# ER-524D_CoilDriver24.net
KiCad netlist of a schematic drawn in EAGLE
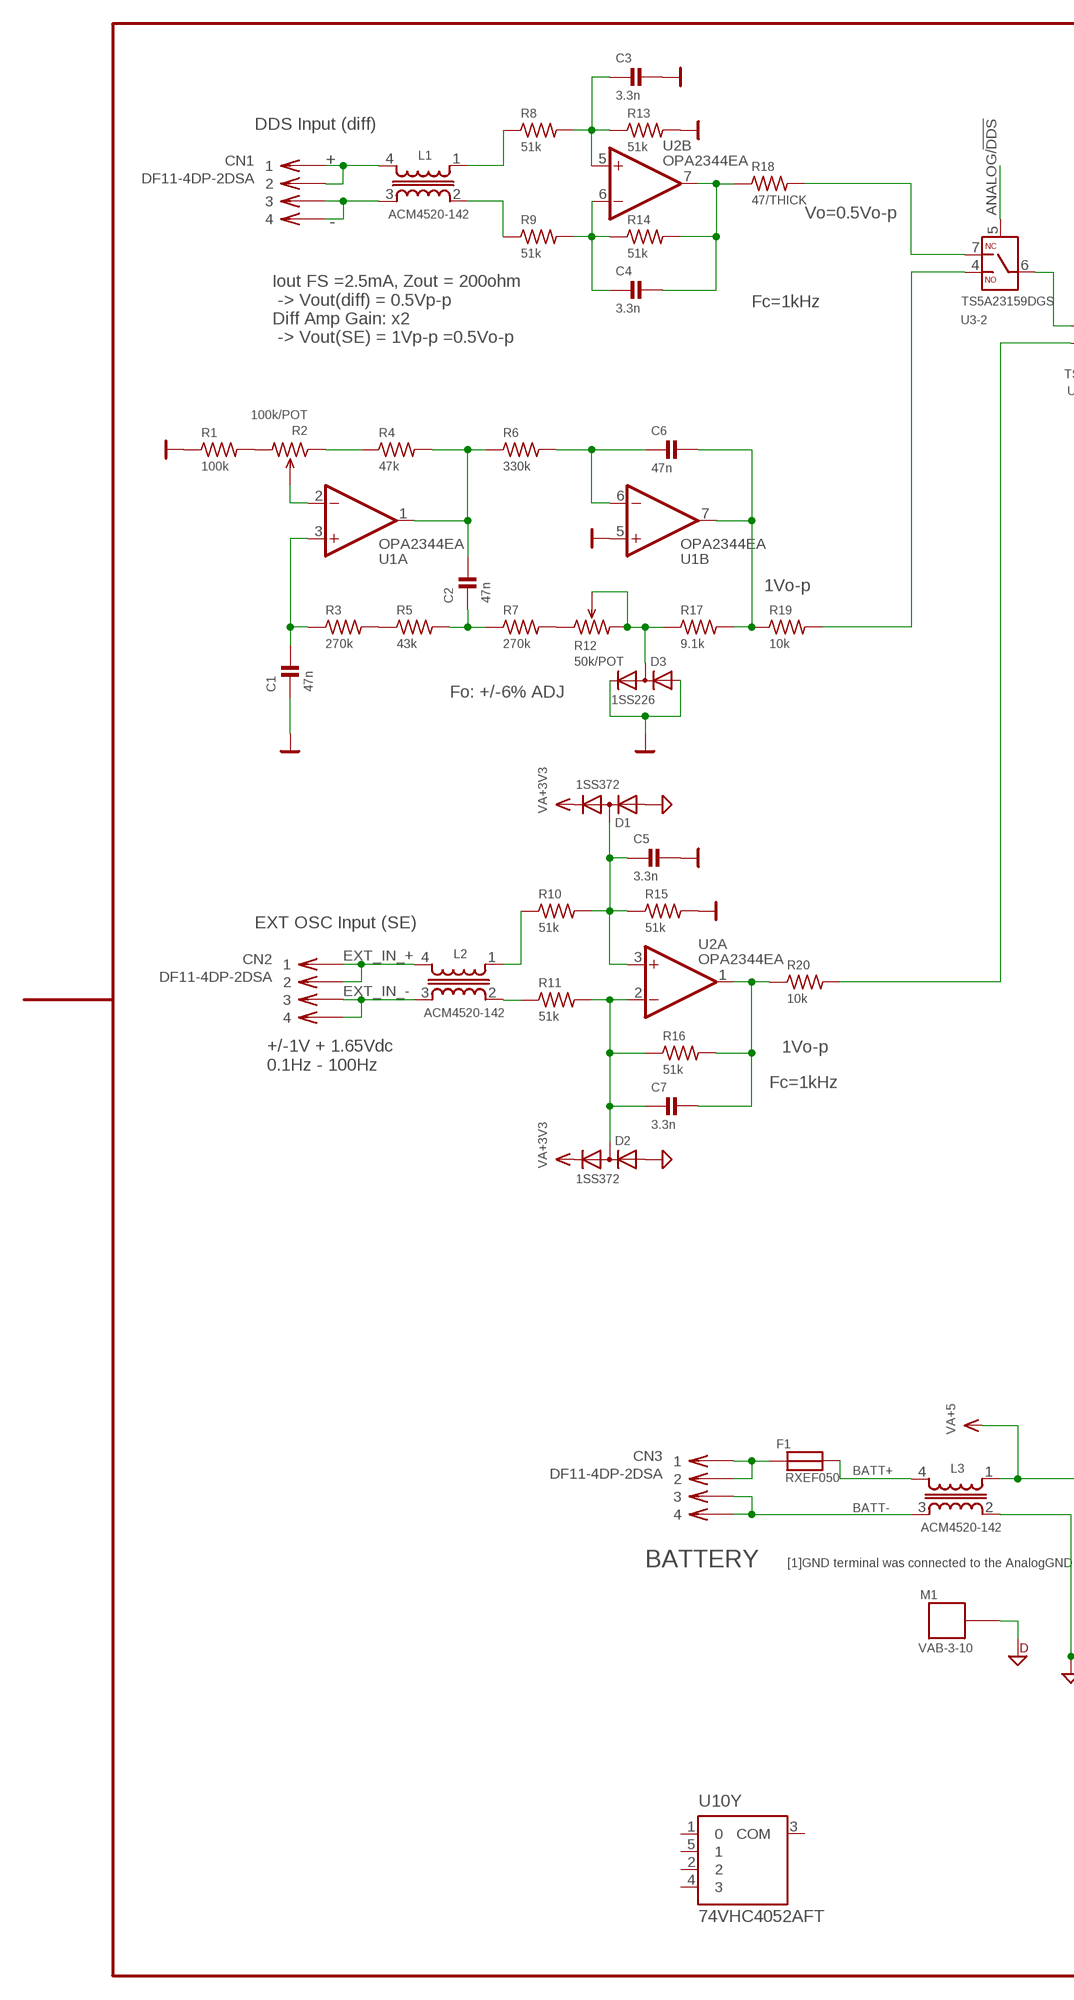
[diagram p0: schematic, sheet 1, part 1 of 2]
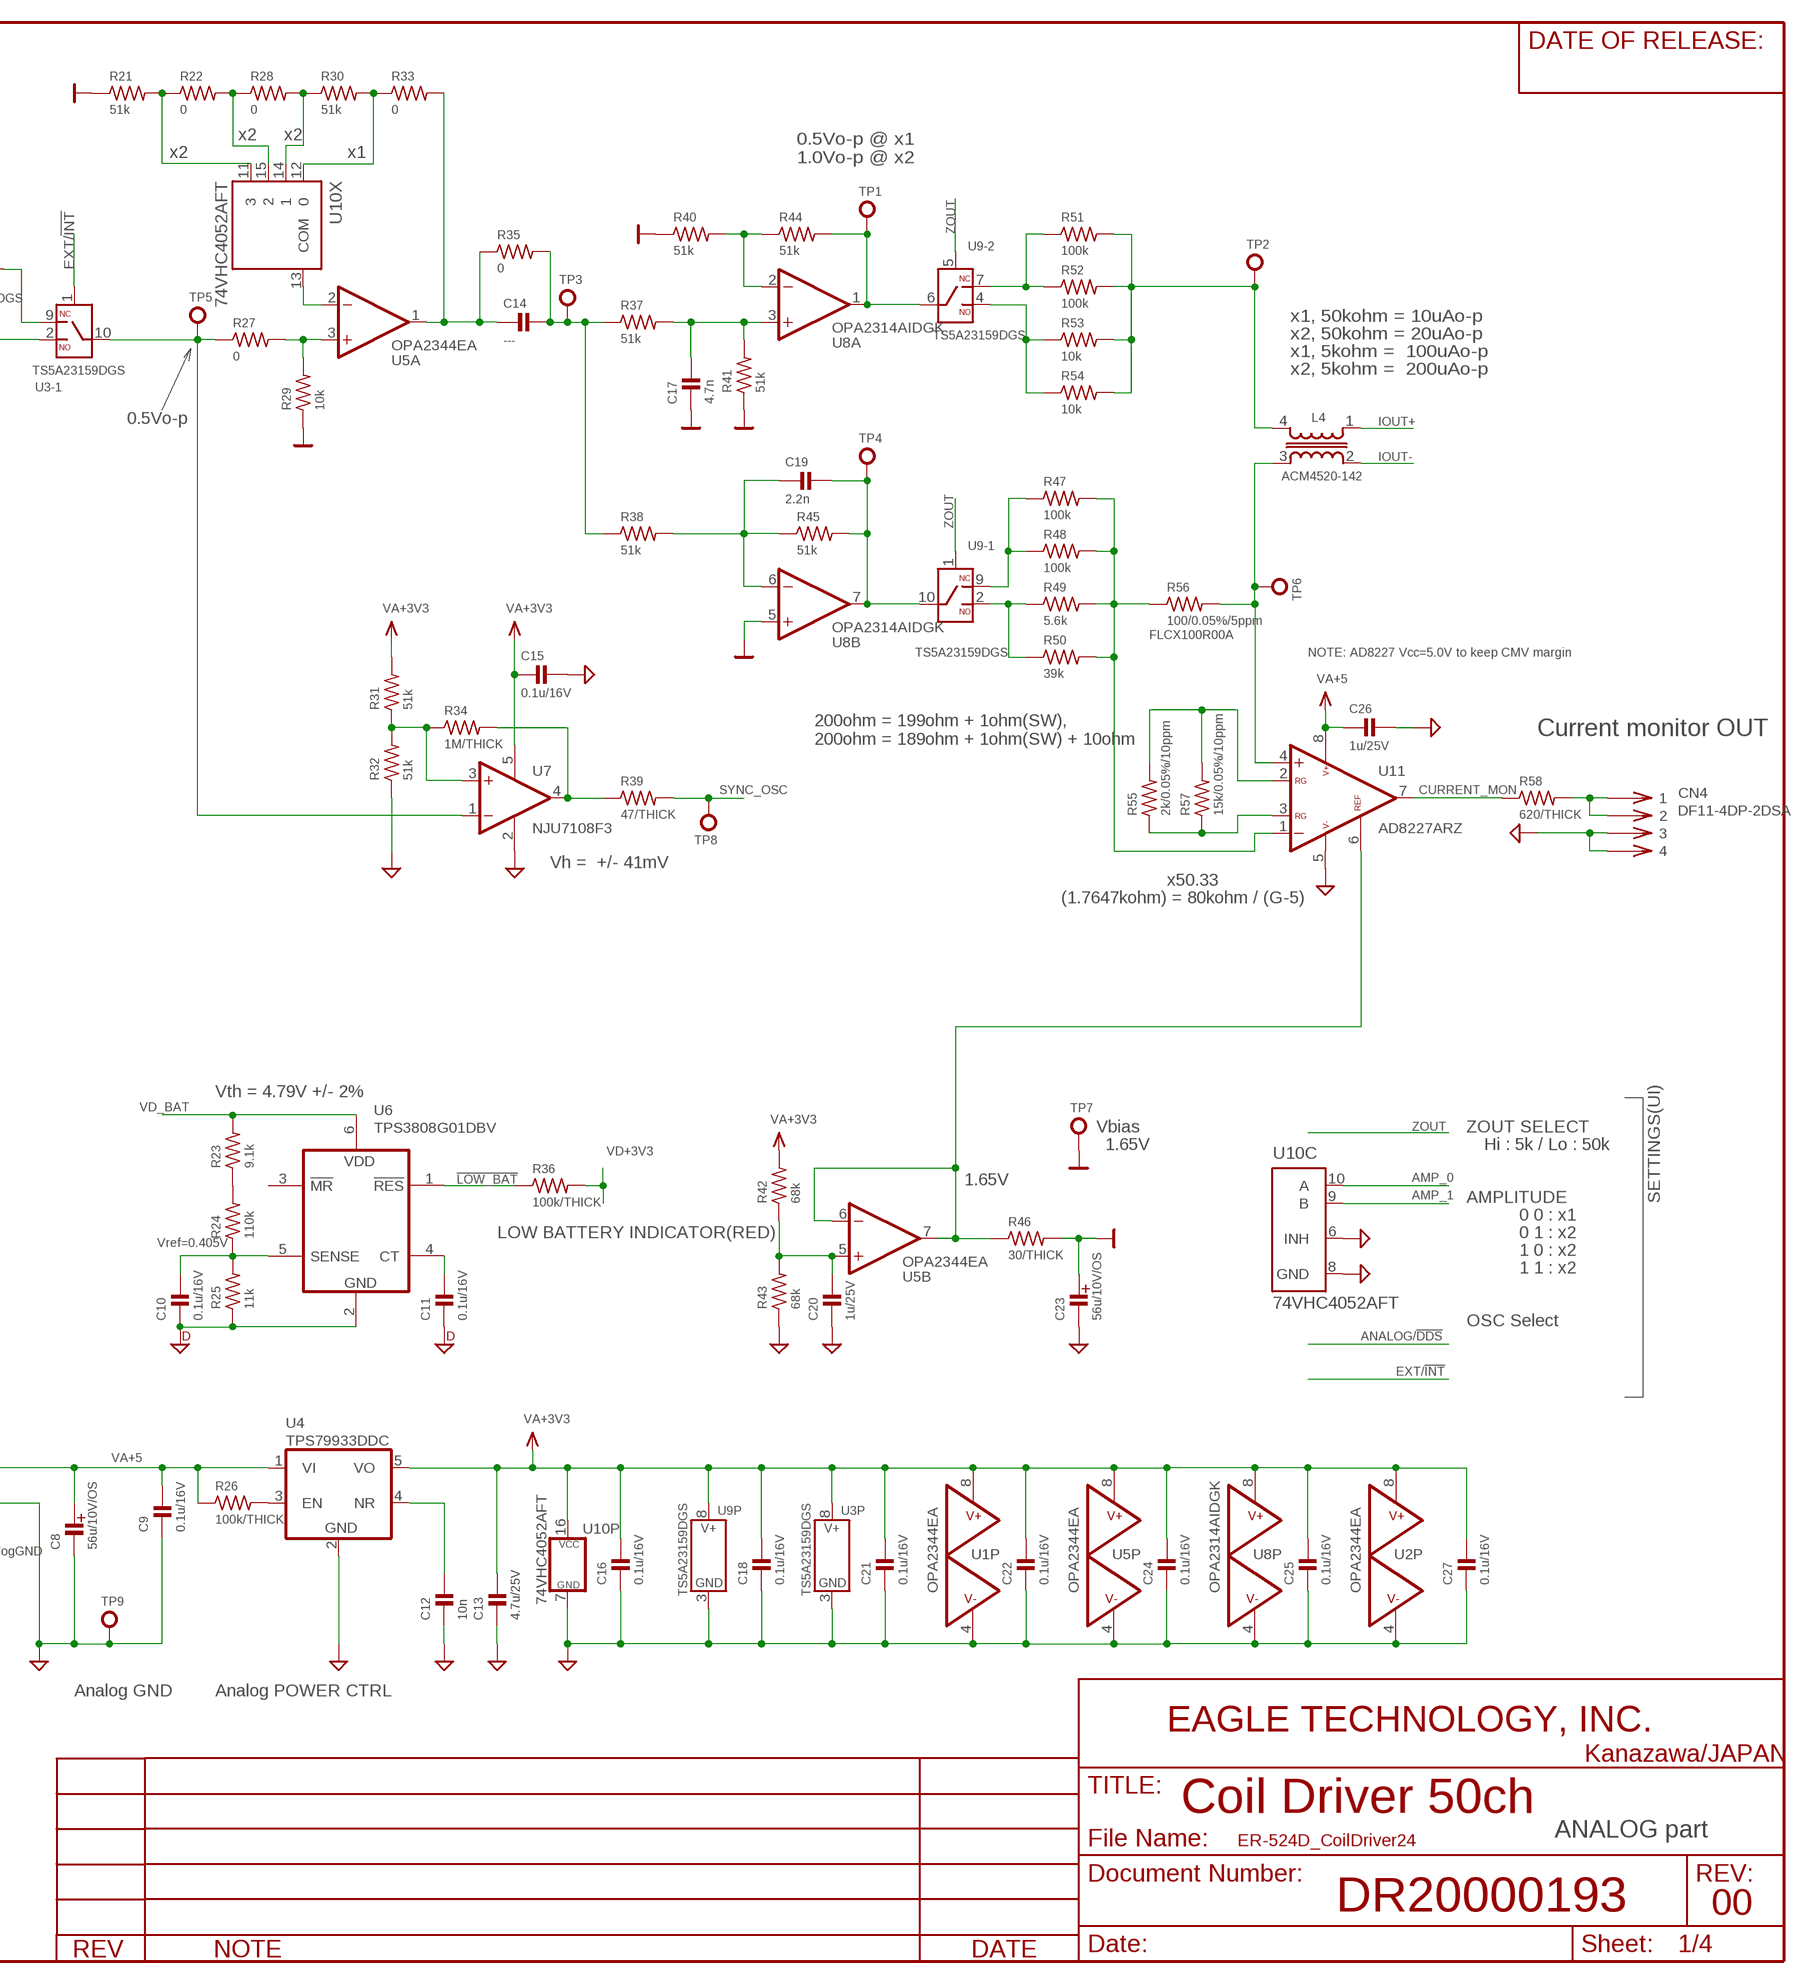
[diagram p1: schematic, sheet 1, part 2 of 2]
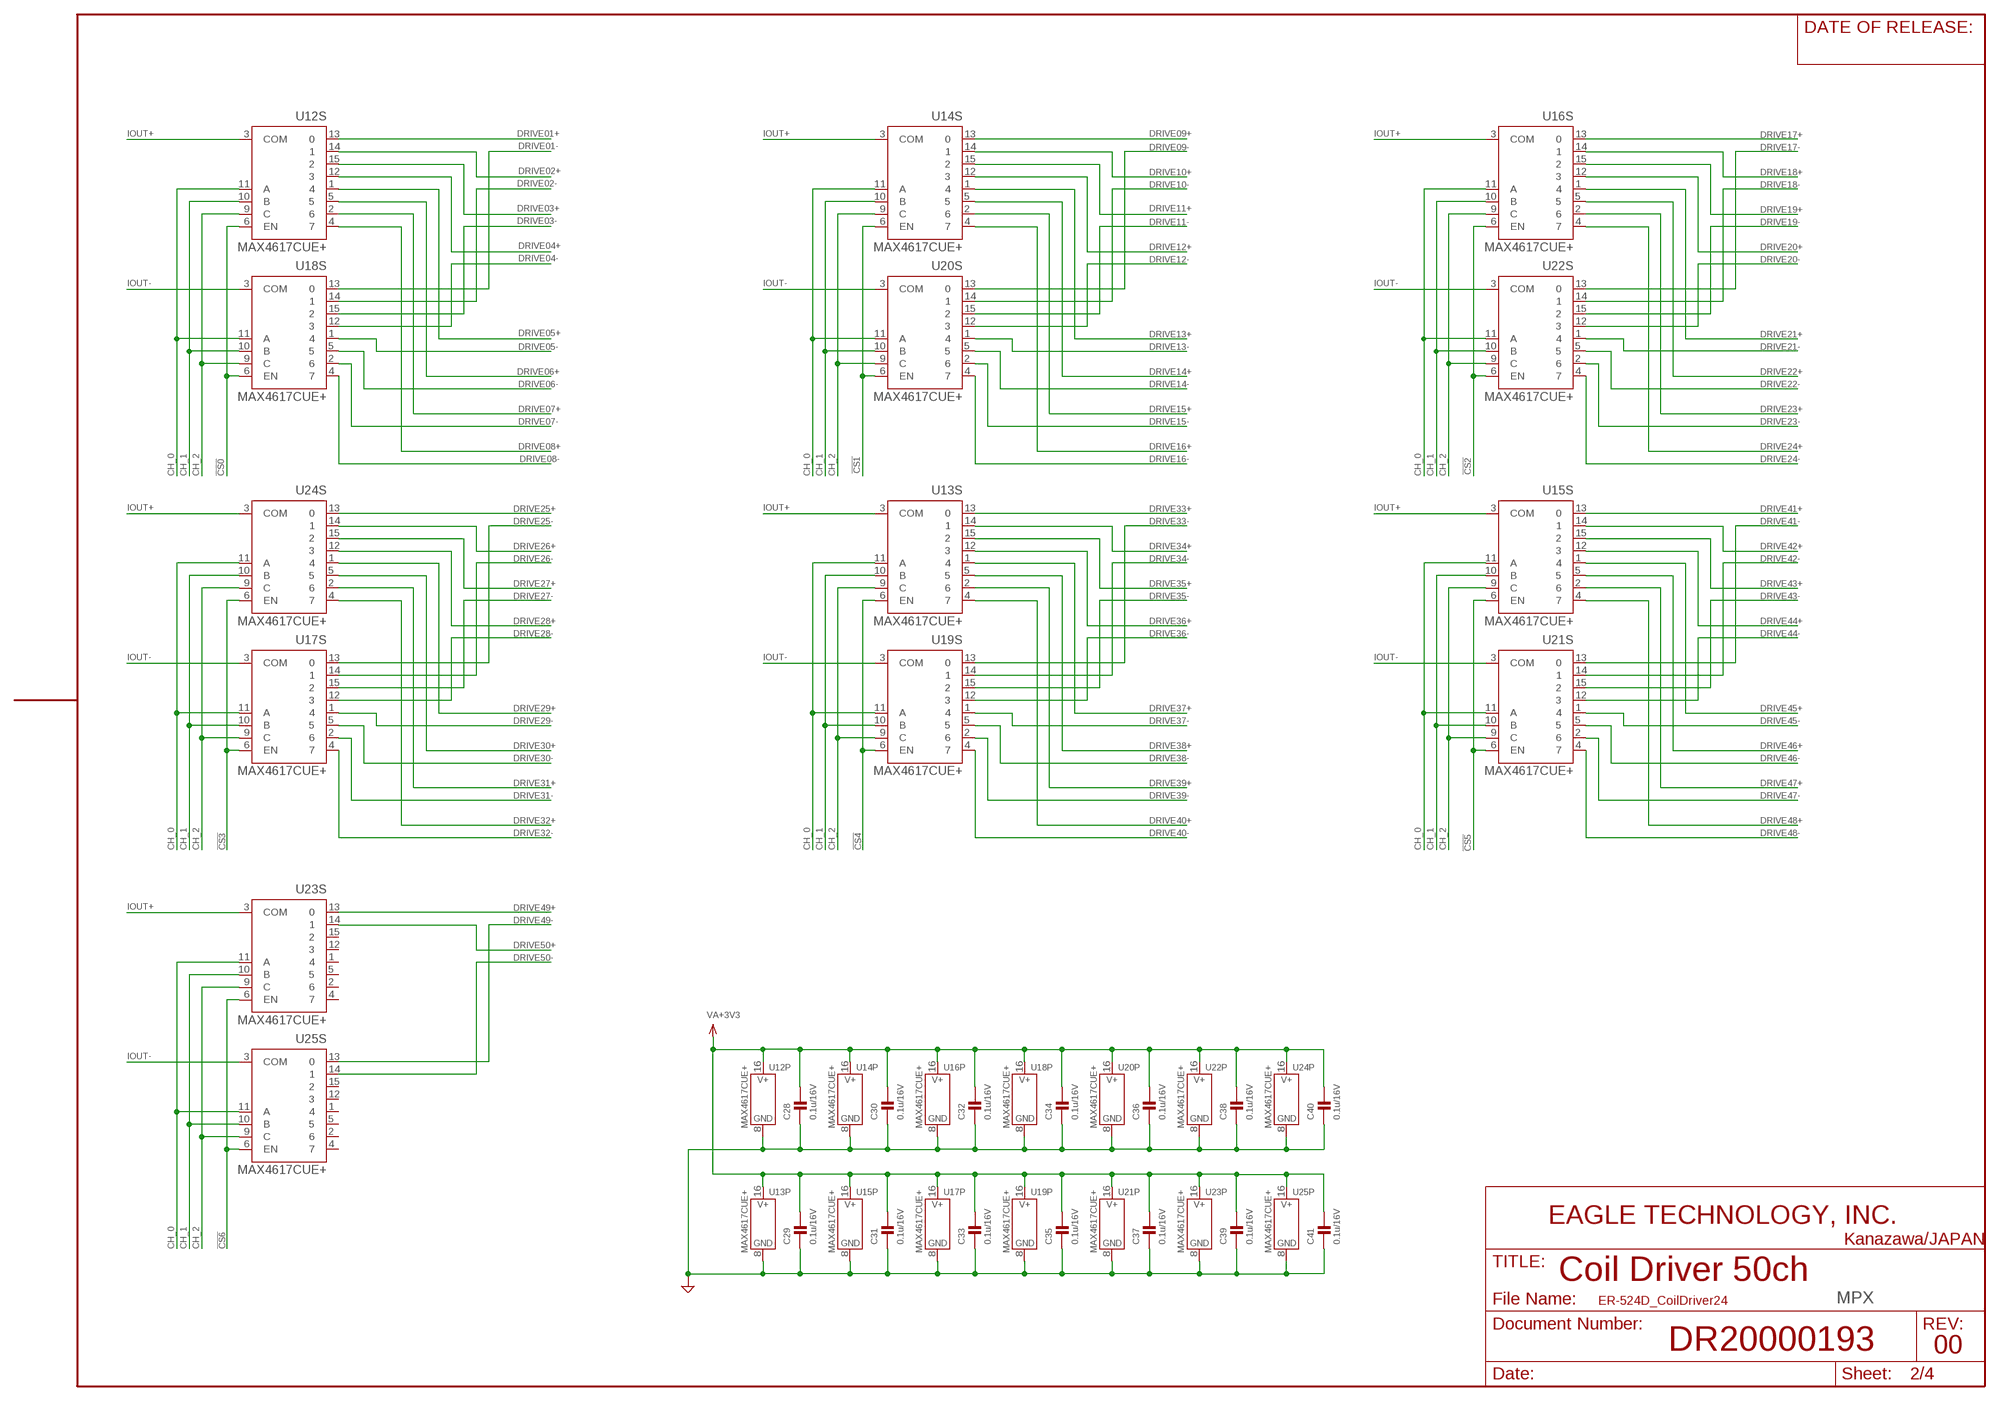
[diagram p2: schematic, sheet 2]
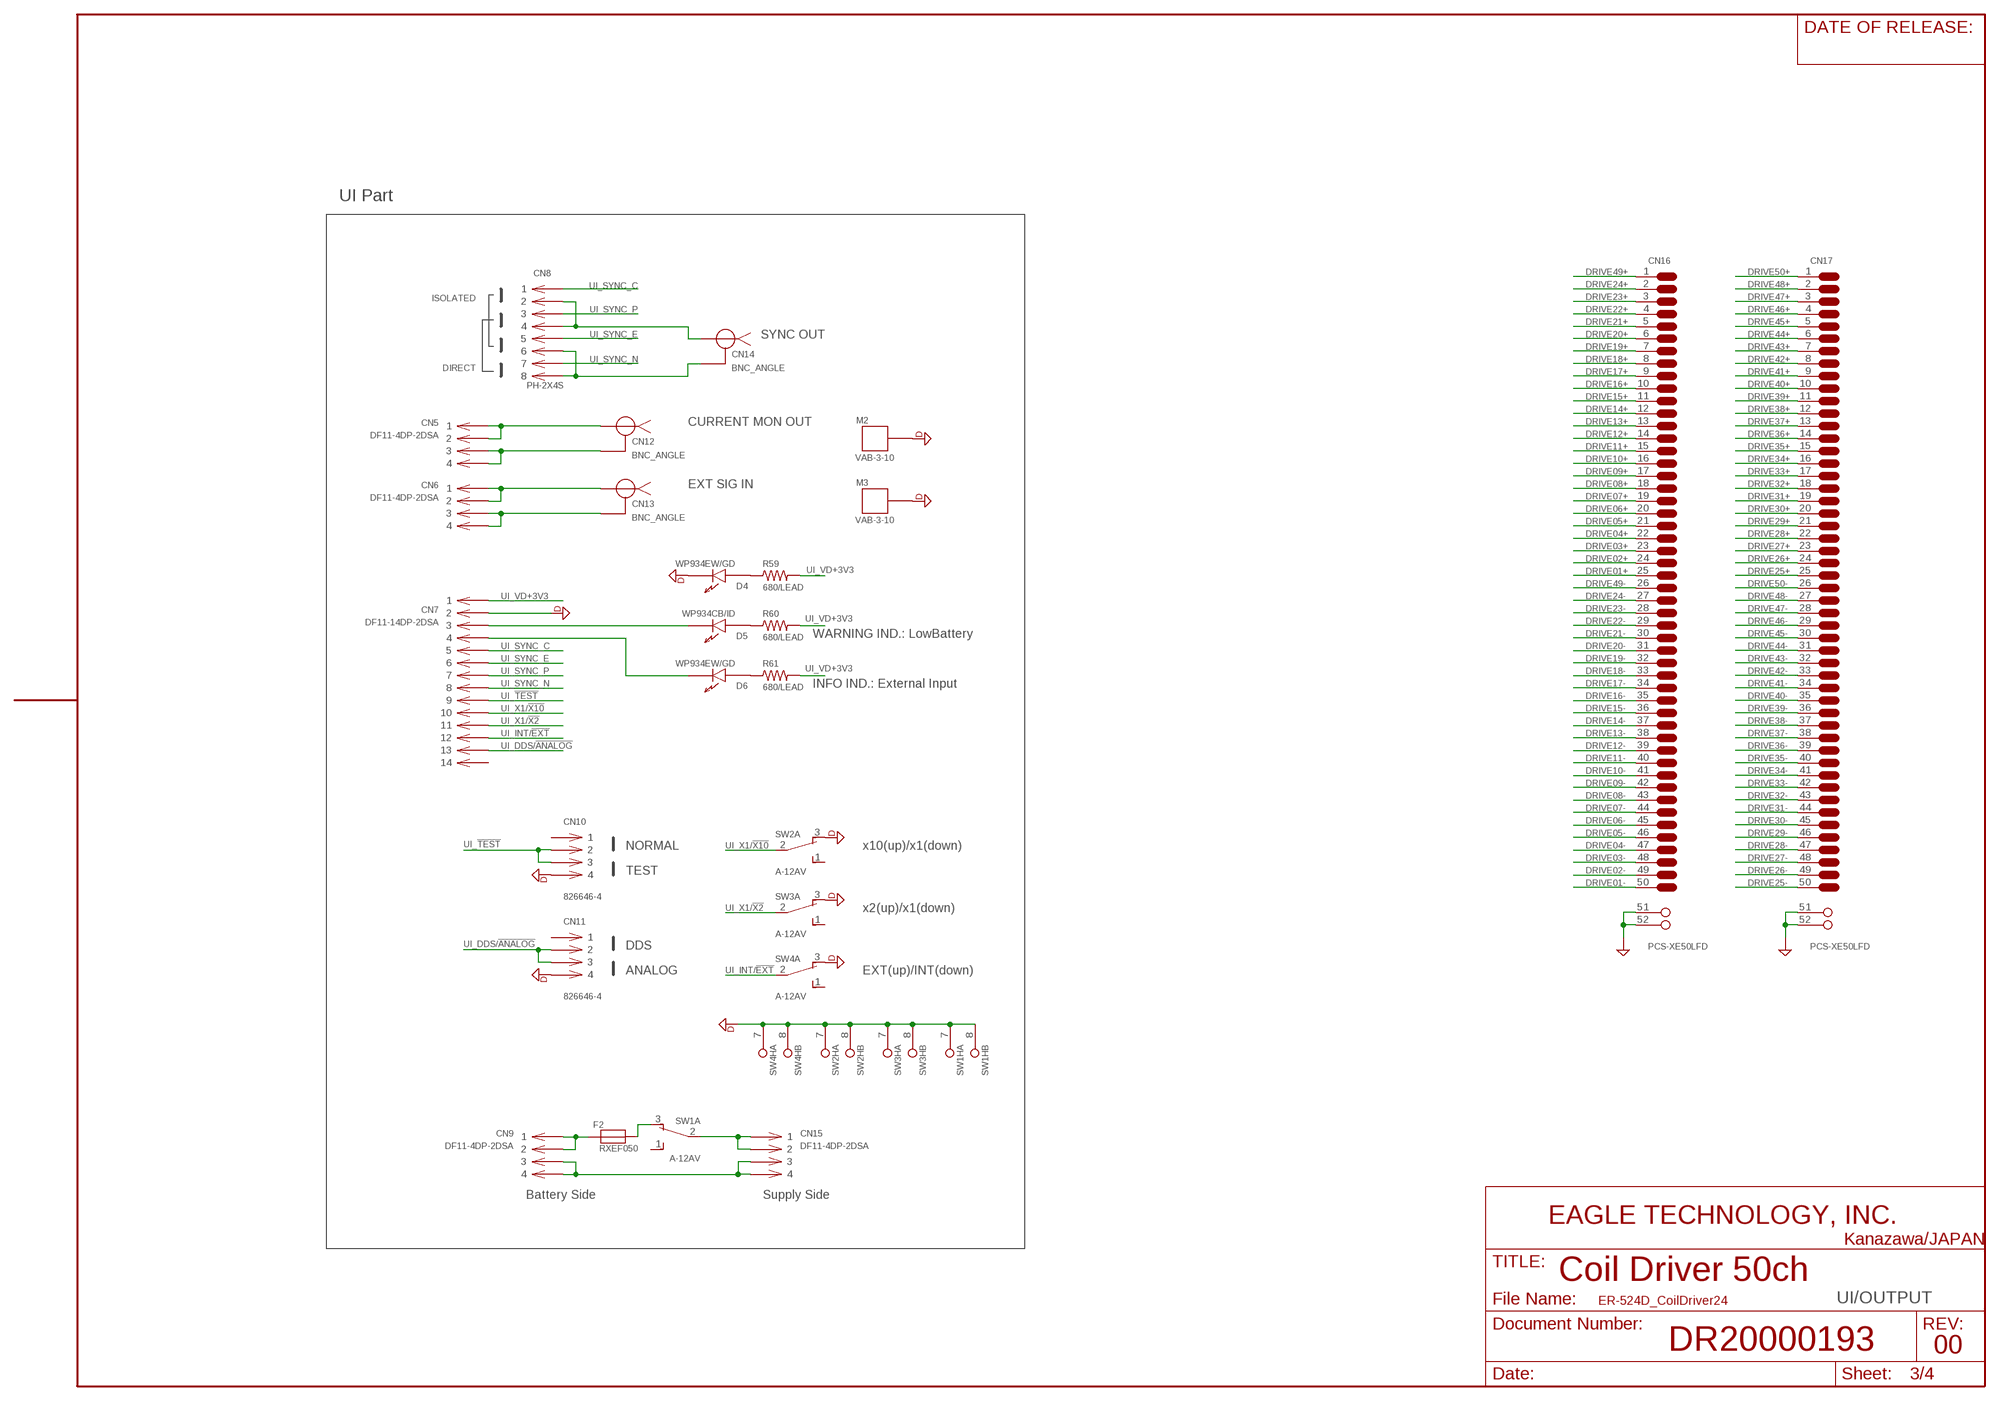
[diagram p3: schematic, sheet 3]
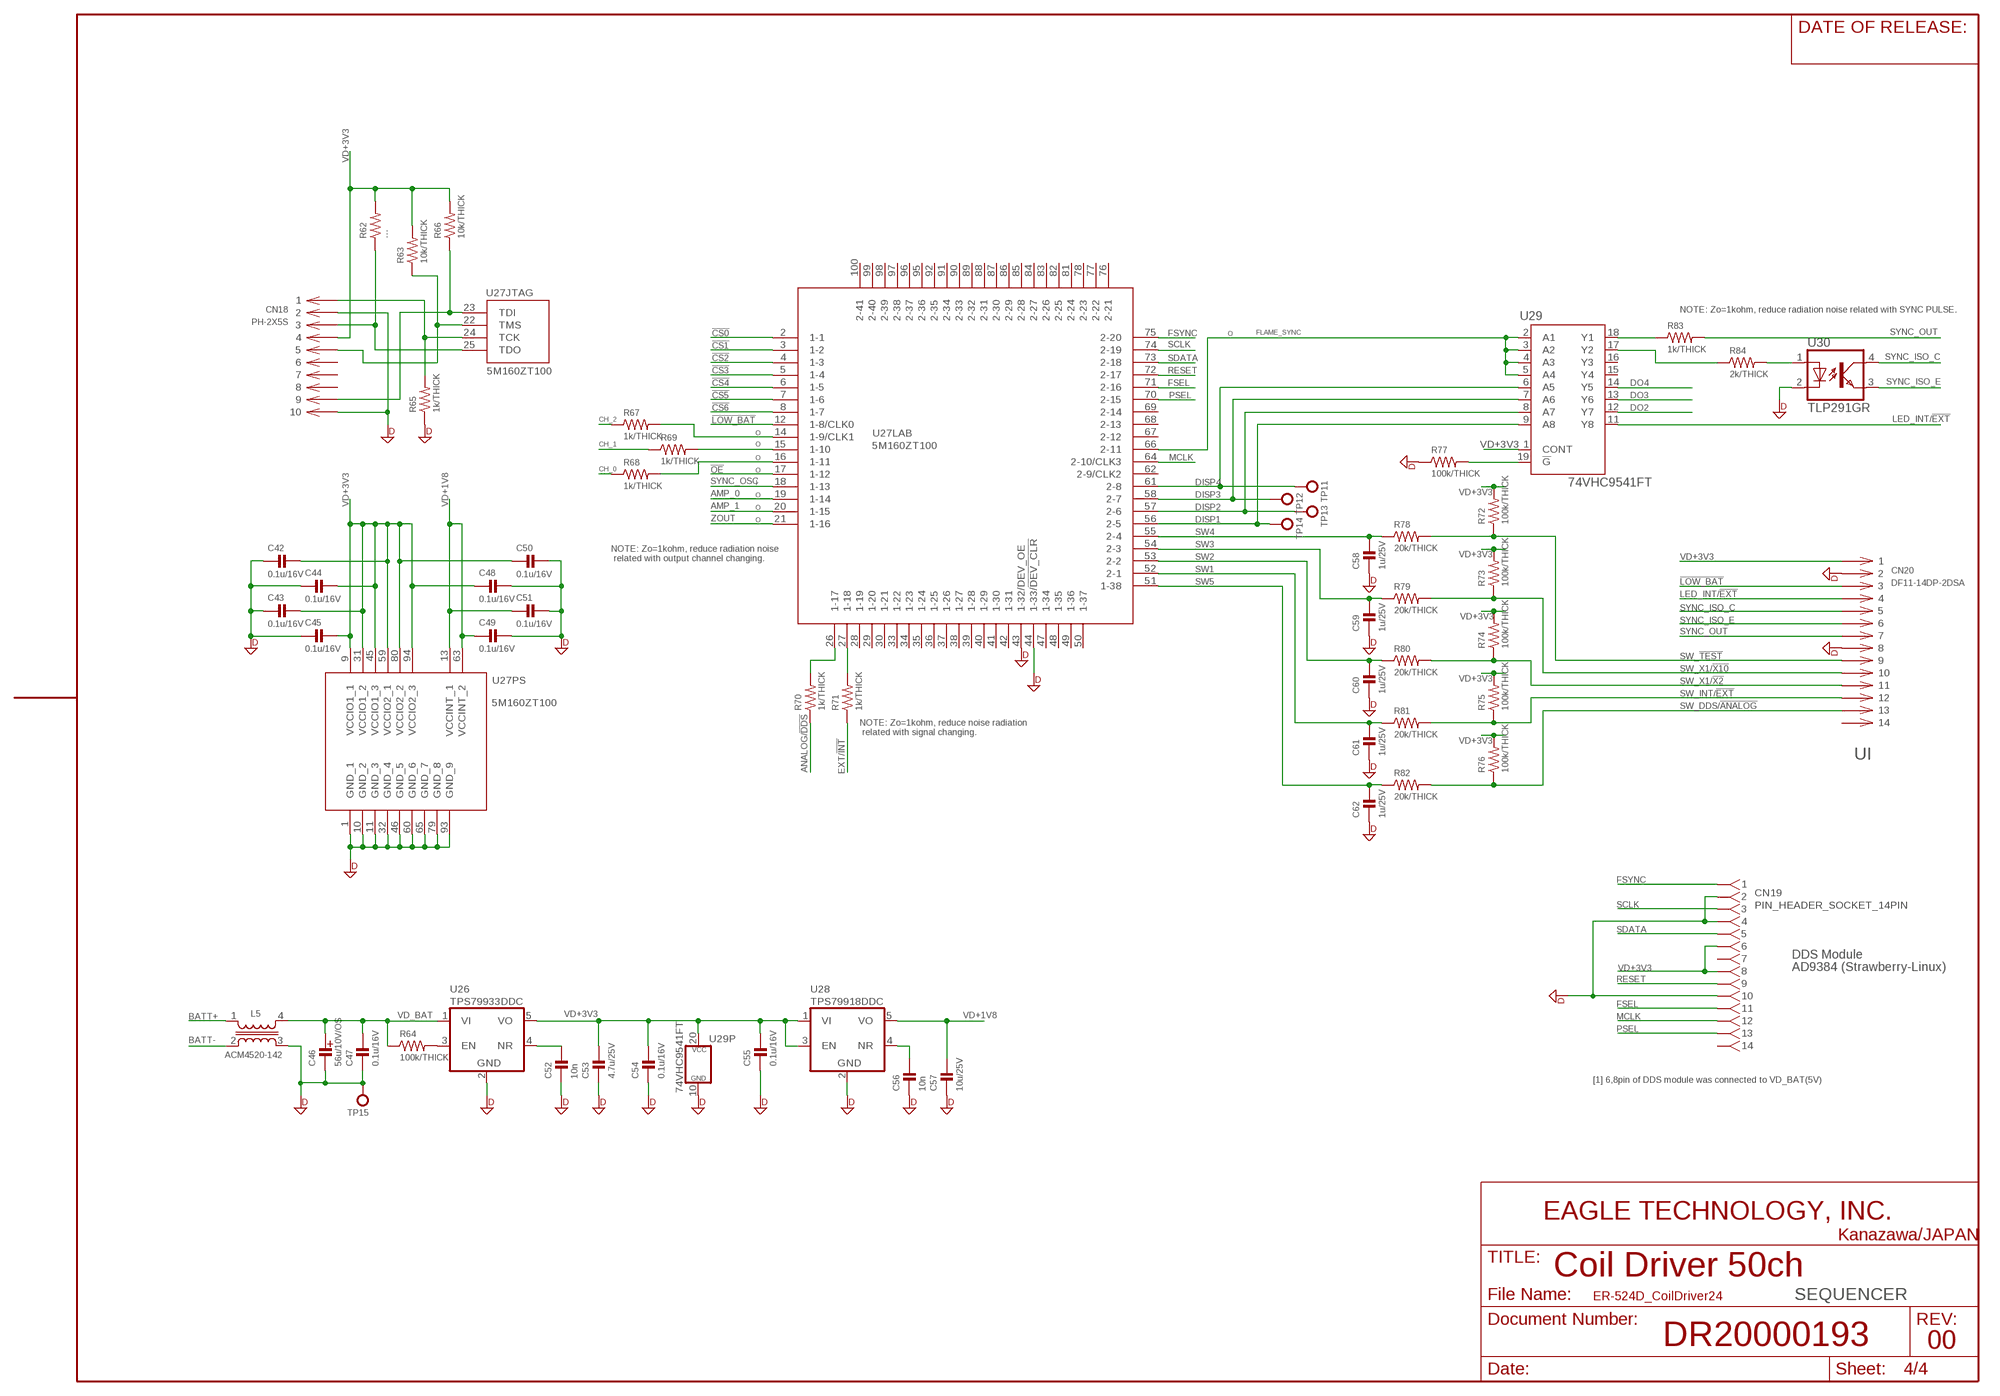
[diagram p4: schematic, sheet 4]

(export (version "E")
  (design (tool "Eeschema 10.0.6"))
  (components
    (comp (ref "C42")
      (value "0.1u/16V")
      (footprint "eagle-import:CM1005")
      (libsource (lib "eagle-import") (part "CSMD1.0X0.5MM"))
    )
    (comp (ref "C43")
      (value "0.1u/16V")
      (footprint "eagle-import:CM1005")
      (libsource (lib "eagle-import") (part "CSMD1.0X0.5MM"))
    )
    (comp (ref "C44")
      (value "0.1u/16V")
      (footprint "eagle-import:CM1005")
      (libsource (lib "eagle-import") (part "CSMD1.0X0.5MM"))
    )
    (comp (ref "C45")
      (value "0.1u/16V")
      (footprint "eagle-import:CM1005")
      (libsource (lib "eagle-import") (part "CSMD1.0X0.5MM"))
    )
    (comp (ref "C46")
      (value "56u/10V/OS")
      (footprint "eagle-import:PHI_6.3")
      (libsource (lib "eagle-import") (part "C_POL6.3-2.5MM"))
    )
    (comp (ref "C47")
      (value "0.1u/16V")
      (footprint "eagle-import:CM1005")
      (libsource (lib "eagle-import") (part "CSMD1.0X0.5MM"))
    )
    (comp (ref "C48")
      (value "0.1u/16V")
      (footprint "eagle-import:CM1005")
      (libsource (lib "eagle-import") (part "CSMD1.0X0.5MM"))
    )
    (comp (ref "C49")
      (value "0.1u/16V")
      (footprint "eagle-import:CM1005")
      (libsource (lib "eagle-import") (part "CSMD1.0X0.5MM"))
    )
    (comp (ref "C50")
      (value "0.1u/16V")
      (footprint "eagle-import:CM1005")
      (libsource (lib "eagle-import") (part "CSMD1.0X0.5MM"))
    )
    (comp (ref "C51")
      (value "0.1u/16V")
      (footprint "eagle-import:CM1005")
      (libsource (lib "eagle-import") (part "CSMD1.0X0.5MM"))
    )
    (comp (ref "C52")
      (value "10n")
      (footprint "eagle-import:CM2012")
      (libsource (lib "eagle-import") (part "CSMD2.0X1.2MM"))
    )
    (comp (ref "C53")
      (value "4.7u/25V")
      (footprint "eagle-import:CM2012")
      (libsource (lib "eagle-import") (part "CSMD2.0X1.2MM"))
    )
    (comp (ref "C54")
      (value "0.1u/16V")
      (footprint "eagle-import:CM1005")
      (libsource (lib "eagle-import") (part "CSMD1.0X0.5MM"))
    )
    (comp (ref "C55")
      (value "0.1u/16V")
      (footprint "eagle-import:CM1005")
      (libsource (lib "eagle-import") (part "CSMD1.0X0.5MM"))
    )
    (comp (ref "C56")
      (value "10n")
      (footprint "eagle-import:CM2012")
      (libsource (lib "eagle-import") (part "CSMD2.0X1.2MM"))
    )
    (comp (ref "C57")
      (value "10u/25V")
      (footprint "eagle-import:CM2012")
      (libsource (lib "eagle-import") (part "CSMD2.0X1.2MM"))
    )
    (comp (ref "C58")
      (value "1u/25V")
      (footprint "eagle-import:CM1608")
      (libsource (lib "eagle-import") (part "CSMD1.6X0.8MM"))
    )
    (comp (ref "C59")
      (value "1u/25V")
      (footprint "eagle-import:CM1608")
      (libsource (lib "eagle-import") (part "CSMD1.6X0.8MM"))
    )
    (comp (ref "C60")
      (value "1u/25V")
      (footprint "eagle-import:CM1608")
      (libsource (lib "eagle-import") (part "CSMD1.6X0.8MM"))
    )
    (comp (ref "C61")
      (value "1u/25V")
      (footprint "eagle-import:CM1608")
      (libsource (lib "eagle-import") (part "CSMD1.6X0.8MM"))
    )
    (comp (ref "C62")
      (value "1u/25V")
      (footprint "eagle-import:CM1608")
      (libsource (lib "eagle-import") (part "CSMD1.6X0.8MM"))
    )
    (comp (ref "CN18")
      (value "PH-2X5S")
      (footprint "eagle-import:PIN_HEADER_10PIN")
      (libsource (lib "eagle-import") (part "PIN_HEADER_10PIN"))
    )
    (comp (ref "CN19")
      (value "PIN_HEADER_SOCKET_14PIN")
      (footprint "eagle-import:PIN_HEADER_SOCKET_14PIN")
      (libsource (lib "eagle-import") (part "PIN_HEADER_SOCKET_14PIN"))
    )
    (comp (ref "CN20")
      (value "DF11-14DP-2DSA")
      (footprint "eagle-import:DF11-14DP-2DSA")
      (libsource (lib "eagle-import") (part "DF11-14DP-2DSA"))
    )
    (comp (ref "L5")
      (value "ACM4520-142")
      (footprint "eagle-import:ACM4520")
      (libsource (lib "eagle-import") (part "ACM4520-142"))
    )
    (comp (ref "R62")
      (value "---")
      (footprint "eagle-import:RM1608")
      (libsource (lib "eagle-import") (part "RSMD1.6X0.8MM"))
    )
    (comp (ref "R63")
      (value "10k/THICK")
      (footprint "eagle-import:RM1608")
      (libsource (lib "eagle-import") (part "RSMD1.6X0.8MM"))
    )
    (comp (ref "R64")
      (value "100k/THICK")
      (footprint "eagle-import:RM1608")
      (libsource (lib "eagle-import") (part "RSMD1.6X0.8MM"))
    )
    (comp (ref "R65")
      (value "1k/THICK")
      (footprint "eagle-import:RM1608")
      (libsource (lib "eagle-import") (part "RSMD1.6X0.8MM"))
    )
    (comp (ref "R66")
      (value "10k/THICK")
      (footprint "eagle-import:RM1608")
      (libsource (lib "eagle-import") (part "RSMD1.6X0.8MM"))
    )
    (comp (ref "R67")
      (value "1k/THICK")
      (footprint "eagle-import:RM1608")
      (libsource (lib "eagle-import") (part "RSMD1.6X0.8MM"))
    )
    (comp (ref "R68")
      (value "1k/THICK")
      (footprint "eagle-import:RM1608")
      (libsource (lib "eagle-import") (part "RSMD1.6X0.8MM"))
    )
    (comp (ref "R69")
      (value "1k/THICK")
      (footprint "eagle-import:RM1608")
      (libsource (lib "eagle-import") (part "RSMD1.6X0.8MM"))
    )
    (comp (ref "R70")
      (value "1k/THICK")
      (footprint "eagle-import:RM1608")
      (libsource (lib "eagle-import") (part "RSMD1.6X0.8MM"))
    )
    (comp (ref "R71")
      (value "1k/THICK")
      (footprint "eagle-import:RM1608")
      (libsource (lib "eagle-import") (part "RSMD1.6X0.8MM"))
    )
    (comp (ref "R72")
      (value "100k/THICK")
      (footprint "eagle-import:RM1608")
      (libsource (lib "eagle-import") (part "RSMD1.6X0.8MM"))
    )
    (comp (ref "R73")
      (value "100k/THICK")
      (footprint "eagle-import:RM1608")
      (libsource (lib "eagle-import") (part "RSMD1.6X0.8MM"))
    )
    (comp (ref "R74")
      (value "100k/THICK")
      (footprint "eagle-import:RM1608")
      (libsource (lib "eagle-import") (part "RSMD1.6X0.8MM"))
    )
    (comp (ref "R75")
      (value "100k/THICK")
      (footprint "eagle-import:RM1608")
      (libsource (lib "eagle-import") (part "RSMD1.6X0.8MM"))
    )
    (comp (ref "R76")
      (value "100k/THICK")
      (footprint "eagle-import:RM1608")
      (libsource (lib "eagle-import") (part "RSMD1.6X0.8MM"))
    )
    (comp (ref "R77")
      (value "100k/THICK")
      (footprint "eagle-import:RM1608")
      (libsource (lib "eagle-import") (part "RSMD1.6X0.8MM"))
    )
    (comp (ref "R78")
      (value "20k/THICK")
      (footprint "eagle-import:RM1608")
      (libsource (lib "eagle-import") (part "RSMD1.6X0.8MM"))
    )
    (comp (ref "R79")
      (value "20k/THICK")
      (footprint "eagle-import:RM1608")
      (libsource (lib "eagle-import") (part "RSMD1.6X0.8MM"))
    )
    (comp (ref "R80")
      (value "20k/THICK")
      (footprint "eagle-import:RM1608")
      (libsource (lib "eagle-import") (part "RSMD1.6X0.8MM"))
    )
    (comp (ref "R81")
      (value "20k/THICK")
      (footprint "eagle-import:RM1608")
      (libsource (lib "eagle-import") (part "RSMD1.6X0.8MM"))
    )
    (comp (ref "R82")
      (value "20k/THICK")
      (footprint "eagle-import:RM1608")
      (libsource (lib "eagle-import") (part "RSMD1.6X0.8MM"))
    )
    (comp (ref "R83")
      (value "1k/THICK")
      (footprint "eagle-import:RM1608")
      (libsource (lib "eagle-import") (part "RSMD1.6X0.8MM"))
    )
    (comp (ref "R84")
      (value "2k/THICK")
      (footprint "eagle-import:RM1608")
      (libsource (lib "eagle-import") (part "RSMD1.6X0.8MM"))
    )
    (comp (ref "TP11")
      (value "TP-1MM_PAD")
      (footprint "eagle-import:TP_PAD_1MM")
      (libsource (lib "eagle-import") (part "TP-1MM_PAD"))
    )
    (comp (ref "TP12")
      (value "TP-1MM_PAD")
      (footprint "eagle-import:TP_PAD_1MM")
      (libsource (lib "eagle-import") (part "TP-1MM_PAD"))
    )
    (comp (ref "TP13")
      (value "TP-1MM_PAD")
      (footprint "eagle-import:TP_PAD_1MM")
      (libsource (lib "eagle-import") (part "TP-1MM_PAD"))
    )
    (comp (ref "TP14")
      (value "TP-1MM_PAD")
      (footprint "eagle-import:TP_PAD_1MM")
      (libsource (lib "eagle-import") (part "TP-1MM_PAD"))
    )
    (comp (ref "TP15")
      (value "TP-LC3G")
      (footprint "eagle-import:TP_TH_0R9MM")
      (libsource (lib "eagle-import") (part "TP-LC3G"))
    )
    (comp (ref "U26")
      (value "TPS79933DDC")
      (footprint "eagle-import:SOT-23-5")
      (libsource (lib "eagle-import") (part "TPS799DDC33"))
    )
    (comp (ref "U27")
      (value "5M160ZT100")
      (footprint "eagle-import:QFP100_0.5")
      (libsource (lib "eagle-import") (part "5M160ZT100"))
    )
    (comp (ref "U28")
      (value "TPS79918DDC")
      (footprint "eagle-import:SOT-23-5")
      (libsource (lib "eagle-import") (part "TPS799DDC18"))
    )
    (comp (ref "U29")
      (value "74VHC9541FT")
      (footprint "eagle-import:TSSOP20-P-0044-065A")
      (libsource (lib "eagle-import") (part "749541FTVHC"))
    )
    (comp (ref "U30")
      (value "TLP291GR")
      (footprint "eagle-import:SO4(11-3C1)(TOSHIBA)")
      (libsource (lib "eagle-import") (part "TLP291GR"))
    )
    (comp (ref "C1")
      (value "47n")
      (footprint "eagle-import:CM3216")
      (libsource (lib "eagle-import") (part "CSMD3.2X1.6MM"))
    )
    (comp (ref "C2")
      (value "47n")
      (footprint "eagle-import:CM3216")
      (libsource (lib "eagle-import") (part "CSMD3.2X1.6MM"))
    )
    (comp (ref "C3")
      (value "3.3n")
      (footprint "eagle-import:CM2012")
      (libsource (lib "eagle-import") (part "CSMD2.0X1.2MM"))
    )
    (comp (ref "C4")
      (value "3.3n")
      (footprint "eagle-import:CM2012")
      (libsource (lib "eagle-import") (part "CSMD2.0X1.2MM"))
    )
    (comp (ref "C5")
      (value "3.3n")
      (footprint "eagle-import:CM2012")
      (libsource (lib "eagle-import") (part "CSMD2.0X1.2MM"))
    )
    (comp (ref "C6")
      (value "47n")
      (footprint "eagle-import:CM3216")
      (libsource (lib "eagle-import") (part "CSMD3.2X1.6MM"))
    )
    (comp (ref "C7")
      (value "3.3n")
      (footprint "eagle-import:CM2012")
      (libsource (lib "eagle-import") (part "CSMD2.0X1.2MM"))
    )
    (comp (ref "C8")
      (value "56u/10V/OS")
      (footprint "eagle-import:PHI_6.3")
      (libsource (lib "eagle-import") (part "C_POL6.3-2.5MM"))
    )
    (comp (ref "C9")
      (value "0.1u/16V")
      (footprint "eagle-import:CM1005")
      (libsource (lib "eagle-import") (part "CSMD1.0X0.5MM"))
    )
    (comp (ref "C10")
      (value "0.1u/16V")
      (footprint "eagle-import:CM1005")
      (libsource (lib "eagle-import") (part "CSMD1.0X0.5MM"))
    )
    (comp (ref "C11")
      (value "0.1u/16V")
      (footprint "eagle-import:CM1005")
      (libsource (lib "eagle-import") (part "CSMD1.0X0.5MM"))
    )
    (comp (ref "C12")
      (value "10n")
      (footprint "eagle-import:CM2012")
      (libsource (lib "eagle-import") (part "CSMD2.0X1.2MM"))
    )
    (comp (ref "C13")
      (value "4.7u/25V")
      (footprint "eagle-import:CM2012")
      (libsource (lib "eagle-import") (part "CSMD2.0X1.2MM"))
    )
    (comp (ref "C14")
      (value "---")
      (footprint "eagle-import:CM3216")
      (libsource (lib "eagle-import") (part "CSMD3.2X1.6MM"))
    )
    (comp (ref "C15")
      (value "0.1u/16V")
      (footprint "eagle-import:CM1005")
      (libsource (lib "eagle-import") (part "CSMD1.0X0.5MM"))
    )
    (comp (ref "C16")
      (value "0.1u/16V")
      (footprint "eagle-import:CM1005")
      (libsource (lib "eagle-import") (part "CSMD1.0X0.5MM"))
    )
    (comp (ref "C17")
      (value "4.7n")
      (footprint "eagle-import:CM2012")
      (libsource (lib "eagle-import") (part "CSMD2.0X1.2MM"))
    )
    (comp (ref "C18")
      (value "0.1u/16V")
      (footprint "eagle-import:CM1005")
      (libsource (lib "eagle-import") (part "CSMD1.0X0.5MM"))
    )
    (comp (ref "C19")
      (value "2.2n")
      (footprint "eagle-import:CM2012")
      (libsource (lib "eagle-import") (part "CSMD2.0X1.2MM"))
    )
    (comp (ref "C20")
      (value "1u/25V")
      (footprint "eagle-import:CM1608")
      (libsource (lib "eagle-import") (part "CSMD1.6X0.8MM"))
    )
    (comp (ref "C21")
      (value "0.1u/16V")
      (footprint "eagle-import:CM1005")
      (libsource (lib "eagle-import") (part "CSMD1.0X0.5MM"))
    )
    (comp (ref "C22")
      (value "0.1u/16V")
      (footprint "eagle-import:CM1005")
      (libsource (lib "eagle-import") (part "CSMD1.0X0.5MM"))
    )
    (comp (ref "C23")
      (value "56u/10V/OS")
      (footprint "eagle-import:PHI_6.3")
      (libsource (lib "eagle-import") (part "C_POL6.3-2.5MM"))
    )
    (comp (ref "C24")
      (value "0.1u/16V")
      (footprint "eagle-import:CM1005")
      (libsource (lib "eagle-import") (part "CSMD1.0X0.5MM"))
    )
    (comp (ref "C25")
      (value "0.1u/16V")
      (footprint "eagle-import:CM1005")
      (libsource (lib "eagle-import") (part "CSMD1.0X0.5MM"))
    )
    (comp (ref "C26")
      (value "1u/25V")
      (footprint "eagle-import:CM1608")
      (libsource (lib "eagle-import") (part "CSMD1.6X0.8MM"))
    )
    (comp (ref "C27")
      (value "0.1u/16V")
      (footprint "eagle-import:CM1005")
      (libsource (lib "eagle-import") (part "CSMD1.0X0.5MM"))
    )
    (comp (ref "CN1")
      (value "DF11-4DP-2DSA")
      (footprint "eagle-import:DF11-4DP-2DSA")
      (libsource (lib "eagle-import") (part "DF11-4DP-2DSA"))
    )
    (comp (ref "CN2")
      (value "DF11-4DP-2DSA")
      (footprint "eagle-import:DF11-4DP-2DSA")
      (libsource (lib "eagle-import") (part "DF11-4DP-2DSA"))
    )
    (comp (ref "CN3")
      (value "DF11-4DP-2DSA")
      (footprint "eagle-import:DF11-4DP-2DSA")
      (libsource (lib "eagle-import") (part "DF11-4DP-2DSA"))
    )
    (comp (ref "CN4")
      (value "DF11-4DP-2DSA")
      (footprint "eagle-import:DF11-4DP-2DSA")
      (libsource (lib "eagle-import") (part "DF11-4DP-2DSA"))
    )
    (comp (ref "D1")
      (value "1SS372")
      (footprint "eagle-import:SC70-3-R")
      (libsource (lib "eagle-import") (part "1SS372"))
    )
    (comp (ref "D2")
      (value "1SS372")
      (footprint "eagle-import:SC70-3-R")
      (libsource (lib "eagle-import") (part "1SS372"))
    )
    (comp (ref "D3")
      (value "1SS226")
      (footprint "eagle-import:SOT23")
      (libsource (lib "eagle-import") (part "1SS226"))
    )
    (comp (ref "F1")
      (value "RXEF050")
      (footprint "eagle-import:8X3_5.08")
      (libsource (lib "eagle-import") (part "RXEF050"))
    )
    (comp (ref "L1")
      (value "ACM4520-142")
      (footprint "eagle-import:ACM4520")
      (libsource (lib "eagle-import") (part "ACM4520-142"))
    )
    (comp (ref "L2")
      (value "ACM4520-142")
      (footprint "eagle-import:ACM4520")
      (libsource (lib "eagle-import") (part "ACM4520-142"))
    )
    (comp (ref "L3")
      (value "ACM4520-142")
      (footprint "eagle-import:ACM4520")
      (libsource (lib "eagle-import") (part "ACM4520-142"))
    )
    (comp (ref "L4")
      (value "ACM4520-142")
      (footprint "eagle-import:ACM4520")
      (libsource (lib "eagle-import") (part "ACM4520-142"))
    )
    (comp (ref "M1")
      (value "VAB-3-10")
      (footprint "eagle-import:VAB_3_10_CONTACT")
      (libsource (lib "eagle-import") (part "VAB-3-10"))
    )
    (comp (ref "R1")
      (value "100k")
      (footprint "eagle-import:RM1608")
      (libsource (lib "eagle-import") (part "RSMD1.6X0.8MM"))
    )
    (comp (ref "R2")
      (value "100k/POT")
      (footprint "eagle-import:CT-6")
      (libsource (lib "eagle-import") (part "R_POT"))
    )
    (comp (ref "R3")
      (value "270k")
      (footprint "eagle-import:RM1608")
      (libsource (lib "eagle-import") (part "RSMD1.6X0.8MM"))
    )
    (comp (ref "R4")
      (value "47k")
      (footprint "eagle-import:RM1608")
      (libsource (lib "eagle-import") (part "RSMD1.6X0.8MM"))
    )
    (comp (ref "R5")
      (value "43k")
      (footprint "eagle-import:RM1608")
      (libsource (lib "eagle-import") (part "RSMD1.6X0.8MM"))
    )
    (comp (ref "R6")
      (value "330k")
      (footprint "eagle-import:RM1608")
      (libsource (lib "eagle-import") (part "RSMD1.6X0.8MM"))
    )
    (comp (ref "R7")
      (value "270k")
      (footprint "eagle-import:RM1608")
      (libsource (lib "eagle-import") (part "RSMD1.6X0.8MM"))
    )
    (comp (ref "R8")
      (value "51k")
      (footprint "eagle-import:RM1608")
      (libsource (lib "eagle-import") (part "RSMD1.6X0.8MM"))
    )
    (comp (ref "R9")
      (value "51k")
      (footprint "eagle-import:RM1608")
      (libsource (lib "eagle-import") (part "RSMD1.6X0.8MM"))
    )
    (comp (ref "R10")
      (value "51k")
      (footprint "eagle-import:RM1608")
      (libsource (lib "eagle-import") (part "RSMD1.6X0.8MM"))
    )
    (comp (ref "R11")
      (value "51k")
      (footprint "eagle-import:RM1608")
      (libsource (lib "eagle-import") (part "RSMD1.6X0.8MM"))
    )
    (comp (ref "R12")
      (value "50k/POT")
      (footprint "eagle-import:CT-6")
      (libsource (lib "eagle-import") (part "R_POT"))
    )
    (comp (ref "R13")
      (value "51k")
      (footprint "eagle-import:RM1608")
      (libsource (lib "eagle-import") (part "RSMD1.6X0.8MM"))
    )
    (comp (ref "R14")
      (value "51k")
      (footprint "eagle-import:RM1608")
      (libsource (lib "eagle-import") (part "RSMD1.6X0.8MM"))
    )
    (comp (ref "R15")
      (value "51k")
      (footprint "eagle-import:RM1608")
      (libsource (lib "eagle-import") (part "RSMD1.6X0.8MM"))
    )
    (comp (ref "R16")
      (value "51k")
      (footprint "eagle-import:RM1608")
      (libsource (lib "eagle-import") (part "RSMD1.6X0.8MM"))
    )
    (comp (ref "R17")
      (value "9.1k")
      (footprint "eagle-import:RM1608")
      (libsource (lib "eagle-import") (part "RSMD1.6X0.8MM"))
    )
    (comp (ref "R18")
      (value "47/THICK")
      (footprint "eagle-import:RM1608")
      (libsource (lib "eagle-import") (part "RSMD1.6X0.8MM"))
    )
    (comp (ref "R19")
      (value "10k")
      (footprint "eagle-import:RM1608")
      (libsource (lib "eagle-import") (part "RSMD1.6X0.8MM"))
    )
    (comp (ref "R20")
      (value "10k")
      (footprint "eagle-import:RM1608")
      (libsource (lib "eagle-import") (part "RSMD1.6X0.8MM"))
    )
    (comp (ref "R21")
      (value "51k")
      (footprint "eagle-import:RM1608")
      (libsource (lib "eagle-import") (part "RSMD1.6X0.8MM"))
    )
    (comp (ref "R22")
      (value "0")
      (footprint "eagle-import:RM1608")
      (libsource (lib "eagle-import") (part "RSMD1.6X0.8MM"))
    )
    (comp (ref "R23")
      (value "9.1k")
      (footprint "eagle-import:RM1608")
      (libsource (lib "eagle-import") (part "RSMD1.6X0.8MM"))
    )
    (comp (ref "R24")
      (value "110k")
      (footprint "eagle-import:RM1608")
      (libsource (lib "eagle-import") (part "RSMD1.6X0.8MM"))
    )
    (comp (ref "R25")
      (value "11k")
      (footprint "eagle-import:RM1608")
      (libsource (lib "eagle-import") (part "RSMD1.6X0.8MM"))
    )
    (comp (ref "R26")
      (value "100k/THICK")
      (footprint "eagle-import:RM1608")
      (libsource (lib "eagle-import") (part "RSMD1.6X0.8MM"))
    )
    (comp (ref "R27")
      (value "0")
      (footprint "eagle-import:RM1608")
      (libsource (lib "eagle-import") (part "RSMD1.6X0.8MM"))
    )
    (comp (ref "R28")
      (value "0")
      (footprint "eagle-import:RM1608")
      (libsource (lib "eagle-import") (part "RSMD1.6X0.8MM"))
    )
    (comp (ref "R29")
      (value "10k")
      (footprint "eagle-import:RM1608")
      (libsource (lib "eagle-import") (part "RSMD1.6X0.8MM"))
    )
    (comp (ref "R30")
      (value "51k")
      (footprint "eagle-import:RM1608")
      (libsource (lib "eagle-import") (part "RSMD1.6X0.8MM"))
    )
    (comp (ref "R31")
      (value "51k")
      (footprint "eagle-import:RM1608")
      (libsource (lib "eagle-import") (part "RSMD1.6X0.8MM"))
    )
    (comp (ref "R32")
      (value "51k")
      (footprint "eagle-import:RM1608")
      (libsource (lib "eagle-import") (part "RSMD1.6X0.8MM"))
    )
    (comp (ref "R33")
      (value "0")
      (footprint "eagle-import:RM1608")
      (libsource (lib "eagle-import") (part "RSMD1.6X0.8MM"))
    )
    (comp (ref "R34")
      (value "1M/THICK")
      (footprint "eagle-import:RM1608")
      (libsource (lib "eagle-import") (part "RSMD1.6X0.8MM"))
    )
    (comp (ref "R35")
      (value "0")
      (footprint "eagle-import:RM1608")
      (libsource (lib "eagle-import") (part "RSMD1.6X0.8MM"))
    )
    (comp (ref "R36")
      (value "100k/THICK")
      (footprint "eagle-import:RM1608")
      (libsource (lib "eagle-import") (part "RSMD1.6X0.8MM"))
    )
    (comp (ref "R37")
      (value "51k")
      (footprint "eagle-import:RM1608")
      (libsource (lib "eagle-import") (part "RSMD1.6X0.8MM"))
    )
    (comp (ref "R38")
      (value "51k")
      (footprint "eagle-import:RM1608")
      (libsource (lib "eagle-import") (part "RSMD1.6X0.8MM"))
    )
    (comp (ref "R39")
      (value "47/THICK")
      (footprint "eagle-import:RM1608")
      (libsource (lib "eagle-import") (part "RSMD1.6X0.8MM"))
    )
    (comp (ref "R40")
      (value "51k")
      (footprint "eagle-import:RM1608")
      (libsource (lib "eagle-import") (part "RSMD1.6X0.8MM"))
    )
    (comp (ref "R41")
      (value "51k")
      (footprint "eagle-import:RM1608")
      (libsource (lib "eagle-import") (part "RSMD1.6X0.8MM"))
    )
    (comp (ref "R42")
      (value "68k")
      (footprint "eagle-import:RM1608")
      (libsource (lib "eagle-import") (part "RSMD1.6X0.8MM"))
    )
    (comp (ref "R43")
      (value "68k")
      (footprint "eagle-import:RM1608")
      (libsource (lib "eagle-import") (part "RSMD1.6X0.8MM"))
    )
    (comp (ref "R44")
      (value "51k")
      (footprint "eagle-import:RM1608")
      (libsource (lib "eagle-import") (part "RSMD1.6X0.8MM"))
    )
    (comp (ref "R45")
      (value "51k")
      (footprint "eagle-import:RM1608")
      (libsource (lib "eagle-import") (part "RSMD1.6X0.8MM"))
    )
    (comp (ref "R46")
      (value "30/THICK")
      (footprint "eagle-import:RM1608")
      (libsource (lib "eagle-import") (part "RSMD1.6X0.8MM"))
    )
    (comp (ref "R47")
      (value "100k")
      (footprint "eagle-import:RM1608")
      (libsource (lib "eagle-import") (part "RSMD1.6X0.8MM"))
    )
    (comp (ref "R48")
      (value "100k")
      (footprint "eagle-import:RM1608")
      (libsource (lib "eagle-import") (part "RSMD1.6X0.8MM"))
    )
    (comp (ref "R49")
      (value "5.6k")
      (footprint "eagle-import:RM1608")
      (libsource (lib "eagle-import") (part "RSMD1.6X0.8MM"))
    )
    (comp (ref "R50")
      (value "39k")
      (footprint "eagle-import:RM1608")
      (libsource (lib "eagle-import") (part "RSMD1.6X0.8MM"))
    )
    (comp (ref "R51")
      (value "100k")
      (footprint "eagle-import:RM1608")
      (libsource (lib "eagle-import") (part "RSMD1.6X0.8MM"))
    )
    (comp (ref "R52")
      (value "100k")
      (footprint "eagle-import:RM1608")
      (libsource (lib "eagle-import") (part "RSMD1.6X0.8MM"))
    )
    (comp (ref "R53")
      (value "10k")
      (footprint "eagle-import:RM1608")
      (libsource (lib "eagle-import") (part "RSMD1.6X0.8MM"))
    )
    (comp (ref "R54")
      (value "10k")
      (footprint "eagle-import:RM1608")
      (libsource (lib "eagle-import") (part "RSMD1.6X0.8MM"))
    )
    (comp (ref "R55")
      (value "2k/0.05%/10ppm")
      (footprint "eagle-import:RM1608")
      (libsource (lib "eagle-import") (part "RSMD1.6X0.8MM"))
    )
    (comp (ref "R56")
      (value "100/0.05%/5ppm")
      (footprint "eagle-import:0204_5")
      (libsource (lib "eagle-import") (part "R0204/5"))
    )
    (comp (ref "R57")
      (value "15k/0.05%/10ppm")
      (footprint "eagle-import:RM1608")
      (libsource (lib "eagle-import") (part "RSMD1.6X0.8MM"))
    )
    (comp (ref "R58")
      (value "620/THICK")
      (footprint "eagle-import:RM1608")
      (libsource (lib "eagle-import") (part "RSMD1.6X0.8MM"))
    )
    (comp (ref "TP1")
      (value "TP-LC3G")
      (footprint "eagle-import:TP_TH_0R9MM")
      (libsource (lib "eagle-import") (part "TP-LC3G"))
    )
    (comp (ref "TP2")
      (value "TP-LC3G")
      (footprint "eagle-import:TP_TH_0R9MM")
      (libsource (lib "eagle-import") (part "TP-LC3G"))
    )
    (comp (ref "TP3")
      (value "TP-LC3G")
      (footprint "eagle-import:TP_TH_0R9MM")
      (libsource (lib "eagle-import") (part "TP-LC3G"))
    )
    (comp (ref "TP4")
      (value "TP-LC3G")
      (footprint "eagle-import:TP_TH_0R9MM")
      (libsource (lib "eagle-import") (part "TP-LC3G"))
    )
    (comp (ref "TP5")
      (value "TP-LC3G")
      (footprint "eagle-import:TP_TH_0R9MM")
      (libsource (lib "eagle-import") (part "TP-LC3G"))
    )
    (comp (ref "TP6")
      (value "TP-LC3G")
      (footprint "eagle-import:TP_TH_0R9MM")
      (libsource (lib "eagle-import") (part "TP-LC3G"))
    )
    (comp (ref "TP7")
      (value "TP-LC3G")
      (footprint "eagle-import:TP_TH_0R9MM")
      (libsource (lib "eagle-import") (part "TP-LC3G"))
    )
    (comp (ref "TP8")
      (value "TP-LC3G")
      (footprint "eagle-import:TP_TH_0R9MM")
      (libsource (lib "eagle-import") (part "TP-LC3G"))
    )
    (comp (ref "TP9")
      (value "TP-LC3G")
      (footprint "eagle-import:TP_TH_0R9MM")
      (libsource (lib "eagle-import") (part "TP-LC3G"))
    )
    (comp (ref "U1")
      (value "OPA2344EA")
      (footprint "eagle-import:MSO8_AEL")
      (libsource (lib "eagle-import") (part "OPA2344EA"))
    )
    (comp (ref "U2")
      (value "OPA2344EA")
      (footprint "eagle-import:MSO8_AEL")
      (libsource (lib "eagle-import") (part "OPA2344EA"))
    )
    (comp (ref "U3")
      (value "TS5A23159DGS")
      (footprint "eagle-import:MSOP10")
      (libsource (lib "eagle-import") (part "TS5A23159DGS"))
    )
    (comp (ref "U4")
      (value "TPS79933DDC")
      (footprint "eagle-import:SOT-23-5")
      (libsource (lib "eagle-import") (part "TPS799DDC33"))
    )
    (comp (ref "U5")
      (value "OPA2344EA")
      (footprint "eagle-import:MSO8_AEL")
      (libsource (lib "eagle-import") (part "OPA2344EA"))
    )
    (comp (ref "U6")
      (value "TPS3808G01DBV")
      (footprint "eagle-import:SOT-23")
      (libsource (lib "eagle-import") (part "TPS3808GDBV01"))
    )
    (comp (ref "U7")
      (value "NJU7108F3")
      (footprint "eagle-import:SC88A")
      (libsource (lib "eagle-import") (part "NJU7108F3"))
    )
    (comp (ref "U8")
      (value "OPA2314AIDGK")
      (footprint "eagle-import:MSO8_AEL")
      (libsource (lib "eagle-import") (part "OPA2344EA"))
    )
    (comp (ref "U9")
      (value "TS5A23159DGS")
      (footprint "eagle-import:MSOP10")
      (libsource (lib "eagle-import") (part "TS5A23159DGS"))
    )
    (comp (ref "U10")
      (value "74VHC4052AFT")
      (footprint "eagle-import:TSSOP16-P-044-065A")
      (libsource (lib "eagle-import") (part "744052AFTVHC"))
    )
    (comp (ref "U11")
      (value "AD8227ARZ")
      (footprint "eagle-import:SO8_AEL")
      (libsource (lib "eagle-import") (part "AD8227RZA"))
    )
    (comp (ref "C28")
      (value "0.1u/16V")
      (footprint "eagle-import:CM1005")
      (libsource (lib "eagle-import") (part "CSMD1.0X0.5MM"))
    )
    (comp (ref "C29")
      (value "0.1u/16V")
      (footprint "eagle-import:CM1005")
      (libsource (lib "eagle-import") (part "CSMD1.0X0.5MM"))
    )
    (comp (ref "C30")
      (value "0.1u/16V")
      (footprint "eagle-import:CM1005")
      (libsource (lib "eagle-import") (part "CSMD1.0X0.5MM"))
    )
    (comp (ref "C31")
      (value "0.1u/16V")
      (footprint "eagle-import:CM1005")
      (libsource (lib "eagle-import") (part "CSMD1.0X0.5MM"))
    )
    (comp (ref "C32")
      (value "0.1u/16V")
      (footprint "eagle-import:CM1005")
      (libsource (lib "eagle-import") (part "CSMD1.0X0.5MM"))
    )
    (comp (ref "C33")
      (value "0.1u/16V")
      (footprint "eagle-import:CM1005")
      (libsource (lib "eagle-import") (part "CSMD1.0X0.5MM"))
    )
    (comp (ref "C34")
      (value "0.1u/16V")
      (footprint "eagle-import:CM1005")
      (libsource (lib "eagle-import") (part "CSMD1.0X0.5MM"))
    )
    (comp (ref "C35")
      (value "0.1u/16V")
      (footprint "eagle-import:CM1005")
      (libsource (lib "eagle-import") (part "CSMD1.0X0.5MM"))
    )
    (comp (ref "C36")
      (value "0.1u/16V")
      (footprint "eagle-import:CM1005")
      (libsource (lib "eagle-import") (part "CSMD1.0X0.5MM"))
    )
    (comp (ref "C37")
      (value "0.1u/16V")
      (footprint "eagle-import:CM1005")
      (libsource (lib "eagle-import") (part "CSMD1.0X0.5MM"))
    )
    (comp (ref "C38")
      (value "0.1u/16V")
      (footprint "eagle-import:CM1005")
      (libsource (lib "eagle-import") (part "CSMD1.0X0.5MM"))
    )
    (comp (ref "C39")
      (value "0.1u/16V")
      (footprint "eagle-import:CM1005")
      (libsource (lib "eagle-import") (part "CSMD1.0X0.5MM"))
    )
    (comp (ref "C40")
      (value "0.1u/16V")
      (footprint "eagle-import:CM1005")
      (libsource (lib "eagle-import") (part "CSMD1.0X0.5MM"))
    )
    (comp (ref "C41")
      (value "0.1u/16V")
      (footprint "eagle-import:CM1005")
      (libsource (lib "eagle-import") (part "CSMD1.0X0.5MM"))
    )
    (comp (ref "U12")
      (value "MAX4617CUE+")
      (footprint "eagle-import:TSSOP16_AEL")
      (libsource (lib "eagle-import") (part "MAX4617CUE+"))
    )
    (comp (ref "U13")
      (value "MAX4617CUE+")
      (footprint "eagle-import:TSSOP16_AEL")
      (libsource (lib "eagle-import") (part "MAX4617CUE+"))
    )
    (comp (ref "U14")
      (value "MAX4617CUE+")
      (footprint "eagle-import:TSSOP16_AEL")
      (libsource (lib "eagle-import") (part "MAX4617CUE+"))
    )
    (comp (ref "U15")
      (value "MAX4617CUE+")
      (footprint "eagle-import:TSSOP16_AEL")
      (libsource (lib "eagle-import") (part "MAX4617CUE+"))
    )
    (comp (ref "U16")
      (value "MAX4617CUE+")
      (footprint "eagle-import:TSSOP16_AEL")
      (libsource (lib "eagle-import") (part "MAX4617CUE+"))
    )
    (comp (ref "U17")
      (value "MAX4617CUE+")
      (footprint "eagle-import:TSSOP16_AEL")
      (libsource (lib "eagle-import") (part "MAX4617CUE+"))
    )
    (comp (ref "U18")
      (value "MAX4617CUE+")
      (footprint "eagle-import:TSSOP16_AEL")
      (libsource (lib "eagle-import") (part "MAX4617CUE+"))
    )
    (comp (ref "U19")
      (value "MAX4617CUE+")
      (footprint "eagle-import:TSSOP16_AEL")
      (libsource (lib "eagle-import") (part "MAX4617CUE+"))
    )
    (comp (ref "U20")
      (value "MAX4617CUE+")
      (footprint "eagle-import:TSSOP16_AEL")
      (libsource (lib "eagle-import") (part "MAX4617CUE+"))
    )
    (comp (ref "U21")
      (value "MAX4617CUE+")
      (footprint "eagle-import:TSSOP16_AEL")
      (libsource (lib "eagle-import") (part "MAX4617CUE+"))
    )
    (comp (ref "U22")
      (value "MAX4617CUE+")
      (footprint "eagle-import:TSSOP16_AEL")
      (libsource (lib "eagle-import") (part "MAX4617CUE+"))
    )
    (comp (ref "U23")
      (value "MAX4617CUE+")
      (footprint "eagle-import:TSSOP16_AEL")
      (libsource (lib "eagle-import") (part "MAX4617CUE+"))
    )
    (comp (ref "U24")
      (value "MAX4617CUE+")
      (footprint "eagle-import:TSSOP16_AEL")
      (libsource (lib "eagle-import") (part "MAX4617CUE+"))
    )
    (comp (ref "U25")
      (value "MAX4617CUE+")
      (footprint "eagle-import:TSSOP16_AEL")
      (libsource (lib "eagle-import") (part "MAX4617CUE+"))
    )
    (comp (ref "CN5")
      (value "DF11-4DP-2DSA")
      (footprint "eagle-import:DF11-4DP-2DSA")
      (libsource (lib "eagle-import") (part "DF11-4DP-2DSA"))
    )
    (comp (ref "CN6")
      (value "DF11-4DP-2DSA")
      (footprint "eagle-import:DF11-4DP-2DSA")
      (libsource (lib "eagle-import") (part "DF11-4DP-2DSA"))
    )
    (comp (ref "CN7")
      (value "DF11-14DP-2DSA")
      (footprint "eagle-import:DF11-14DP-2DSA")
      (libsource (lib "eagle-import") (part "DF11-14DP-2DSA"))
    )
    (comp (ref "CN8")
      (value "PH-2X4S")
      (footprint "eagle-import:PIN_HEADER_8PIN")
      (libsource (lib "eagle-import") (part "PH-2X4S"))
    )
    (comp (ref "CN9")
      (value "DF11-4DP-2DSA")
      (footprint "eagle-import:DF11-4DP-2DSA")
      (libsource (lib "eagle-import") (part "DF11-4DP-2DSA"))
    )
    (comp (ref "CN10")
      (value "826646-4")
      (footprint "eagle-import:PIN_HEADER_4PIN")
      (libsource (lib "eagle-import") (part "PH-1X4"))
    )
    (comp (ref "CN11")
      (value "826646-4")
      (footprint "eagle-import:PIN_HEADER_4PIN")
      (libsource (lib "eagle-import") (part "PH-1X4"))
    )
    (comp (ref "CN12")
      (value "BNC_ANGLE")
      (footprint "eagle-import:BNC_F_ANGLE")
      (libsource (lib "eagle-import") (part "BNC_ANGLE"))
    )
    (comp (ref "CN13")
      (value "BNC_ANGLE")
      (footprint "eagle-import:BNC_F_ANGLE")
      (libsource (lib "eagle-import") (part "BNC_ANGLE"))
    )
    (comp (ref "CN14")
      (value "BNC_ANGLE")
      (footprint "eagle-import:BNC_F_ANGLE")
      (libsource (lib "eagle-import") (part "BNC_ANGLE"))
    )
    (comp (ref "CN15")
      (value "DF11-4DP-2DSA")
      (footprint "eagle-import:DF11-4DP-2DSA")
      (libsource (lib "eagle-import") (part "DF11-4DP-2DSA"))
    )
    (comp (ref "CN16")
      (value "PCS-XE50LFD")
      (footprint "eagle-import:50LFD2")
      (libsource (lib "eagle-import") (part "PCS-XE50LFD"))
    )
    (comp (ref "CN17")
      (value "PCS-XE50LFD")
      (footprint "eagle-import:50LFD2")
      (libsource (lib "eagle-import") (part "PCS-XE50LFD"))
    )
    (comp (ref "D4")
      (value "WP934EW/GD")
      (footprint "eagle-import:L-93A8CB")
      (libsource (lib "eagle-import") (part "L-93A8CB/1GD"))
    )
    (comp (ref "D5")
      (value "WP934CB/ID")
      (footprint "eagle-import:L-93A8CB")
      (libsource (lib "eagle-import") (part "L-93A8CB/1ID"))
    )
    (comp (ref "D6")
      (value "WP934EW/GD")
      (footprint "eagle-import:L-93A8CB")
      (libsource (lib "eagle-import") (part "L-93A8CB/1GD"))
    )
    (comp (ref "F2")
      (value "RXEF050")
      (footprint "eagle-import:8X3_5.08")
      (libsource (lib "eagle-import") (part "RXEF050"))
    )
    (comp (ref "M2")
      (value "VAB-3-10")
      (footprint "eagle-import:VAB_3_10_CONTACT")
      (libsource (lib "eagle-import") (part "VAB-3-10"))
    )
    (comp (ref "M3")
      (value "VAB-3-10")
      (footprint "eagle-import:VAB_3_10_CONTACT")
      (libsource (lib "eagle-import") (part "VAB-3-10"))
    )
    (comp (ref "R59")
      (value "680/LEAD")
      (footprint "eagle-import:0207_2V")
      (libsource (lib "eagle-import") (part "R0207/2V"))
    )
    (comp (ref "R60")
      (value "680/LEAD")
      (footprint "eagle-import:0207_2V")
      (libsource (lib "eagle-import") (part "R0207/2V"))
    )
    (comp (ref "R61")
      (value "680/LEAD")
      (footprint "eagle-import:0207_2V")
      (libsource (lib "eagle-import") (part "R0207/2V"))
    )
    (comp (ref "SW1")
      (value "A-12AV")
      (footprint "eagle-import:A-12_")
      (libsource (lib "eagle-import") (part "A-1V2A"))
    )
    (comp (ref "SW2")
      (value "A-12AV")
      (footprint "eagle-import:A-12_")
      (libsource (lib "eagle-import") (part "A-1V2A"))
    )
    (comp (ref "SW3")
      (value "A-12AV")
      (footprint "eagle-import:A-12_")
      (libsource (lib "eagle-import") (part "A-1V2A"))
    )
    (comp (ref "SW4")
      (value "A-12AV")
      (footprint "eagle-import:A-12_")
      (libsource (lib "eagle-import") (part "A-1V2A"))
    )
  )
  (nets
    (net (code "1") (name "0V") (class "Default")
      (node (ref "C1") (pin "2") (pinfunction "2_2") (pintype "passive"))
      (node (ref "C17") (pin "2") (pinfunction "2_2") (pintype "passive"))
      (node (ref "C23") (pin "POS") (pinfunction "POS_POS") (pintype "passive"))
      (node (ref "C3") (pin "1") (pinfunction "1_1") (pintype "passive"))
      (node (ref "C5") (pin "1") (pinfunction "1_1") (pintype "passive"))
      (node (ref "D3") (pin "1") (pinfunction "A_1") (pintype "passive"))
      (node (ref "D3") (pin "2") (pinfunction "C_2") (pintype "passive"))
      (node (ref "R1") (pin "1") (pinfunction "1_1") (pintype "passive"))
      (node (ref "R13") (pin "2") (pinfunction "2_2") (pintype "passive"))
      (node (ref "R15") (pin "2") (pinfunction "2_2") (pintype "passive"))
      (node (ref "R21") (pin "1") (pinfunction "1_1") (pintype "passive"))
      (node (ref "R29") (pin "1") (pinfunction "1_1") (pintype "passive"))
      (node (ref "R40") (pin "1") (pinfunction "1_1") (pintype "passive"))
      (node (ref "R41") (pin "1") (pinfunction "1_1") (pintype "passive"))
      (node (ref "R46") (pin "2") (pinfunction "2_2") (pintype "passive"))
      (node (ref "TP7") (pin "1") (pinfunction "MP_1") (pintype "passive"))
      (node (ref "U1") (pin "5") (pinfunction "+IN_5") (pintype "input"))
      (node (ref "U8") (pin "5") (pinfunction "+IN_5") (pintype "input"))
    )
    (net (code "2") (name "AGND") (class "Default")
      (node (ref "C12") (pin "2") (pinfunction "2_2") (pintype "passive"))
      (node (ref "C13") (pin "2") (pinfunction "2_2") (pintype "passive"))
      (node (ref "C15") (pin "1") (pinfunction "1_1") (pintype "passive"))
      (node (ref "C16") (pin "2") (pinfunction "2_2") (pintype "passive"))
      (node (ref "C18") (pin "2") (pinfunction "2_2") (pintype "passive"))
      (node (ref "C20") (pin "2") (pinfunction "2_2") (pintype "passive"))
      (node (ref "C21") (pin "2") (pinfunction "2_2") (pintype "passive"))
      (node (ref "C22") (pin "2") (pinfunction "2_2") (pintype "passive"))
      (node (ref "C23") (pin "NEG") (pinfunction "NEG_NEG") (pintype "passive"))
      (node (ref "C24") (pin "2") (pinfunction "2_2") (pintype "passive"))
      (node (ref "C25") (pin "2") (pinfunction "2_2") (pintype "passive"))
      (node (ref "C26") (pin "1") (pinfunction "1_1") (pintype "passive"))
      (node (ref "C27") (pin "2") (pinfunction "2_2") (pintype "passive"))
      (node (ref "C28") (pin "2") (pinfunction "2_2") (pintype "passive"))
      (node (ref "C29") (pin "2") (pinfunction "2_2") (pintype "passive"))
      (node (ref "C30") (pin "2") (pinfunction "2_2") (pintype "passive"))
      (node (ref "C31") (pin "2") (pinfunction "2_2") (pintype "passive"))
      (node (ref "C32") (pin "2") (pinfunction "2_2") (pintype "passive"))
      (node (ref "C33") (pin "2") (pinfunction "2_2") (pintype "passive"))
      (node (ref "C34") (pin "2") (pinfunction "2_2") (pintype "passive"))
      (node (ref "C35") (pin "2") (pinfunction "2_2") (pintype "passive"))
      (node (ref "C36") (pin "2") (pinfunction "2_2") (pintype "passive"))
      (node (ref "C37") (pin "2") (pinfunction "2_2") (pintype "passive"))
      (node (ref "C38") (pin "2") (pinfunction "2_2") (pintype "passive"))
      (node (ref "C39") (pin "2") (pinfunction "2_2") (pintype "passive"))
      (node (ref "C40") (pin "2") (pinfunction "2_2") (pintype "passive"))
      (node (ref "C41") (pin "2") (pinfunction "2_2") (pintype "passive"))
      (node (ref "C8") (pin "NEG") (pinfunction "NEG_NEG") (pintype "passive"))
      (node (ref "C9") (pin "2") (pinfunction "2_2") (pintype "passive"))
      (node (ref "CN16") (pin "51") (pinfunction "G1_51") (pintype "bidirectional"))
      (node (ref "CN16") (pin "52") (pinfunction "G2_52") (pintype "bidirectional"))
      (node (ref "CN17") (pin "51") (pinfunction "G1_51") (pintype "bidirectional"))
      (node (ref "CN17") (pin "52") (pinfunction "G2_52") (pintype "bidirectional"))
      (node (ref "CN4") (pin "3") (pinfunction "3_3") (pintype "bidirectional"))
      (node (ref "CN4") (pin "4") (pinfunction "4_4") (pintype "bidirectional"))
      (node (ref "D1") (pin "1") (pinfunction "A_1") (pintype "passive"))
      (node (ref "D2") (pin "1") (pinfunction "A_1") (pintype "passive"))
      (node (ref "L3") (pin "2") (pinfunction "3_2") (pintype "passive"))
      (node (ref "R32") (pin "1") (pinfunction "1_1") (pintype "passive"))
      (node (ref "R43") (pin "1") (pinfunction "1_1") (pintype "passive"))
      (node (ref "TP9") (pin "1") (pinfunction "MP_1") (pintype "passive"))
      (node (ref "U1") (pin "4") (pinfunction "V-_4") (pintype "power_in"))
      (node (ref "U10") (pin "6") (pinfunction "INH_6") (pintype "input"))
      (node (ref "U10") (pin "7") (pinfunction "GND_7") (pintype "power_in"))
      (node (ref "U10") (pin "8") (pinfunction "GND_8") (pintype "input"))
      (node (ref "U11") (pin "5") (pinfunction "V-_5") (pintype "power_in"))
      (node (ref "U12") (pin "8") (pinfunction "V-_8") (pintype "power_in"))
      (node (ref "U13") (pin "8") (pinfunction "V-_8") (pintype "power_in"))
      (node (ref "U14") (pin "8") (pinfunction "V-_8") (pintype "power_in"))
      (node (ref "U15") (pin "8") (pinfunction "V-_8") (pintype "power_in"))
      (node (ref "U16") (pin "8") (pinfunction "V-_8") (pintype "power_in"))
      (node (ref "U17") (pin "8") (pinfunction "V-_8") (pintype "power_in"))
      (node (ref "U18") (pin "8") (pinfunction "V-_8") (pintype "power_in"))
      (node (ref "U19") (pin "8") (pinfunction "V-_8") (pintype "power_in"))
      (node (ref "U2") (pin "4") (pinfunction "V-_4") (pintype "power_in"))
      (node (ref "U20") (pin "8") (pinfunction "V-_8") (pintype "power_in"))
      (node (ref "U21") (pin "8") (pinfunction "V-_8") (pintype "power_in"))
      (node (ref "U22") (pin "8") (pinfunction "V-_8") (pintype "power_in"))
      (node (ref "U23") (pin "8") (pinfunction "V-_8") (pintype "power_in"))
      (node (ref "U24") (pin "8") (pinfunction "V-_8") (pintype "power_in"))
      (node (ref "U25") (pin "8") (pinfunction "V-_8") (pintype "power_in"))
      (node (ref "U3") (pin "3") (pinfunction "V-_3") (pintype "power_in"))
      (node (ref "U4") (pin "2") (pinfunction "GND_2") (pintype "passive"))
      (node (ref "U5") (pin "4") (pinfunction "V-_4") (pintype "power_in"))
      (node (ref "U7") (pin "2") (pinfunction "V-_2") (pintype "power_in"))
      (node (ref "U8") (pin "4") (pinfunction "V-_4") (pintype "power_in"))
      (node (ref "U9") (pin "3") (pinfunction "V-_3") (pintype "power_in"))
    )
    (net (code "3") (name "AMP_0") (class "Default")
      (node (ref "U10") (pin "10") (pinfunction "A_10") (pintype "input"))
      (node (ref "U27") (pin "19") (pinfunction "1-14_19") (pintype "bidirectional"))
    )
    (net (code "4") (name "AMP_1") (class "Default")
      (node (ref "U10") (pin "9") (pinfunction "B_9") (pintype "input"))
      (node (ref "U27") (pin "20") (pinfunction "1-15_20") (pintype "bidirectional"))
    )
    (net (code "5") (name "ANALOG{slash}~{DDS}") (class "Default")
      (node (ref "R70") (pin "1") (pinfunction "1_1") (pintype "passive"))
      (node (ref "U3") (pin "5") (pinfunction "IN_5") (pintype "input"))
    )
    (net (code "6") (name "BATT+") (class "Default")
      (node (ref "F1") (pin "2") (pinfunction "2_2") (pintype "passive"))
      (node (ref "L3") (pin "4") (pinfunction "2_4") (pintype "passive"))
      (node (ref "L5") (pin "1") (pinfunction "1_1") (pintype "passive"))
    )
    (net (code "7") (name "BATT-") (class "Default")
      (node (ref "CN3") (pin "3") (pinfunction "3_3") (pintype "bidirectional"))
      (node (ref "CN3") (pin "4") (pinfunction "4_4") (pintype "bidirectional"))
      (node (ref "L3") (pin "3") (pinfunction "4_3") (pintype "passive"))
      (node (ref "L5") (pin "2") (pinfunction "3_2") (pintype "passive"))
    )
    (net (code "8") (name "CH_0") (class "Default")
      (node (ref "R68") (pin "1") (pinfunction "1_1") (pintype "passive"))
      (node (ref "U12") (pin "11") (pinfunction "A_11") (pintype "input"))
      (node (ref "U13") (pin "11") (pinfunction "A_11") (pintype "input"))
      (node (ref "U14") (pin "11") (pinfunction "A_11") (pintype "input"))
      (node (ref "U15") (pin "11") (pinfunction "A_11") (pintype "input"))
      (node (ref "U16") (pin "11") (pinfunction "A_11") (pintype "input"))
      (node (ref "U17") (pin "11") (pinfunction "A_11") (pintype "input"))
      (node (ref "U18") (pin "11") (pinfunction "A_11") (pintype "input"))
      (node (ref "U19") (pin "11") (pinfunction "A_11") (pintype "input"))
      (node (ref "U20") (pin "11") (pinfunction "A_11") (pintype "input"))
      (node (ref "U21") (pin "11") (pinfunction "A_11") (pintype "input"))
      (node (ref "U22") (pin "11") (pinfunction "A_11") (pintype "input"))
      (node (ref "U23") (pin "11") (pinfunction "A_11") (pintype "input"))
      (node (ref "U24") (pin "11") (pinfunction "A_11") (pintype "input"))
      (node (ref "U25") (pin "11") (pinfunction "A_11") (pintype "input"))
    )
    (net (code "9") (name "CH_1") (class "Default")
      (node (ref "R69") (pin "1") (pinfunction "1_1") (pintype "passive"))
      (node (ref "U12") (pin "10") (pinfunction "B_10") (pintype "input"))
      (node (ref "U13") (pin "10") (pinfunction "B_10") (pintype "input"))
      (node (ref "U14") (pin "10") (pinfunction "B_10") (pintype "input"))
      (node (ref "U15") (pin "10") (pinfunction "B_10") (pintype "input"))
      (node (ref "U16") (pin "10") (pinfunction "B_10") (pintype "input"))
      (node (ref "U17") (pin "10") (pinfunction "B_10") (pintype "input"))
      (node (ref "U18") (pin "10") (pinfunction "B_10") (pintype "input"))
      (node (ref "U19") (pin "10") (pinfunction "B_10") (pintype "input"))
      (node (ref "U20") (pin "10") (pinfunction "B_10") (pintype "input"))
      (node (ref "U21") (pin "10") (pinfunction "B_10") (pintype "input"))
      (node (ref "U22") (pin "10") (pinfunction "B_10") (pintype "input"))
      (node (ref "U23") (pin "10") (pinfunction "B_10") (pintype "input"))
      (node (ref "U24") (pin "10") (pinfunction "B_10") (pintype "input"))
      (node (ref "U25") (pin "10") (pinfunction "B_10") (pintype "input"))
    )
    (net (code "10") (name "CH_2") (class "Default")
      (node (ref "R67") (pin "1") (pinfunction "1_1") (pintype "passive"))
      (node (ref "U12") (pin "9") (pinfunction "C_9") (pintype "input"))
      (node (ref "U13") (pin "9") (pinfunction "C_9") (pintype "input"))
      (node (ref "U14") (pin "9") (pinfunction "C_9") (pintype "input"))
      (node (ref "U15") (pin "9") (pinfunction "C_9") (pintype "input"))
      (node (ref "U16") (pin "9") (pinfunction "C_9") (pintype "input"))
      (node (ref "U17") (pin "9") (pinfunction "C_9") (pintype "input"))
      (node (ref "U18") (pin "9") (pinfunction "C_9") (pintype "input"))
      (node (ref "U19") (pin "9") (pinfunction "C_9") (pintype "input"))
      (node (ref "U20") (pin "9") (pinfunction "C_9") (pintype "input"))
      (node (ref "U21") (pin "9") (pinfunction "C_9") (pintype "input"))
      (node (ref "U22") (pin "9") (pinfunction "C_9") (pintype "input"))
      (node (ref "U23") (pin "9") (pinfunction "C_9") (pintype "input"))
      (node (ref "U24") (pin "9") (pinfunction "C_9") (pintype "input"))
      (node (ref "U25") (pin "9") (pinfunction "C_9") (pintype "input"))
    )
    (net (code "11") (name "CURRENT_MON") (class "Default")
      (node (ref "R58") (pin "1") (pinfunction "1_1") (pintype "passive"))
      (node (ref "U11") (pin "7") (pinfunction "OUT_7") (pintype "output"))
    )
    (net (code "12") (name "DGND") (class "Default")
      (node (ref "C10") (pin "2") (pinfunction "2_2") (pintype "passive"))
      (node (ref "C11") (pin "2") (pinfunction "2_2") (pintype "passive"))
      (node (ref "C42") (pin "2") (pinfunction "2_2") (pintype "passive"))
      (node (ref "C43") (pin "2") (pinfunction "2_2") (pintype "passive"))
      (node (ref "C44") (pin "2") (pinfunction "2_2") (pintype "passive"))
      (node (ref "C45") (pin "2") (pinfunction "2_2") (pintype "passive"))
      (node (ref "C46") (pin "NEG") (pinfunction "NEG_NEG") (pintype "passive"))
      (node (ref "C47") (pin "2") (pinfunction "2_2") (pintype "passive"))
      (node (ref "C48") (pin "1") (pinfunction "1_1") (pintype "passive"))
      (node (ref "C49") (pin "1") (pinfunction "1_1") (pintype "passive"))
      (node (ref "C50") (pin "1") (pinfunction "1_1") (pintype "passive"))
      (node (ref "C51") (pin "1") (pinfunction "1_1") (pintype "passive"))
      (node (ref "C52") (pin "2") (pinfunction "2_2") (pintype "passive"))
      (node (ref "C53") (pin "2") (pinfunction "2_2") (pintype "passive"))
      (node (ref "C54") (pin "2") (pinfunction "2_2") (pintype "passive"))
      (node (ref "C55") (pin "2") (pinfunction "2_2") (pintype "passive"))
      (node (ref "C56") (pin "2") (pinfunction "2_2") (pintype "passive"))
      (node (ref "C57") (pin "2") (pinfunction "2_2") (pintype "passive"))
      (node (ref "C58") (pin "2") (pinfunction "2_2") (pintype "passive"))
      (node (ref "C59") (pin "2") (pinfunction "2_2") (pintype "passive"))
      (node (ref "C60") (pin "2") (pinfunction "2_2") (pintype "passive"))
      (node (ref "C61") (pin "2") (pinfunction "2_2") (pintype "passive"))
      (node (ref "C62") (pin "2") (pinfunction "2_2") (pintype "passive"))
      (node (ref "CN10") (pin "4") (pinfunction "4_4") (pintype "bidirectional"))
      (node (ref "CN11") (pin "4") (pinfunction "4_4") (pintype "bidirectional"))
      (node (ref "CN18") (pin "10") (pinfunction "10_10") (pintype "bidirectional"))
      (node (ref "CN18") (pin "2") (pinfunction "2_2") (pintype "bidirectional"))
      (node (ref "CN19") (pin "10") (pinfunction "10_10") (pintype "bidirectional"))
      (node (ref "CN19") (pin "2") (pinfunction "2_2") (pintype "bidirectional"))
      (node (ref "CN19") (pin "4") (pinfunction "4_4") (pintype "bidirectional"))
      (node (ref "CN20") (pin "2") (pinfunction "2_2") (pintype "bidirectional"))
      (node (ref "CN20") (pin "8") (pinfunction "8_8") (pintype "bidirectional"))
      (node (ref "CN7") (pin "2") (pinfunction "2_2") (pintype "bidirectional"))
      (node (ref "D4") (pin "C") (pinfunction "K1_C") (pintype "passive"))
      (node (ref "L5") (pin "3") (pinfunction "4_3") (pintype "passive"))
      (node (ref "M1") (pin "CASE1") (pinfunction "P$1_CASE1") (pintype "bidirectional"))
      (node (ref "M2") (pin "CASE1") (pinfunction "P$1_CASE1") (pintype "bidirectional"))
      (node (ref "M3") (pin "CASE1") (pinfunction "P$1_CASE1") (pintype "bidirectional"))
      (node (ref "R25") (pin "1") (pinfunction "1_1") (pintype "passive"))
      (node (ref "R65") (pin "1") (pinfunction "1_1") (pintype "passive"))
      (node (ref "R77") (pin "1") (pinfunction "1_1") (pintype "passive"))
      (node (ref "SW1") (pin "7") (pinfunction "BRACKET_7") (pintype "passive"))
      (node (ref "SW1") (pin "8") (pinfunction "BRACKET_8") (pintype "passive"))
      (node (ref "SW2") (pin "3") (pinfunction "NC_3") (pintype "passive"))
      (node (ref "SW2") (pin "7") (pinfunction "BRACKET_7") (pintype "passive"))
      (node (ref "SW2") (pin "8") (pinfunction "BRACKET_8") (pintype "passive"))
      (node (ref "SW3") (pin "3") (pinfunction "NC_3") (pintype "passive"))
      (node (ref "SW3") (pin "7") (pinfunction "BRACKET_7") (pintype "passive"))
      (node (ref "SW3") (pin "8") (pinfunction "BRACKET_8") (pintype "passive"))
      (node (ref "SW4") (pin "3") (pinfunction "NC_3") (pintype "passive"))
      (node (ref "SW4") (pin "7") (pinfunction "BRACKET_7") (pintype "passive"))
      (node (ref "SW4") (pin "8") (pinfunction "BRACKET_8") (pintype "passive"))
      (node (ref "TP15") (pin "1") (pinfunction "MP_1") (pintype "passive"))
      (node (ref "U26") (pin "2") (pinfunction "GND_2") (pintype "passive"))
      (node (ref "U27") (pin "1") (pinfunction "GND_1_1") (pintype "power_in"))
      (node (ref "U27") (pin "10") (pinfunction "GND_2_10") (pintype "power_in"))
      (node (ref "U27") (pin "11") (pinfunction "GND_3_11") (pintype "power_in"))
      (node (ref "U27") (pin "32") (pinfunction "GND_4_32") (pintype "power_in"))
      (node (ref "U27") (pin "43") (pinfunction "1-32/DEV_OE_43") (pintype "bidirectional"))
      (node (ref "U27") (pin "44") (pinfunction "1-33/~{DEV_CLR}_44") (pintype "bidirectional"))
      (node (ref "U27") (pin "46") (pinfunction "GND_5_46") (pintype "power_in"))
      (node (ref "U27") (pin "60") (pinfunction "GND_6_60") (pintype "power_in"))
      (node (ref "U27") (pin "65") (pinfunction "GND_7_65") (pintype "power_in"))
      (node (ref "U27") (pin "79") (pinfunction "GND_8_79") (pintype "power_in"))
      (node (ref "U27") (pin "93") (pinfunction "GND_9_93") (pintype "power_in"))
      (node (ref "U28") (pin "2") (pinfunction "GND_2") (pintype "passive"))
      (node (ref "U29") (pin "10") (pinfunction "GND_10") (pintype "power_in"))
      (node (ref "U30") (pin "2") (pinfunction "C_2") (pintype "passive"))
      (node (ref "U6") (pin "2") (pinfunction "GND_2") (pintype "power_in"))
    )
    (net (code "13") (name "DISP1") (class "Default")
      (node (ref "TP14") (pin "P$1") (pinfunction "MP_P$1") (pintype "passive"))
      (node (ref "U27") (pin "56") (pinfunction "2-5_56") (pintype "bidirectional"))
      (node (ref "U29") (pin "9") (pinfunction "A8_9") (pintype "input"))
    )
    (net (code "14") (name "DISP2") (class "Default")
      (node (ref "TP13") (pin "P$1") (pinfunction "MP_P$1") (pintype "passive"))
      (node (ref "U27") (pin "57") (pinfunction "2-6_57") (pintype "bidirectional"))
      (node (ref "U29") (pin "8") (pinfunction "A7_8") (pintype "input"))
    )
    (net (code "15") (name "DISP3") (class "Default")
      (node (ref "TP12") (pin "P$1") (pinfunction "MP_P$1") (pintype "passive"))
      (node (ref "U27") (pin "58") (pinfunction "2-7_58") (pintype "bidirectional"))
      (node (ref "U29") (pin "7") (pinfunction "A6_7") (pintype "input"))
    )
    (net (code "16") (name "DISP4") (class "Default")
      (node (ref "TP11") (pin "P$1") (pinfunction "MP_P$1") (pintype "passive"))
      (node (ref "U27") (pin "61") (pinfunction "2-8_61") (pintype "bidirectional"))
      (node (ref "U29") (pin "6") (pinfunction "A5_6") (pintype "input"))
    )
    (net (code "17") (name "DO2") (class "Default")
      (node (ref "U29") (pin "12") (pinfunction "Y7_12") (pintype "output"))
    )
    (net (code "18") (name "DO3") (class "Default")
      (node (ref "U29") (pin "13") (pinfunction "Y6_13") (pintype "output"))
    )
    (net (code "19") (name "DO4") (class "Default")
      (node (ref "U29") (pin "14") (pinfunction "Y5_14") (pintype "output"))
    )
    (net (code "20") (name "DRIVE01+") (class "Default")
      (node (ref "CN16") (pin "25") (pinfunction "25_25") (pintype "bidirectional"))
      (node (ref "U12") (pin "13") (pinfunction "0_13") (pintype "bidirectional"))
    )
    (net (code "21") (name "DRIVE01-") (class "Default")
      (node (ref "CN16") (pin "50") (pinfunction "50_50") (pintype "bidirectional"))
      (node (ref "U18") (pin "13") (pinfunction "0_13") (pintype "bidirectional"))
    )
    (net (code "22") (name "DRIVE02+") (class "Default")
      (node (ref "CN16") (pin "24") (pinfunction "24_24") (pintype "bidirectional"))
      (node (ref "U12") (pin "14") (pinfunction "1_14") (pintype "bidirectional"))
    )
    (net (code "23") (name "DRIVE02-") (class "Default")
      (node (ref "CN16") (pin "49") (pinfunction "49_49") (pintype "bidirectional"))
      (node (ref "U18") (pin "14") (pinfunction "1_14") (pintype "bidirectional"))
    )
    (net (code "24") (name "DRIVE03+") (class "Default")
      (node (ref "CN16") (pin "23") (pinfunction "23_23") (pintype "bidirectional"))
      (node (ref "U12") (pin "15") (pinfunction "2_15") (pintype "bidirectional"))
    )
    (net (code "25") (name "DRIVE03-") (class "Default")
      (node (ref "CN16") (pin "48") (pinfunction "48_48") (pintype "bidirectional"))
      (node (ref "U18") (pin "15") (pinfunction "2_15") (pintype "bidirectional"))
    )
    (net (code "26") (name "DRIVE04+") (class "Default")
      (node (ref "CN16") (pin "22") (pinfunction "22_22") (pintype "bidirectional"))
      (node (ref "U12") (pin "12") (pinfunction "3_12") (pintype "bidirectional"))
    )
    (net (code "27") (name "DRIVE04-") (class "Default")
      (node (ref "CN16") (pin "47") (pinfunction "47_47") (pintype "bidirectional"))
      (node (ref "U18") (pin "12") (pinfunction "3_12") (pintype "bidirectional"))
    )
    (net (code "28") (name "DRIVE05+") (class "Default")
      (node (ref "CN16") (pin "21") (pinfunction "21_21") (pintype "bidirectional"))
      (node (ref "U12") (pin "1") (pinfunction "4_1") (pintype "bidirectional"))
    )
    (net (code "29") (name "DRIVE05-") (class "Default")
      (node (ref "CN16") (pin "46") (pinfunction "46_46") (pintype "bidirectional"))
      (node (ref "U18") (pin "1") (pinfunction "4_1") (pintype "bidirectional"))
    )
    (net (code "30") (name "DRIVE06+") (class "Default")
      (node (ref "CN16") (pin "20") (pinfunction "20_20") (pintype "bidirectional"))
      (node (ref "U12") (pin "5") (pinfunction "5_5") (pintype "bidirectional"))
    )
    (net (code "31") (name "DRIVE06-") (class "Default")
      (node (ref "CN16") (pin "45") (pinfunction "45_45") (pintype "bidirectional"))
      (node (ref "U18") (pin "5") (pinfunction "5_5") (pintype "bidirectional"))
    )
    (net (code "32") (name "DRIVE07+") (class "Default")
      (node (ref "CN16") (pin "19") (pinfunction "19_19") (pintype "bidirectional"))
      (node (ref "U12") (pin "2") (pinfunction "6_2") (pintype "bidirectional"))
    )
    (net (code "33") (name "DRIVE07-") (class "Default")
      (node (ref "CN16") (pin "44") (pinfunction "44_44") (pintype "bidirectional"))
      (node (ref "U18") (pin "2") (pinfunction "6_2") (pintype "bidirectional"))
    )
    (net (code "34") (name "DRIVE08+") (class "Default")
      (node (ref "CN16") (pin "18") (pinfunction "18_18") (pintype "bidirectional"))
      (node (ref "U12") (pin "4") (pinfunction "7_4") (pintype "bidirectional"))
    )
    (net (code "35") (name "DRIVE08-") (class "Default")
      (node (ref "CN16") (pin "43") (pinfunction "43_43") (pintype "bidirectional"))
      (node (ref "U18") (pin "4") (pinfunction "7_4") (pintype "bidirectional"))
    )
    (net (code "36") (name "DRIVE09+") (class "Default")
      (node (ref "CN16") (pin "17") (pinfunction "17_17") (pintype "bidirectional"))
      (node (ref "U14") (pin "13") (pinfunction "0_13") (pintype "bidirectional"))
    )
    (net (code "37") (name "DRIVE09-") (class "Default")
      (node (ref "CN16") (pin "42") (pinfunction "42_42") (pintype "bidirectional"))
      (node (ref "U20") (pin "13") (pinfunction "0_13") (pintype "bidirectional"))
    )
    (net (code "38") (name "DRIVE10+") (class "Default")
      (node (ref "CN16") (pin "16") (pinfunction "16_16") (pintype "bidirectional"))
      (node (ref "U14") (pin "14") (pinfunction "1_14") (pintype "bidirectional"))
    )
    (net (code "39") (name "DRIVE10-") (class "Default")
      (node (ref "CN16") (pin "41") (pinfunction "41_41") (pintype "bidirectional"))
      (node (ref "U20") (pin "14") (pinfunction "1_14") (pintype "bidirectional"))
    )
    (net (code "40") (name "DRIVE11+") (class "Default")
      (node (ref "CN16") (pin "15") (pinfunction "15_15") (pintype "bidirectional"))
      (node (ref "U14") (pin "15") (pinfunction "2_15") (pintype "bidirectional"))
    )
    (net (code "41") (name "DRIVE11-") (class "Default")
      (node (ref "CN16") (pin "40") (pinfunction "40_40") (pintype "bidirectional"))
      (node (ref "U20") (pin "15") (pinfunction "2_15") (pintype "bidirectional"))
    )
    (net (code "42") (name "DRIVE12+") (class "Default")
      (node (ref "CN16") (pin "14") (pinfunction "14_14") (pintype "bidirectional"))
      (node (ref "U14") (pin "12") (pinfunction "3_12") (pintype "bidirectional"))
    )
    (net (code "43") (name "DRIVE12-") (class "Default")
      (node (ref "CN16") (pin "39") (pinfunction "39_39") (pintype "bidirectional"))
      (node (ref "U20") (pin "12") (pinfunction "3_12") (pintype "bidirectional"))
    )
    (net (code "44") (name "DRIVE13+") (class "Default")
      (node (ref "CN16") (pin "13") (pinfunction "13_13") (pintype "bidirectional"))
      (node (ref "U14") (pin "1") (pinfunction "4_1") (pintype "bidirectional"))
    )
    (net (code "45") (name "DRIVE13-") (class "Default")
      (node (ref "CN16") (pin "38") (pinfunction "38_38") (pintype "bidirectional"))
      (node (ref "U20") (pin "1") (pinfunction "4_1") (pintype "bidirectional"))
    )
    (net (code "46") (name "DRIVE14+") (class "Default")
      (node (ref "CN16") (pin "12") (pinfunction "12_12") (pintype "bidirectional"))
      (node (ref "U14") (pin "5") (pinfunction "5_5") (pintype "bidirectional"))
    )
    (net (code "47") (name "DRIVE14-") (class "Default")
      (node (ref "CN16") (pin "37") (pinfunction "37_37") (pintype "bidirectional"))
      (node (ref "U20") (pin "5") (pinfunction "5_5") (pintype "bidirectional"))
    )
    (net (code "48") (name "DRIVE15+") (class "Default")
      (node (ref "CN16") (pin "11") (pinfunction "11_11") (pintype "bidirectional"))
      (node (ref "U14") (pin "2") (pinfunction "6_2") (pintype "bidirectional"))
    )
    (net (code "49") (name "DRIVE15-") (class "Default")
      (node (ref "CN16") (pin "36") (pinfunction "36_36") (pintype "bidirectional"))
      (node (ref "U20") (pin "2") (pinfunction "6_2") (pintype "bidirectional"))
    )
    (net (code "50") (name "DRIVE16+") (class "Default")
      (node (ref "CN16") (pin "10") (pinfunction "10_10") (pintype "bidirectional"))
      (node (ref "U14") (pin "4") (pinfunction "7_4") (pintype "bidirectional"))
    )
    (net (code "51") (name "DRIVE16-") (class "Default")
      (node (ref "CN16") (pin "35") (pinfunction "35_35") (pintype "bidirectional"))
      (node (ref "U20") (pin "4") (pinfunction "7_4") (pintype "bidirectional"))
    )
    (net (code "52") (name "DRIVE17+") (class "Default")
      (node (ref "CN16") (pin "9") (pinfunction "9_9") (pintype "bidirectional"))
      (node (ref "U16") (pin "13") (pinfunction "0_13") (pintype "bidirectional"))
    )
    (net (code "53") (name "DRIVE17-") (class "Default")
      (node (ref "CN16") (pin "34") (pinfunction "34_34") (pintype "bidirectional"))
      (node (ref "U22") (pin "13") (pinfunction "0_13") (pintype "bidirectional"))
    )
    (net (code "54") (name "DRIVE18+") (class "Default")
      (node (ref "CN16") (pin "8") (pinfunction "8_8") (pintype "bidirectional"))
      (node (ref "U16") (pin "14") (pinfunction "1_14") (pintype "bidirectional"))
    )
    (net (code "55") (name "DRIVE18-") (class "Default")
      (node (ref "CN16") (pin "33") (pinfunction "33_33") (pintype "bidirectional"))
      (node (ref "U22") (pin "14") (pinfunction "1_14") (pintype "bidirectional"))
    )
    (net (code "56") (name "DRIVE19+") (class "Default")
      (node (ref "CN16") (pin "7") (pinfunction "7_7") (pintype "bidirectional"))
      (node (ref "U16") (pin "15") (pinfunction "2_15") (pintype "bidirectional"))
    )
    (net (code "57") (name "DRIVE19-") (class "Default")
      (node (ref "CN16") (pin "32") (pinfunction "32_32") (pintype "bidirectional"))
      (node (ref "U22") (pin "15") (pinfunction "2_15") (pintype "bidirectional"))
    )
    (net (code "58") (name "DRIVE20+") (class "Default")
      (node (ref "CN16") (pin "6") (pinfunction "6_6") (pintype "bidirectional"))
      (node (ref "U16") (pin "12") (pinfunction "3_12") (pintype "bidirectional"))
    )
    (net (code "59") (name "DRIVE20-") (class "Default")
      (node (ref "CN16") (pin "31") (pinfunction "31_31") (pintype "bidirectional"))
      (node (ref "U22") (pin "12") (pinfunction "3_12") (pintype "bidirectional"))
    )
    (net (code "60") (name "DRIVE21+") (class "Default")
      (node (ref "CN16") (pin "5") (pinfunction "5_5") (pintype "bidirectional"))
      (node (ref "U16") (pin "1") (pinfunction "4_1") (pintype "bidirectional"))
    )
    (net (code "61") (name "DRIVE21-") (class "Default")
      (node (ref "CN16") (pin "30") (pinfunction "30_30") (pintype "bidirectional"))
      (node (ref "U22") (pin "1") (pinfunction "4_1") (pintype "bidirectional"))
    )
    (net (code "62") (name "DRIVE22+") (class "Default")
      (node (ref "CN16") (pin "4") (pinfunction "4_4") (pintype "bidirectional"))
      (node (ref "U16") (pin "5") (pinfunction "5_5") (pintype "bidirectional"))
    )
    (net (code "63") (name "DRIVE22-") (class "Default")
      (node (ref "CN16") (pin "29") (pinfunction "29_29") (pintype "bidirectional"))
      (node (ref "U22") (pin "5") (pinfunction "5_5") (pintype "bidirectional"))
    )
    (net (code "64") (name "DRIVE23+") (class "Default")
      (node (ref "CN16") (pin "3") (pinfunction "3_3") (pintype "bidirectional"))
      (node (ref "U16") (pin "2") (pinfunction "6_2") (pintype "bidirectional"))
    )
    (net (code "65") (name "DRIVE23-") (class "Default")
      (node (ref "CN16") (pin "28") (pinfunction "28_28") (pintype "bidirectional"))
      (node (ref "U22") (pin "2") (pinfunction "6_2") (pintype "bidirectional"))
    )
    (net (code "66") (name "DRIVE24+") (class "Default")
      (node (ref "CN16") (pin "2") (pinfunction "2_2") (pintype "bidirectional"))
      (node (ref "U16") (pin "4") (pinfunction "7_4") (pintype "bidirectional"))
    )
    (net (code "67") (name "DRIVE24-") (class "Default")
      (node (ref "CN16") (pin "27") (pinfunction "27_27") (pintype "bidirectional"))
      (node (ref "U22") (pin "4") (pinfunction "7_4") (pintype "bidirectional"))
    )
    (net (code "68") (name "DRIVE25+") (class "Default")
      (node (ref "CN17") (pin "25") (pinfunction "25_25") (pintype "bidirectional"))
      (node (ref "U24") (pin "13") (pinfunction "0_13") (pintype "bidirectional"))
    )
    (net (code "69") (name "DRIVE25-") (class "Default")
      (node (ref "CN17") (pin "50") (pinfunction "50_50") (pintype "bidirectional"))
      (node (ref "U17") (pin "13") (pinfunction "0_13") (pintype "bidirectional"))
    )
    (net (code "70") (name "DRIVE26+") (class "Default")
      (node (ref "CN17") (pin "24") (pinfunction "24_24") (pintype "bidirectional"))
      (node (ref "U24") (pin "14") (pinfunction "1_14") (pintype "bidirectional"))
    )
    (net (code "71") (name "DRIVE26-") (class "Default")
      (node (ref "CN17") (pin "49") (pinfunction "49_49") (pintype "bidirectional"))
      (node (ref "U17") (pin "14") (pinfunction "1_14") (pintype "bidirectional"))
    )
    (net (code "72") (name "DRIVE27+") (class "Default")
      (node (ref "CN17") (pin "23") (pinfunction "23_23") (pintype "bidirectional"))
      (node (ref "U24") (pin "15") (pinfunction "2_15") (pintype "bidirectional"))
    )
    (net (code "73") (name "DRIVE27-") (class "Default")
      (node (ref "CN17") (pin "48") (pinfunction "48_48") (pintype "bidirectional"))
      (node (ref "U17") (pin "15") (pinfunction "2_15") (pintype "bidirectional"))
    )
    (net (code "74") (name "DRIVE28+") (class "Default")
      (node (ref "CN17") (pin "22") (pinfunction "22_22") (pintype "bidirectional"))
      (node (ref "U24") (pin "12") (pinfunction "3_12") (pintype "bidirectional"))
    )
    (net (code "75") (name "DRIVE28-") (class "Default")
      (node (ref "CN17") (pin "47") (pinfunction "47_47") (pintype "bidirectional"))
      (node (ref "U17") (pin "12") (pinfunction "3_12") (pintype "bidirectional"))
    )
    (net (code "76") (name "DRIVE29+") (class "Default")
      (node (ref "CN17") (pin "21") (pinfunction "21_21") (pintype "bidirectional"))
      (node (ref "U24") (pin "1") (pinfunction "4_1") (pintype "bidirectional"))
    )
    (net (code "77") (name "DRIVE29-") (class "Default")
      (node (ref "CN17") (pin "46") (pinfunction "46_46") (pintype "bidirectional"))
      (node (ref "U17") (pin "1") (pinfunction "4_1") (pintype "bidirectional"))
    )
    (net (code "78") (name "DRIVE30+") (class "Default")
      (node (ref "CN17") (pin "20") (pinfunction "20_20") (pintype "bidirectional"))
      (node (ref "U24") (pin "5") (pinfunction "5_5") (pintype "bidirectional"))
    )
    (net (code "79") (name "DRIVE30-") (class "Default")
      (node (ref "CN17") (pin "45") (pinfunction "45_45") (pintype "bidirectional"))
      (node (ref "U17") (pin "5") (pinfunction "5_5") (pintype "bidirectional"))
    )
    (net (code "80") (name "DRIVE31+") (class "Default")
      (node (ref "CN17") (pin "19") (pinfunction "19_19") (pintype "bidirectional"))
      (node (ref "U24") (pin "2") (pinfunction "6_2") (pintype "bidirectional"))
    )
    (net (code "81") (name "DRIVE31-") (class "Default")
      (node (ref "CN17") (pin "44") (pinfunction "44_44") (pintype "bidirectional"))
      (node (ref "U17") (pin "2") (pinfunction "6_2") (pintype "bidirectional"))
    )
    (net (code "82") (name "DRIVE32+") (class "Default")
      (node (ref "CN17") (pin "18") (pinfunction "18_18") (pintype "bidirectional"))
      (node (ref "U24") (pin "4") (pinfunction "7_4") (pintype "bidirectional"))
    )
    (net (code "83") (name "DRIVE32-") (class "Default")
      (node (ref "CN17") (pin "43") (pinfunction "43_43") (pintype "bidirectional"))
      (node (ref "U17") (pin "4") (pinfunction "7_4") (pintype "bidirectional"))
    )
    (net (code "84") (name "DRIVE33+") (class "Default")
      (node (ref "CN17") (pin "17") (pinfunction "17_17") (pintype "bidirectional"))
      (node (ref "U13") (pin "13") (pinfunction "0_13") (pintype "bidirectional"))
    )
    (net (code "85") (name "DRIVE33-") (class "Default")
      (node (ref "CN17") (pin "42") (pinfunction "42_42") (pintype "bidirectional"))
      (node (ref "U19") (pin "13") (pinfunction "0_13") (pintype "bidirectional"))
    )
    (net (code "86") (name "DRIVE34+") (class "Default")
      (node (ref "CN17") (pin "16") (pinfunction "16_16") (pintype "bidirectional"))
      (node (ref "U13") (pin "14") (pinfunction "1_14") (pintype "bidirectional"))
    )
    (net (code "87") (name "DRIVE34-") (class "Default")
      (node (ref "CN17") (pin "41") (pinfunction "41_41") (pintype "bidirectional"))
      (node (ref "U19") (pin "14") (pinfunction "1_14") (pintype "bidirectional"))
    )
    (net (code "88") (name "DRIVE35+") (class "Default")
      (node (ref "CN17") (pin "15") (pinfunction "15_15") (pintype "bidirectional"))
      (node (ref "U13") (pin "15") (pinfunction "2_15") (pintype "bidirectional"))
    )
    (net (code "89") (name "DRIVE35-") (class "Default")
      (node (ref "CN17") (pin "40") (pinfunction "40_40") (pintype "bidirectional"))
      (node (ref "U19") (pin "15") (pinfunction "2_15") (pintype "bidirectional"))
    )
    (net (code "90") (name "DRIVE36+") (class "Default")
      (node (ref "CN17") (pin "14") (pinfunction "14_14") (pintype "bidirectional"))
      (node (ref "U13") (pin "12") (pinfunction "3_12") (pintype "bidirectional"))
    )
    (net (code "91") (name "DRIVE36-") (class "Default")
      (node (ref "CN17") (pin "39") (pinfunction "39_39") (pintype "bidirectional"))
      (node (ref "U19") (pin "12") (pinfunction "3_12") (pintype "bidirectional"))
    )
    (net (code "92") (name "DRIVE37+") (class "Default")
      (node (ref "CN17") (pin "13") (pinfunction "13_13") (pintype "bidirectional"))
      (node (ref "U13") (pin "1") (pinfunction "4_1") (pintype "bidirectional"))
    )
    (net (code "93") (name "DRIVE37-") (class "Default")
      (node (ref "CN17") (pin "38") (pinfunction "38_38") (pintype "bidirectional"))
      (node (ref "U19") (pin "1") (pinfunction "4_1") (pintype "bidirectional"))
    )
    (net (code "94") (name "DRIVE38+") (class "Default")
      (node (ref "CN17") (pin "12") (pinfunction "12_12") (pintype "bidirectional"))
      (node (ref "U13") (pin "5") (pinfunction "5_5") (pintype "bidirectional"))
    )
    (net (code "95") (name "DRIVE38-") (class "Default")
      (node (ref "CN17") (pin "37") (pinfunction "37_37") (pintype "bidirectional"))
      (node (ref "U19") (pin "5") (pinfunction "5_5") (pintype "bidirectional"))
    )
    (net (code "96") (name "DRIVE39+") (class "Default")
      (node (ref "CN17") (pin "11") (pinfunction "11_11") (pintype "bidirectional"))
      (node (ref "U13") (pin "2") (pinfunction "6_2") (pintype "bidirectional"))
    )
    (net (code "97") (name "DRIVE39-") (class "Default")
      (node (ref "CN17") (pin "36") (pinfunction "36_36") (pintype "bidirectional"))
      (node (ref "U19") (pin "2") (pinfunction "6_2") (pintype "bidirectional"))
    )
    (net (code "98") (name "DRIVE40+") (class "Default")
      (node (ref "CN17") (pin "10") (pinfunction "10_10") (pintype "bidirectional"))
      (node (ref "U13") (pin "4") (pinfunction "7_4") (pintype "bidirectional"))
    )
    (net (code "99") (name "DRIVE40-") (class "Default")
      (node (ref "CN17") (pin "35") (pinfunction "35_35") (pintype "bidirectional"))
      (node (ref "U19") (pin "4") (pinfunction "7_4") (pintype "bidirectional"))
    )
    (net (code "100") (name "DRIVE41+") (class "Default")
      (node (ref "CN17") (pin "9") (pinfunction "9_9") (pintype "bidirectional"))
      (node (ref "U15") (pin "13") (pinfunction "0_13") (pintype "bidirectional"))
    )
    (net (code "101") (name "DRIVE41-") (class "Default")
      (node (ref "CN17") (pin "34") (pinfunction "34_34") (pintype "bidirectional"))
      (node (ref "U21") (pin "13") (pinfunction "0_13") (pintype "bidirectional"))
    )
    (net (code "102") (name "DRIVE42+") (class "Default")
      (node (ref "CN17") (pin "8") (pinfunction "8_8") (pintype "bidirectional"))
      (node (ref "U15") (pin "14") (pinfunction "1_14") (pintype "bidirectional"))
    )
    (net (code "103") (name "DRIVE42-") (class "Default")
      (node (ref "CN17") (pin "33") (pinfunction "33_33") (pintype "bidirectional"))
      (node (ref "U21") (pin "14") (pinfunction "1_14") (pintype "bidirectional"))
    )
    (net (code "104") (name "DRIVE43+") (class "Default")
      (node (ref "CN17") (pin "7") (pinfunction "7_7") (pintype "bidirectional"))
      (node (ref "U15") (pin "15") (pinfunction "2_15") (pintype "bidirectional"))
    )
    (net (code "105") (name "DRIVE43-") (class "Default")
      (node (ref "CN17") (pin "32") (pinfunction "32_32") (pintype "bidirectional"))
      (node (ref "U21") (pin "15") (pinfunction "2_15") (pintype "bidirectional"))
    )
    (net (code "106") (name "DRIVE44+") (class "Default")
      (node (ref "CN17") (pin "6") (pinfunction "6_6") (pintype "bidirectional"))
      (node (ref "U15") (pin "12") (pinfunction "3_12") (pintype "bidirectional"))
    )
    (net (code "107") (name "DRIVE44-") (class "Default")
      (node (ref "CN17") (pin "31") (pinfunction "31_31") (pintype "bidirectional"))
      (node (ref "U21") (pin "12") (pinfunction "3_12") (pintype "bidirectional"))
    )
    (net (code "108") (name "DRIVE45+") (class "Default")
      (node (ref "CN17") (pin "5") (pinfunction "5_5") (pintype "bidirectional"))
      (node (ref "U15") (pin "1") (pinfunction "4_1") (pintype "bidirectional"))
    )
    (net (code "109") (name "DRIVE45-") (class "Default")
      (node (ref "CN17") (pin "30") (pinfunction "30_30") (pintype "bidirectional"))
      (node (ref "U21") (pin "1") (pinfunction "4_1") (pintype "bidirectional"))
    )
    (net (code "110") (name "DRIVE46+") (class "Default")
      (node (ref "CN17") (pin "4") (pinfunction "4_4") (pintype "bidirectional"))
      (node (ref "U15") (pin "5") (pinfunction "5_5") (pintype "bidirectional"))
    )
    (net (code "111") (name "DRIVE46-") (class "Default")
      (node (ref "CN17") (pin "29") (pinfunction "29_29") (pintype "bidirectional"))
      (node (ref "U21") (pin "5") (pinfunction "5_5") (pintype "bidirectional"))
    )
    (net (code "112") (name "DRIVE47+") (class "Default")
      (node (ref "CN17") (pin "3") (pinfunction "3_3") (pintype "bidirectional"))
      (node (ref "U15") (pin "2") (pinfunction "6_2") (pintype "bidirectional"))
    )
    (net (code "113") (name "DRIVE47-") (class "Default")
      (node (ref "CN17") (pin "28") (pinfunction "28_28") (pintype "bidirectional"))
      (node (ref "U21") (pin "2") (pinfunction "6_2") (pintype "bidirectional"))
    )
    (net (code "114") (name "DRIVE48+") (class "Default")
      (node (ref "CN17") (pin "2") (pinfunction "2_2") (pintype "bidirectional"))
      (node (ref "U15") (pin "4") (pinfunction "7_4") (pintype "bidirectional"))
    )
    (net (code "115") (name "DRIVE48-") (class "Default")
      (node (ref "CN17") (pin "27") (pinfunction "27_27") (pintype "bidirectional"))
      (node (ref "U21") (pin "4") (pinfunction "7_4") (pintype "bidirectional"))
    )
    (net (code "116") (name "DRIVE49+") (class "Default")
      (node (ref "CN16") (pin "1") (pinfunction "1_1") (pintype "bidirectional"))
      (node (ref "U23") (pin "13") (pinfunction "0_13") (pintype "bidirectional"))
    )
    (net (code "117") (name "DRIVE49-") (class "Default")
      (node (ref "CN16") (pin "26") (pinfunction "26_26") (pintype "bidirectional"))
      (node (ref "U25") (pin "13") (pinfunction "0_13") (pintype "bidirectional"))
    )
    (net (code "118") (name "DRIVE50+") (class "Default")
      (node (ref "CN17") (pin "1") (pinfunction "1_1") (pintype "bidirectional"))
      (node (ref "U23") (pin "14") (pinfunction "1_14") (pintype "bidirectional"))
    )
    (net (code "119") (name "DRIVE50-") (class "Default")
      (node (ref "CN17") (pin "26") (pinfunction "26_26") (pintype "bidirectional"))
      (node (ref "U25") (pin "14") (pinfunction "1_14") (pintype "bidirectional"))
    )
    (net (code "120") (name "EXT_IN_+") (class "Default")
      (node (ref "CN2") (pin "1") (pinfunction "1_1") (pintype "bidirectional"))
      (node (ref "CN2") (pin "2") (pinfunction "2_2") (pintype "bidirectional"))
      (node (ref "L2") (pin "4") (pinfunction "2_4") (pintype "passive"))
    )
    (net (code "121") (name "EXT_IN_-") (class "Default")
      (node (ref "CN2") (pin "3") (pinfunction "3_3") (pintype "bidirectional"))
      (node (ref "CN2") (pin "4") (pinfunction "4_4") (pintype "bidirectional"))
      (node (ref "L2") (pin "3") (pinfunction "4_3") (pintype "passive"))
    )
    (net (code "122") (name "EXT{slash}~{INT}") (class "Default")
      (node (ref "R71") (pin "1") (pinfunction "1_1") (pintype "passive"))
      (node (ref "U3") (pin "1") (pinfunction "IN_1") (pintype "input"))
    )
    (net (code "123") (name "FLAME_SYNC") (class "Default")
      (node (ref "U27") (pin "66") (pinfunction "2-11_66") (pintype "bidirectional"))
      (node (ref "U29") (pin "2") (pinfunction "A1_2") (pintype "input"))
      (node (ref "U29") (pin "3") (pinfunction "A2_3") (pintype "input"))
      (node (ref "U29") (pin "4") (pinfunction "A3_4") (pintype "input"))
      (node (ref "U29") (pin "5") (pinfunction "A4_5") (pintype "input"))
    )
    (net (code "124") (name "FSEL") (class "Default")
      (node (ref "CN19") (pin "11") (pinfunction "11_11") (pintype "bidirectional"))
      (node (ref "U27") (pin "71") (pinfunction "2-16_71") (pintype "bidirectional"))
    )
    (net (code "125") (name "FSYNC") (class "Default")
      (node (ref "CN19") (pin "1") (pinfunction "1_1") (pintype "bidirectional"))
      (node (ref "U27") (pin "75") (pinfunction "2-20_75") (pintype "bidirectional"))
    )
    (net (code "126") (name "IOUT+") (class "Default")
      (node (ref "L4") (pin "1") (pinfunction "1_1") (pintype "passive"))
      (node (ref "U12") (pin "3") (pinfunction "COM_3") (pintype "bidirectional"))
      (node (ref "U13") (pin "3") (pinfunction "COM_3") (pintype "bidirectional"))
      (node (ref "U14") (pin "3") (pinfunction "COM_3") (pintype "bidirectional"))
      (node (ref "U15") (pin "3") (pinfunction "COM_3") (pintype "bidirectional"))
      (node (ref "U16") (pin "3") (pinfunction "COM_3") (pintype "bidirectional"))
      (node (ref "U23") (pin "3") (pinfunction "COM_3") (pintype "bidirectional"))
      (node (ref "U24") (pin "3") (pinfunction "COM_3") (pintype "bidirectional"))
    )
    (net (code "127") (name "IOUT-") (class "Default")
      (node (ref "L4") (pin "2") (pinfunction "3_2") (pintype "passive"))
      (node (ref "U17") (pin "3") (pinfunction "COM_3") (pintype "bidirectional"))
      (node (ref "U18") (pin "3") (pinfunction "COM_3") (pintype "bidirectional"))
      (node (ref "U19") (pin "3") (pinfunction "COM_3") (pintype "bidirectional"))
      (node (ref "U20") (pin "3") (pinfunction "COM_3") (pintype "bidirectional"))
      (node (ref "U21") (pin "3") (pinfunction "COM_3") (pintype "bidirectional"))
      (node (ref "U22") (pin "3") (pinfunction "COM_3") (pintype "bidirectional"))
      (node (ref "U25") (pin "3") (pinfunction "COM_3") (pintype "bidirectional"))
    )
    (net (code "128") (name "LED_INT{slash}~{EXT}") (class "Default")
      (node (ref "CN20") (pin "4") (pinfunction "4_4") (pintype "bidirectional"))
      (node (ref "U29") (pin "11") (pinfunction "Y8_11") (pintype "output"))
    )
    (net (code "129") (name "MCLK") (class "Default")
      (node (ref "CN19") (pin "12") (pinfunction "12_12") (pintype "bidirectional"))
      (node (ref "U27") (pin "64") (pinfunction "2-10/CLK3_64") (pintype "bidirectional"))
    )
    (net (code "130") (name "Net-(C2-Pad2)") (class "Default")
      (node (ref "C2") (pin "2") (pinfunction "2_2") (pintype "passive"))
      (node (ref "R5") (pin "2") (pinfunction "2_2") (pintype "passive"))
      (node (ref "R7") (pin "1") (pinfunction "1_1") (pintype "passive"))
    )
    (net (code "131") (name "Net-(CN3-Pad1)") (class "Default")
      (node (ref "CN3") (pin "1") (pinfunction "1_1") (pintype "bidirectional"))
      (node (ref "CN3") (pin "2") (pinfunction "2_2") (pintype "bidirectional"))
      (node (ref "F1") (pin "1") (pinfunction "1_1") (pintype "passive"))
    )
    (net (code "132") (name "Net-(CN4-Pad1)") (class "Default")
      (node (ref "CN4") (pin "1") (pinfunction "1_1") (pintype "bidirectional"))
      (node (ref "CN4") (pin "2") (pinfunction "2_2") (pintype "bidirectional"))
      (node (ref "R58") (pin "2") (pinfunction "2_2") (pintype "passive"))
    )
    (net (code "133") (name "Net-(CN9-Pad1)") (class "Default")
      (node (ref "CN9") (pin "1") (pinfunction "1_1") (pintype "bidirectional"))
      (node (ref "CN9") (pin "2") (pinfunction "2_2") (pintype "bidirectional"))
      (node (ref "F2") (pin "1") (pinfunction "1_1") (pintype "passive"))
    )
    (net (code "134") (name "Net-(CN12-PadP$1)") (class "Default")
      (node (ref "CN12") (pin "P$1") (pinfunction "P$1_P$1") (pintype "bidirectional"))
      (node (ref "CN5") (pin "1") (pinfunction "1_1") (pintype "bidirectional"))
      (node (ref "CN5") (pin "2") (pinfunction "2_2") (pintype "bidirectional"))
    )
    (net (code "135") (name "Net-(CN12-PadP$2)") (class "Default")
      (node (ref "CN12") (pin "P$2") (pinfunction "P$2_P$2") (pintype "bidirectional"))
      (node (ref "CN5") (pin "3") (pinfunction "3_3") (pintype "bidirectional"))
      (node (ref "CN5") (pin "4") (pinfunction "4_4") (pintype "bidirectional"))
    )
    (net (code "136") (name "Net-(CN13-PadP$1)") (class "Default")
      (node (ref "CN13") (pin "P$1") (pinfunction "P$1_P$1") (pintype "bidirectional"))
      (node (ref "CN6") (pin "1") (pinfunction "1_1") (pintype "bidirectional"))
      (node (ref "CN6") (pin "2") (pinfunction "2_2") (pintype "bidirectional"))
    )
    (net (code "137") (name "Net-(CN13-PadP$2)") (class "Default")
      (node (ref "CN13") (pin "P$2") (pinfunction "P$2_P$2") (pintype "bidirectional"))
      (node (ref "CN6") (pin "3") (pinfunction "3_3") (pintype "bidirectional"))
      (node (ref "CN6") (pin "4") (pinfunction "4_4") (pintype "bidirectional"))
    )
    (net (code "138") (name "Net-(CN14-PadP$1)") (class "Default")
      (node (ref "CN14") (pin "P$1") (pinfunction "P$1_P$1") (pintype "bidirectional"))
      (node (ref "CN8") (pin "2") (pinfunction "2_2") (pintype "bidirectional"))
      (node (ref "CN8") (pin "4") (pinfunction "4_4") (pintype "bidirectional"))
    )
    (net (code "139") (name "Net-(CN14-PadP$2)") (class "Default")
      (node (ref "CN14") (pin "P$2") (pinfunction "P$2_P$2") (pintype "bidirectional"))
      (node (ref "CN8") (pin "6") (pinfunction "6_6") (pintype "bidirectional"))
      (node (ref "CN8") (pin "8") (pinfunction "8_8") (pintype "bidirectional"))
    )
    (net (code "140") (name "Net-(CN15-Pad3)") (class "Default")
      (node (ref "CN15") (pin "3") (pinfunction "3_3") (pintype "bidirectional"))
      (node (ref "CN15") (pin "4") (pinfunction "4_4") (pintype "bidirectional"))
      (node (ref "CN9") (pin "3") (pinfunction "3_3") (pintype "bidirectional"))
      (node (ref "CN9") (pin "4") (pinfunction "4_4") (pintype "bidirectional"))
    )
    (net (code "141") (name "Net-(D1-AC)") (class "Default")
      (node (ref "C5") (pin "2") (pinfunction "2_2") (pintype "passive"))
      (node (ref "D1") (pin "3") (pinfunction "AC_3") (pintype "passive"))
      (node (ref "R10") (pin "2") (pinfunction "2_2") (pintype "passive"))
      (node (ref "R15") (pin "1") (pinfunction "1_1") (pintype "passive"))
      (node (ref "U2") (pin "3") (pinfunction "+IN_3") (pintype "input"))
    )
    (net (code "142") (name "Net-(D2-AC)") (class "Default")
      (node (ref "C7") (pin "2") (pinfunction "2_2") (pintype "passive"))
      (node (ref "D2") (pin "3") (pinfunction "AC_3") (pintype "passive"))
      (node (ref "R11") (pin "2") (pinfunction "2_2") (pintype "passive"))
      (node (ref "R16") (pin "1") (pinfunction "1_1") (pintype "passive"))
      (node (ref "U2") (pin "2") (pinfunction "-IN_2") (pintype "input"))
    )
    (net (code "143") (name "Net-(D3-AC)") (class "Default")
      (node (ref "D3") (pin "3") (pinfunction "AC_3") (pintype "passive"))
      (node (ref "R12") (pin "2") (pinfunction "2_2") (pintype "passive"))
      (node (ref "R12") (pin "3") (pinfunction "3_3") (pintype "passive"))
      (node (ref "R17") (pin "1") (pinfunction "1_1") (pintype "passive"))
    )
    (net (code "144") (name "Net-(D4-A1)") (class "Default")
      (node (ref "D4") (pin "A") (pinfunction "A1_A") (pintype "passive"))
      (node (ref "R59") (pin "1") (pinfunction "1_1") (pintype "passive"))
    )
    (net (code "145") (name "Net-(D5-A1)") (class "Default")
      (node (ref "D5") (pin "A") (pinfunction "A1_A") (pintype "passive"))
      (node (ref "R60") (pin "1") (pinfunction "1_1") (pintype "passive"))
    )
    (net (code "146") (name "Net-(D5-K1)") (class "Default")
      (node (ref "CN7") (pin "3") (pinfunction "3_3") (pintype "bidirectional"))
      (node (ref "D5") (pin "C") (pinfunction "K1_C") (pintype "passive"))
    )
    (net (code "147") (name "Net-(D6-A1)") (class "Default")
      (node (ref "D6") (pin "A") (pinfunction "A1_A") (pintype "passive"))
      (node (ref "R61") (pin "1") (pinfunction "1_1") (pintype "passive"))
    )
    (net (code "148") (name "Net-(D6-K1)") (class "Default")
      (node (ref "CN7") (pin "4") (pinfunction "4_4") (pintype "bidirectional"))
      (node (ref "D6") (pin "C") (pinfunction "K1_C") (pintype "passive"))
    )
    (net (code "149") (name "Net-(L1-2)") (class "Default")
      (node (ref "CN1") (pin "1") (pinfunction "1_1") (pintype "bidirectional"))
      (node (ref "CN1") (pin "2") (pinfunction "2_2") (pintype "bidirectional"))
      (node (ref "L1") (pin "4") (pinfunction "2_4") (pintype "passive"))
    )
    (net (code "150") (name "Net-(L1-3)") (class "Default")
      (node (ref "L1") (pin "2") (pinfunction "3_2") (pintype "passive"))
      (node (ref "R9") (pin "1") (pinfunction "1_1") (pintype "passive"))
    )
    (net (code "151") (name "Net-(L1-4)") (class "Default")
      (node (ref "CN1") (pin "3") (pinfunction "3_3") (pintype "bidirectional"))
      (node (ref "CN1") (pin "4") (pinfunction "4_4") (pintype "bidirectional"))
      (node (ref "L1") (pin "3") (pinfunction "4_3") (pintype "passive"))
    )
    (net (code "152") (name "Net-(L1-Pad1)") (class "Default")
      (node (ref "L1") (pin "1") (pinfunction "1_1") (pintype "passive"))
      (node (ref "R8") (pin "1") (pinfunction "1_1") (pintype "passive"))
    )
    (net (code "153") (name "Net-(L2-3)") (class "Default")
      (node (ref "L2") (pin "2") (pinfunction "3_2") (pintype "passive"))
      (node (ref "R11") (pin "1") (pinfunction "1_1") (pintype "passive"))
    )
    (net (code "154") (name "Net-(L2-Pad1)") (class "Default")
      (node (ref "L2") (pin "1") (pinfunction "1_1") (pintype "passive"))
      (node (ref "R10") (pin "1") (pinfunction "1_1") (pintype "passive"))
    )
    (net (code "155") (name "Net-(L4-2)") (class "Default")
      (node (ref "L4") (pin "4") (pinfunction "2_4") (pintype "passive"))
      (node (ref "R51") (pin "2") (pinfunction "2_2") (pintype "passive"))
      (node (ref "R52") (pin "2") (pinfunction "2_2") (pintype "passive"))
      (node (ref "R53") (pin "2") (pinfunction "2_2") (pintype "passive"))
      (node (ref "R54") (pin "2") (pinfunction "2_2") (pintype "passive"))
      (node (ref "TP2") (pin "1") (pinfunction "MP_1") (pintype "passive"))
    )
    (net (code "156") (name "Net-(L4-4)") (class "Default")
      (node (ref "L4") (pin "3") (pinfunction "4_3") (pintype "passive"))
      (node (ref "R56") (pin "2") (pinfunction "2_2") (pintype "passive"))
      (node (ref "TP6") (pin "1") (pinfunction "MP_1") (pintype "passive"))
      (node (ref "U11") (pin "4") (pinfunction "+IN_4") (pintype "input"))
    )
    (net (code "157") (name "Net-(R1-Pad2)") (class "Default")
      (node (ref "R1") (pin "2") (pinfunction "2_2") (pintype "passive"))
      (node (ref "R2") (pin "3") (pinfunction "3_3") (pintype "passive"))
    )
    (net (code "158") (name "Net-(R2-Pad1)") (class "Default")
      (node (ref "R2") (pin "1") (pinfunction "1_1") (pintype "passive"))
      (node (ref "R4") (pin "1") (pinfunction "1_1") (pintype "passive"))
    )
    (net (code "159") (name "Net-(R3-Pad2)") (class "Default")
      (node (ref "R3") (pin "2") (pinfunction "2_2") (pintype "passive"))
      (node (ref "R5") (pin "1") (pinfunction "1_1") (pintype "passive"))
    )
    (net (code "160") (name "Net-(R12-Pad1)") (class "Default")
      (node (ref "R12") (pin "1") (pinfunction "1_1") (pintype "passive"))
      (node (ref "R7") (pin "2") (pinfunction "2_2") (pintype "passive"))
    )
    (net (code "161") (name "Net-(R23-Pad1)") (class "Default")
      (node (ref "R23") (pin "1") (pinfunction "1_1") (pintype "passive"))
      (node (ref "R24") (pin "2") (pinfunction "2_2") (pintype "passive"))
    )
    (net (code "162") (name "Net-(SW1A-C)") (class "Default")
      (node (ref "CN15") (pin "1") (pinfunction "1_1") (pintype "bidirectional"))
      (node (ref "CN15") (pin "2") (pinfunction "2_2") (pintype "bidirectional"))
      (node (ref "SW1") (pin "2") (pinfunction "C_2") (pintype "passive"))
    )
    (net (code "163") (name "Net-(SW1A-NC)") (class "Default")
      (node (ref "F2") (pin "2") (pinfunction "2_2") (pintype "passive"))
      (node (ref "SW1") (pin "3") (pinfunction "NC_3") (pintype "passive"))
    )
    (net (code "164") (name "Net-(TP1-MP)") (class "Default")
      (node (ref "R44") (pin "2") (pinfunction "2_2") (pintype "passive"))
      (node (ref "TP1") (pin "1") (pinfunction "MP_1") (pintype "passive"))
      (node (ref "U8") (pin "1") (pinfunction "OUT_1") (pintype "output"))
      (node (ref "U9") (pin "6") (pinfunction "COM_6") (pintype "bidirectional"))
    )
    (net (code "165") (name "Net-(TP3-MP)") (class "Default")
      (node (ref "C14") (pin "1") (pinfunction "1_1") (pintype "passive"))
      (node (ref "R35") (pin "2") (pinfunction "2_2") (pintype "passive"))
      (node (ref "R37") (pin "1") (pinfunction "1_1") (pintype "passive"))
      (node (ref "R38") (pin "1") (pinfunction "1_1") (pintype "passive"))
      (node (ref "TP3") (pin "1") (pinfunction "MP_1") (pintype "passive"))
    )
    (net (code "166") (name "Net-(TP4-MP)") (class "Default")
      (node (ref "C19") (pin "1") (pinfunction "1_1") (pintype "passive"))
      (node (ref "R45") (pin "2") (pinfunction "2_2") (pintype "passive"))
      (node (ref "TP4") (pin "1") (pinfunction "MP_1") (pintype "passive"))
      (node (ref "U8") (pin "7") (pinfunction "OUT_7") (pintype "output"))
      (node (ref "U9") (pin "10") (pinfunction "COM_10") (pintype "bidirectional"))
    )
    (net (code "167") (name "Net-(TP5-MP)") (class "Default")
      (node (ref "R27") (pin "1") (pinfunction "1_1") (pintype "passive"))
      (node (ref "TP5") (pin "1") (pinfunction "MP_1") (pintype "passive"))
      (node (ref "U3") (pin "10") (pinfunction "COM_10") (pintype "bidirectional"))
      (node (ref "U7") (pin "1") (pinfunction "-IN_1") (pintype "input"))
    )
    (net (code "168") (name "Net-(U1A-+IN)") (class "Default")
      (node (ref "C1") (pin "1") (pinfunction "1_1") (pintype "passive"))
      (node (ref "R3") (pin "1") (pinfunction "1_1") (pintype "passive"))
      (node (ref "U1") (pin "3") (pinfunction "+IN_3") (pintype "input"))
    )
    (net (code "169") (name "Net-(U1A--IN)") (class "Default")
      (node (ref "R2") (pin "2") (pinfunction "2_2") (pintype "passive"))
      (node (ref "U1") (pin "2") (pinfunction "-IN_2") (pintype "input"))
    )
    (net (code "170") (name "Net-(U1A-OUT)") (class "Default")
      (node (ref "C2") (pin "1") (pinfunction "1_1") (pintype "passive"))
      (node (ref "R4") (pin "2") (pinfunction "2_2") (pintype "passive"))
      (node (ref "R6") (pin "1") (pinfunction "1_1") (pintype "passive"))
      (node (ref "U1") (pin "1") (pinfunction "OUT_1") (pintype "output"))
    )
    (net (code "171") (name "Net-(U1B--IN)") (class "Default")
      (node (ref "C6") (pin "2") (pinfunction "2_2") (pintype "passive"))
      (node (ref "R6") (pin "2") (pinfunction "2_2") (pintype "passive"))
      (node (ref "U1") (pin "6") (pinfunction "-IN_6") (pintype "input"))
    )
    (net (code "172") (name "Net-(U1B-OUT)") (class "Default")
      (node (ref "C6") (pin "1") (pinfunction "1_1") (pintype "passive"))
      (node (ref "R17") (pin "2") (pinfunction "2_2") (pintype "passive"))
      (node (ref "R19") (pin "1") (pinfunction "1_1") (pintype "passive"))
      (node (ref "U1") (pin "7") (pinfunction "OUT_7") (pintype "output"))
    )
    (net (code "173") (name "Net-(U2A-OUT)") (class "Default")
      (node (ref "C7") (pin "1") (pinfunction "1_1") (pintype "passive"))
      (node (ref "R16") (pin "2") (pinfunction "2_2") (pintype "passive"))
      (node (ref "R20") (pin "1") (pinfunction "1_1") (pintype "passive"))
      (node (ref "U2") (pin "1") (pinfunction "OUT_1") (pintype "output"))
    )
    (net (code "174") (name "Net-(U2B-+IN)") (class "Default")
      (node (ref "C3") (pin "2") (pinfunction "2_2") (pintype "passive"))
      (node (ref "R13") (pin "1") (pinfunction "1_1") (pintype "passive"))
      (node (ref "R8") (pin "2") (pinfunction "2_2") (pintype "passive"))
      (node (ref "U2") (pin "5") (pinfunction "+IN_5") (pintype "input"))
    )
    (net (code "175") (name "Net-(U2B--IN)") (class "Default")
      (node (ref "C4") (pin "2") (pinfunction "2_2") (pintype "passive"))
      (node (ref "R14") (pin "1") (pinfunction "1_1") (pintype "passive"))
      (node (ref "R9") (pin "2") (pinfunction "2_2") (pintype "passive"))
      (node (ref "U2") (pin "6") (pinfunction "-IN_6") (pintype "input"))
    )
    (net (code "176") (name "Net-(U2B-OUT)") (class "Default")
      (node (ref "C4") (pin "1") (pinfunction "1_1") (pintype "passive"))
      (node (ref "R14") (pin "2") (pinfunction "2_2") (pintype "passive"))
      (node (ref "R18") (pin "1") (pinfunction "1_1") (pintype "passive"))
      (node (ref "U2") (pin "7") (pinfunction "OUT_7") (pintype "output"))
    )
    (net (code "177") (name "Net-(U3A-NC)") (class "Default")
      (node (ref "U3") (pin "6") (pinfunction "COM_6") (pintype "bidirectional"))
      (node (ref "U3") (pin "9") (pinfunction "NC_9") (pintype "bidirectional"))
    )
    (net (code "178") (name "Net-(U3A-NO)") (class "Default")
      (node (ref "R20") (pin "2") (pinfunction "2_2") (pintype "passive"))
      (node (ref "U3") (pin "2") (pinfunction "NO_2") (pintype "bidirectional"))
    )
    (net (code "179") (name "Net-(U3B-NC)") (class "Default")
      (node (ref "R18") (pin "2") (pinfunction "2_2") (pintype "passive"))
      (node (ref "U3") (pin "7") (pinfunction "NC_7") (pintype "bidirectional"))
    )
    (net (code "180") (name "Net-(U3B-NO)") (class "Default")
      (node (ref "R19") (pin "2") (pinfunction "2_2") (pintype "passive"))
      (node (ref "U3") (pin "4") (pinfunction "NO_4") (pintype "bidirectional"))
    )
    (net (code "181") (name "Net-(U4-EN)") (class "Default")
      (node (ref "R26") (pin "2") (pinfunction "2_2") (pintype "passive"))
      (node (ref "U4") (pin "3") (pinfunction "EN_3") (pintype "input"))
    )
    (net (code "182") (name "Net-(U4-NR)") (class "Default")
      (node (ref "C12") (pin "1") (pinfunction "1_1") (pintype "passive"))
      (node (ref "U4") (pin "4") (pinfunction "NR_4") (pintype "passive"))
    )
    (net (code "183") (name "Net-(U5A-+IN)") (class "Default")
      (node (ref "R27") (pin "2") (pinfunction "2_2") (pintype "passive"))
      (node (ref "R29") (pin "2") (pinfunction "2_2") (pintype "passive"))
      (node (ref "U5") (pin "3") (pinfunction "+IN_3") (pintype "input"))
    )
    (net (code "184") (name "Net-(U5A-OUT)") (class "Default")
      (node (ref "C14") (pin "2") (pinfunction "2_2") (pintype "passive"))
      (node (ref "R33") (pin "2") (pinfunction "2_2") (pintype "passive"))
      (node (ref "R35") (pin "1") (pinfunction "1_1") (pintype "passive"))
      (node (ref "U5") (pin "1") (pinfunction "OUT_1") (pintype "output"))
    )
    (net (code "185") (name "Net-(U5B-+IN)") (class "Default")
      (node (ref "C20") (pin "1") (pinfunction "1_1") (pintype "passive"))
      (node (ref "R42") (pin "1") (pinfunction "1_1") (pintype "passive"))
      (node (ref "R43") (pin "2") (pinfunction "2_2") (pintype "passive"))
      (node (ref "U5") (pin "5") (pinfunction "+IN_5") (pintype "input"))
    )
    (net (code "186") (name "Net-(U6-CT)") (class "Default")
      (node (ref "C11") (pin "1") (pinfunction "1_1") (pintype "passive"))
      (node (ref "U6") (pin "4") (pinfunction "CT_4") (pintype "passive"))
    )
    (net (code "187") (name "Net-(U6-SENSE)") (class "Default")
      (node (ref "C10") (pin "1") (pinfunction "1_1") (pintype "passive"))
      (node (ref "R24") (pin "1") (pinfunction "1_1") (pintype "passive"))
      (node (ref "R25") (pin "2") (pinfunction "2_2") (pintype "passive"))
      (node (ref "U6") (pin "5") (pinfunction "SENSE_5") (pintype "bidirectional"))
    )
    (net (code "188") (name "Net-(U7-+IN)") (class "Default")
      (node (ref "R31") (pin "1") (pinfunction "1_1") (pintype "passive"))
      (node (ref "R32") (pin "2") (pinfunction "2_2") (pintype "passive"))
      (node (ref "R34") (pin "1") (pinfunction "1_1") (pintype "passive"))
      (node (ref "U7") (pin "3") (pinfunction "+IN_3") (pintype "input"))
    )
    (net (code "189") (name "Net-(U7-OUT)") (class "Default")
      (node (ref "R34") (pin "2") (pinfunction "2_2") (pintype "passive"))
      (node (ref "R39") (pin "1") (pinfunction "1_1") (pintype "passive"))
      (node (ref "U7") (pin "4") (pinfunction "OUT_4") (pintype "output"))
    )
    (net (code "190") (name "Net-(U8A-+IN)") (class "Default")
      (node (ref "C17") (pin "1") (pinfunction "1_1") (pintype "passive"))
      (node (ref "R37") (pin "2") (pinfunction "2_2") (pintype "passive"))
      (node (ref "R41") (pin "2") (pinfunction "2_2") (pintype "passive"))
      (node (ref "U8") (pin "3") (pinfunction "+IN_3") (pintype "input"))
    )
    (net (code "191") (name "Net-(U8A--IN)") (class "Default")
      (node (ref "R40") (pin "2") (pinfunction "2_2") (pintype "passive"))
      (node (ref "R44") (pin "1") (pinfunction "1_1") (pintype "passive"))
      (node (ref "U8") (pin "2") (pinfunction "-IN_2") (pintype "input"))
    )
    (net (code "192") (name "Net-(U8B--IN)") (class "Default")
      (node (ref "C19") (pin "2") (pinfunction "2_2") (pintype "passive"))
      (node (ref "R38") (pin "2") (pinfunction "2_2") (pintype "passive"))
      (node (ref "R45") (pin "1") (pinfunction "1_1") (pintype "passive"))
      (node (ref "U8") (pin "6") (pinfunction "-IN_6") (pintype "input"))
    )
    (net (code "193") (name "Net-(U9A-NC)") (class "Default")
      (node (ref "R47") (pin "1") (pinfunction "1_1") (pintype "passive"))
      (node (ref "R48") (pin "1") (pinfunction "1_1") (pintype "passive"))
      (node (ref "U9") (pin "9") (pinfunction "NC_9") (pintype "bidirectional"))
    )
    (net (code "194") (name "Net-(U9A-NO)") (class "Default")
      (node (ref "R49") (pin "1") (pinfunction "1_1") (pintype "passive"))
      (node (ref "R50") (pin "1") (pinfunction "1_1") (pintype "passive"))
      (node (ref "U9") (pin "2") (pinfunction "NO_2") (pintype "bidirectional"))
    )
    (net (code "195") (name "Net-(U9B-NC)") (class "Default")
      (node (ref "R51") (pin "1") (pinfunction "1_1") (pintype "passive"))
      (node (ref "R52") (pin "1") (pinfunction "1_1") (pintype "passive"))
      (node (ref "U9") (pin "7") (pinfunction "NC_7") (pintype "bidirectional"))
    )
    (net (code "196") (name "Net-(U9B-NO)") (class "Default")
      (node (ref "R53") (pin "1") (pinfunction "1_1") (pintype "passive"))
      (node (ref "R54") (pin "1") (pinfunction "1_1") (pintype "passive"))
      (node (ref "U9") (pin "4") (pinfunction "NO_4") (pintype "bidirectional"))
    )
    (net (code "197") (name "Net-(U10C-0)") (class "Default")
      (node (ref "R30") (pin "2") (pinfunction "2_2") (pintype "passive"))
      (node (ref "R33") (pin "1") (pinfunction "1_1") (pintype "passive"))
      (node (ref "U10") (pin "12") (pinfunction "0_12") (pintype "bidirectional"))
    )
    (net (code "198") (name "Net-(U10C-1)") (class "Default")
      (node (ref "R28") (pin "2") (pinfunction "2_2") (pintype "passive"))
      (node (ref "R30") (pin "1") (pinfunction "1_1") (pintype "passive"))
      (node (ref "U10") (pin "14") (pinfunction "1_14") (pintype "bidirectional"))
    )
    (net (code "199") (name "Net-(U10C-2)") (class "Default")
      (node (ref "R22") (pin "2") (pinfunction "2_2") (pintype "passive"))
      (node (ref "R28") (pin "1") (pinfunction "1_1") (pintype "passive"))
      (node (ref "U10") (pin "15") (pinfunction "2_15") (pintype "bidirectional"))
    )
    (net (code "200") (name "Net-(U10C-3)") (class "Default")
      (node (ref "R21") (pin "2") (pinfunction "2_2") (pintype "passive"))
      (node (ref "R22") (pin "1") (pinfunction "1_1") (pintype "passive"))
      (node (ref "U10") (pin "11") (pinfunction "3_11") (pintype "bidirectional"))
    )
    (net (code "201") (name "Net-(U10C-COM)") (class "Default")
      (node (ref "U10") (pin "13") (pinfunction "COM_13") (pintype "bidirectional"))
      (node (ref "U5") (pin "2") (pinfunction "-IN_2") (pintype "input"))
    )
    (net (code "202") (name "Net-(U11--IN)") (class "Default")
      (node (ref "R47") (pin "2") (pinfunction "2_2") (pintype "passive"))
      (node (ref "R48") (pin "2") (pinfunction "2_2") (pintype "passive"))
      (node (ref "R49") (pin "2") (pinfunction "2_2") (pintype "passive"))
      (node (ref "R50") (pin "2") (pinfunction "2_2") (pintype "passive"))
      (node (ref "R56") (pin "1") (pinfunction "1_1") (pintype "passive"))
      (node (ref "U11") (pin "1") (pinfunction "-IN_1") (pintype "input"))
    )
    (net (code "203") (name "Net-(U11-REF)") (class "Default")
      (node (ref "R46") (pin "1") (pinfunction "1_1") (pintype "passive"))
      (node (ref "U11") (pin "6") (pinfunction "REF_6") (pintype "passive"))
      (node (ref "U5") (pin "6") (pinfunction "-IN_6") (pintype "input"))
      (node (ref "U5") (pin "7") (pinfunction "OUT_7") (pintype "output"))
    )
    (net (code "204") (name "Net-(U11-RG1)") (class "Default")
      (node (ref "R55") (pin "2") (pinfunction "2_2") (pintype "passive"))
      (node (ref "R57") (pin "2") (pinfunction "2_2") (pintype "passive"))
      (node (ref "U11") (pin "2") (pinfunction "RG1_2") (pintype "passive"))
    )
    (net (code "205") (name "Net-(U11-RG2)") (class "Default")
      (node (ref "R55") (pin "1") (pinfunction "1_1") (pintype "passive"))
      (node (ref "R57") (pin "1") (pinfunction "1_1") (pintype "passive"))
      (node (ref "U11") (pin "3") (pinfunction "RG2_3") (pintype "passive"))
    )
    (net (code "206") (name "Net-(U26-EN)") (class "Default")
      (node (ref "R64") (pin "2") (pinfunction "2_2") (pintype "passive"))
      (node (ref "U26") (pin "3") (pinfunction "EN_3") (pintype "input"))
    )
    (net (code "207") (name "Net-(U26-NR)") (class "Default")
      (node (ref "C52") (pin "1") (pinfunction "1_1") (pintype "passive"))
      (node (ref "U26") (pin "4") (pinfunction "NR_4") (pintype "passive"))
    )
    (net (code "208") (name "Net-(U27A-TCK)") (class "Default")
      (node (ref "CN18") (pin "1") (pinfunction "1_1") (pintype "bidirectional"))
      (node (ref "R65") (pin "2") (pinfunction "2_2") (pintype "passive"))
      (node (ref "U27") (pin "24") (pinfunction "TCK_24") (pintype "bidirectional"))
    )
    (net (code "209") (name "Net-(U27A-TDI)") (class "Default")
      (node (ref "CN18") (pin "9") (pinfunction "9_9") (pintype "bidirectional"))
      (node (ref "R66") (pin "1") (pinfunction "1_1") (pintype "passive"))
      (node (ref "U27") (pin "23") (pinfunction "TDI_23") (pintype "bidirectional"))
    )
    (net (code "210") (name "Net-(U27A-TDO)") (class "Default")
      (node (ref "CN18") (pin "3") (pinfunction "3_3") (pintype "bidirectional"))
      (node (ref "R62") (pin "1") (pinfunction "1_1") (pintype "passive"))
      (node (ref "U27") (pin "25") (pinfunction "TDO_25") (pintype "bidirectional"))
    )
    (net (code "211") (name "Net-(U27A-TMS)") (class "Default")
      (node (ref "CN18") (pin "5") (pinfunction "5_5") (pintype "bidirectional"))
      (node (ref "R63") (pin "1") (pinfunction "1_1") (pintype "passive"))
      (node (ref "U27") (pin "22") (pinfunction "TMS_22") (pintype "bidirectional"))
    )
    (net (code "212") (name "Net-(U27B-1-9{slash}CLK1)") (class "Default")
      (node (ref "R67") (pin "2") (pinfunction "2_2") (pintype "passive"))
      (node (ref "U27") (pin "14") (pinfunction "1-9/CLK1_14") (pintype "bidirectional"))
    )
    (net (code "213") (name "Net-(U27B-1-10)") (class "Default")
      (node (ref "R69") (pin "2") (pinfunction "2_2") (pintype "passive"))
      (node (ref "U27") (pin "15") (pinfunction "1-10_15") (pintype "bidirectional"))
    )
    (net (code "214") (name "Net-(U27B-1-11)") (class "Default")
      (node (ref "R68") (pin "2") (pinfunction "2_2") (pintype "passive"))
      (node (ref "U27") (pin "16") (pinfunction "1-11_16") (pintype "bidirectional"))
    )
    (net (code "215") (name "Net-(U27B-1-17)") (class "Default")
      (node (ref "R70") (pin "2") (pinfunction "2_2") (pintype "passive"))
      (node (ref "U27") (pin "26") (pinfunction "1-17_26") (pintype "bidirectional"))
    )
    (net (code "216") (name "Net-(U27B-1-18)") (class "Default")
      (node (ref "R71") (pin "2") (pinfunction "2_2") (pintype "passive"))
      (node (ref "U27") (pin "27") (pinfunction "1-18_27") (pintype "bidirectional"))
    )
    (net (code "217") (name "Net-(U28-NR)") (class "Default")
      (node (ref "C56") (pin "1") (pinfunction "1_1") (pintype "passive"))
      (node (ref "U28") (pin "4") (pinfunction "NR_4") (pintype "passive"))
    )
    (net (code "218") (name "Net-(U29A-Y1)") (class "Default")
      (node (ref "R83") (pin "1") (pinfunction "1_1") (pintype "passive"))
      (node (ref "U29") (pin "18") (pinfunction "Y1_18") (pintype "output"))
    )
    (net (code "219") (name "Net-(U29A-Y2)") (class "Default")
      (node (ref "R84") (pin "1") (pinfunction "1_1") (pintype "passive"))
      (node (ref "U29") (pin "17") (pinfunction "Y2_17") (pintype "output"))
    )
    (net (code "220") (name "Net-(U29A-~{G})") (class "Default")
      (node (ref "R77") (pin "2") (pinfunction "2_2") (pintype "passive"))
      (node (ref "U29") (pin "19") (pinfunction "~{G}_19") (pintype "input"))
    )
    (net (code "221") (name "Net-(U30-A)") (class "Default")
      (node (ref "R84") (pin "2") (pinfunction "2_2") (pintype "passive"))
      (node (ref "U30") (pin "1") (pinfunction "A_1") (pintype "passive"))
    )
    (net (code "222") (name "PSEL") (class "Default")
      (node (ref "CN19") (pin "13") (pinfunction "13_13") (pintype "bidirectional"))
      (node (ref "U27") (pin "70") (pinfunction "2-15_70") (pintype "bidirectional"))
    )
    (net (code "223") (name "RESET") (class "Default")
      (node (ref "CN19") (pin "9") (pinfunction "9_9") (pintype "bidirectional"))
      (node (ref "U27") (pin "72") (pinfunction "2-17_72") (pintype "bidirectional"))
    )
    (net (code "224") (name "SCLK") (class "Default")
      (node (ref "CN19") (pin "3") (pinfunction "3_3") (pintype "bidirectional"))
      (node (ref "U27") (pin "74") (pinfunction "2-19_74") (pintype "bidirectional"))
    )
    (net (code "225") (name "SDATA") (class "Default")
      (node (ref "CN19") (pin "5") (pinfunction "5_5") (pintype "bidirectional"))
      (node (ref "U27") (pin "73") (pinfunction "2-18_73") (pintype "bidirectional"))
    )
    (net (code "226") (name "SW1") (class "Default")
      (node (ref "C61") (pin "1") (pinfunction "1_1") (pintype "passive"))
      (node (ref "R81") (pin "1") (pinfunction "1_1") (pintype "passive"))
      (node (ref "U27") (pin "52") (pinfunction "2-1_52") (pintype "bidirectional"))
    )
    (net (code "227") (name "SW2") (class "Default")
      (node (ref "C60") (pin "1") (pinfunction "1_1") (pintype "passive"))
      (node (ref "R80") (pin "1") (pinfunction "1_1") (pintype "passive"))
      (node (ref "U27") (pin "53") (pinfunction "2-2_53") (pintype "bidirectional"))
    )
    (net (code "228") (name "SW3") (class "Default")
      (node (ref "C59") (pin "1") (pinfunction "1_1") (pintype "passive"))
      (node (ref "R79") (pin "1") (pinfunction "1_1") (pintype "passive"))
      (node (ref "U27") (pin "54") (pinfunction "2-3_54") (pintype "bidirectional"))
    )
    (net (code "229") (name "SW4") (class "Default")
      (node (ref "C58") (pin "1") (pinfunction "1_1") (pintype "passive"))
      (node (ref "R78") (pin "1") (pinfunction "1_1") (pintype "passive"))
      (node (ref "U27") (pin "55") (pinfunction "2-4_55") (pintype "bidirectional"))
    )
    (net (code "230") (name "SW5") (class "Default")
      (node (ref "C62") (pin "1") (pinfunction "1_1") (pintype "passive"))
      (node (ref "R82") (pin "1") (pinfunction "1_1") (pintype "passive"))
      (node (ref "U27") (pin "51") (pinfunction "1-38_51") (pintype "bidirectional"))
    )
    (net (code "231") (name "SW_DDS{slash}~{ANALOG}") (class "Default")
      (node (ref "CN20") (pin "13") (pinfunction "13_13") (pintype "bidirectional"))
      (node (ref "R76") (pin "1") (pinfunction "1_1") (pintype "passive"))
      (node (ref "R82") (pin "2") (pinfunction "2_2") (pintype "passive"))
    )
    (net (code "232") (name "SW_INT{slash}~{EXT}") (class "Default")
      (node (ref "CN20") (pin "12") (pinfunction "12_12") (pintype "bidirectional"))
      (node (ref "R75") (pin "1") (pinfunction "1_1") (pintype "passive"))
      (node (ref "R81") (pin "2") (pinfunction "2_2") (pintype "passive"))
    )
    (net (code "233") (name "SW_X1{slash}~{X2}") (class "Default")
      (node (ref "CN20") (pin "11") (pinfunction "11_11") (pintype "bidirectional"))
      (node (ref "R74") (pin "1") (pinfunction "1_1") (pintype "passive"))
      (node (ref "R80") (pin "2") (pinfunction "2_2") (pintype "passive"))
    )
    (net (code "234") (name "SW_X1{slash}~{X10}") (class "Default")
      (node (ref "CN20") (pin "10") (pinfunction "10_10") (pintype "bidirectional"))
      (node (ref "R73") (pin "1") (pinfunction "1_1") (pintype "passive"))
      (node (ref "R79") (pin "2") (pinfunction "2_2") (pintype "passive"))
    )
    (net (code "235") (name "SW_~{TEST}") (class "Default")
      (node (ref "CN20") (pin "9") (pinfunction "9_9") (pintype "bidirectional"))
      (node (ref "R72") (pin "1") (pinfunction "1_1") (pintype "passive"))
      (node (ref "R78") (pin "2") (pinfunction "2_2") (pintype "passive"))
    )
    (net (code "236") (name "SYNC_ISO_C") (class "Default")
      (node (ref "CN20") (pin "5") (pinfunction "5_5") (pintype "bidirectional"))
      (node (ref "U30") (pin "4") (pinfunction "COL_4") (pintype "passive"))
    )
    (net (code "237") (name "SYNC_ISO_E") (class "Default")
      (node (ref "CN20") (pin "6") (pinfunction "6_6") (pintype "bidirectional"))
      (node (ref "U30") (pin "3") (pinfunction "EMI_3") (pintype "passive"))
    )
    (net (code "238") (name "SYNC_OSC") (class "Default")
      (node (ref "R39") (pin "2") (pinfunction "2_2") (pintype "passive"))
      (node (ref "TP8") (pin "1") (pinfunction "MP_1") (pintype "passive"))
      (node (ref "U27") (pin "18") (pinfunction "1-13_18") (pintype "bidirectional"))
    )
    (net (code "239") (name "SYNC_OUT") (class "Default")
      (node (ref "CN20") (pin "7") (pinfunction "7_7") (pintype "bidirectional"))
      (node (ref "R83") (pin "2") (pinfunction "2_2") (pintype "passive"))
    )
    (net (code "240") (name "UI_DDS{slash}~{ANALOG}") (class "Default")
      (node (ref "CN11") (pin "2") (pinfunction "2_2") (pintype "bidirectional"))
      (node (ref "CN11") (pin "3") (pinfunction "3_3") (pintype "bidirectional"))
      (node (ref "CN7") (pin "13") (pinfunction "13_13") (pintype "bidirectional"))
    )
    (net (code "241") (name "UI_INT{slash}~{EXT}") (class "Default")
      (node (ref "CN7") (pin "12") (pinfunction "12_12") (pintype "bidirectional"))
      (node (ref "SW4") (pin "2") (pinfunction "C_2") (pintype "passive"))
    )
    (net (code "242") (name "UI_SYNC_C") (class "Default")
      (node (ref "CN7") (pin "5") (pinfunction "5_5") (pintype "bidirectional"))
      (node (ref "CN8") (pin "1") (pinfunction "1_1") (pintype "bidirectional"))
    )
    (net (code "243") (name "UI_SYNC_E") (class "Default")
      (node (ref "CN7") (pin "6") (pinfunction "6_6") (pintype "bidirectional"))
      (node (ref "CN8") (pin "5") (pinfunction "5_5") (pintype "bidirectional"))
    )
    (net (code "244") (name "UI_SYNC_N") (class "Default")
      (node (ref "CN7") (pin "8") (pinfunction "8_8") (pintype "bidirectional"))
      (node (ref "CN8") (pin "7") (pinfunction "7_7") (pintype "bidirectional"))
    )
    (net (code "245") (name "UI_SYNC_P") (class "Default")
      (node (ref "CN7") (pin "7") (pinfunction "7_7") (pintype "bidirectional"))
      (node (ref "CN8") (pin "3") (pinfunction "3_3") (pintype "bidirectional"))
    )
    (net (code "246") (name "UI_VD+3V3") (class "Default")
      (node (ref "CN7") (pin "1") (pinfunction "1_1") (pintype "bidirectional"))
      (node (ref "R59") (pin "2") (pinfunction "2_2") (pintype "passive"))
      (node (ref "R60") (pin "2") (pinfunction "2_2") (pintype "passive"))
      (node (ref "R61") (pin "2") (pinfunction "2_2") (pintype "passive"))
    )
    (net (code "247") (name "UI_X1{slash}~{X2}") (class "Default")
      (node (ref "CN7") (pin "11") (pinfunction "11_11") (pintype "bidirectional"))
      (node (ref "SW3") (pin "2") (pinfunction "C_2") (pintype "passive"))
    )
    (net (code "248") (name "UI_X1{slash}~{X10}") (class "Default")
      (node (ref "CN7") (pin "10") (pinfunction "10_10") (pintype "bidirectional"))
      (node (ref "SW2") (pin "2") (pinfunction "C_2") (pintype "passive"))
    )
    (net (code "249") (name "UI_~{TEST}") (class "Default")
      (node (ref "CN10") (pin "2") (pinfunction "2_2") (pintype "bidirectional"))
      (node (ref "CN10") (pin "3") (pinfunction "3_3") (pintype "bidirectional"))
      (node (ref "CN7") (pin "9") (pinfunction "9_9") (pintype "bidirectional"))
    )
    (net (code "250") (name "VA+3V3") (class "Default")
      (node (ref "C13") (pin "1") (pinfunction "1_1") (pintype "passive"))
      (node (ref "C15") (pin "2") (pinfunction "2_2") (pintype "passive"))
      (node (ref "C16") (pin "1") (pinfunction "1_1") (pintype "passive"))
      (node (ref "C18") (pin "1") (pinfunction "1_1") (pintype "passive"))
      (node (ref "C21") (pin "1") (pinfunction "1_1") (pintype "passive"))
      (node (ref "C22") (pin "1") (pinfunction "1_1") (pintype "passive"))
      (node (ref "C24") (pin "1") (pinfunction "1_1") (pintype "passive"))
      (node (ref "C25") (pin "1") (pinfunction "1_1") (pintype "passive"))
      (node (ref "C27") (pin "1") (pinfunction "1_1") (pintype "passive"))
      (node (ref "C28") (pin "1") (pinfunction "1_1") (pintype "passive"))
      (node (ref "C29") (pin "1") (pinfunction "1_1") (pintype "passive"))
      (node (ref "C30") (pin "1") (pinfunction "1_1") (pintype "passive"))
      (node (ref "C31") (pin "1") (pinfunction "1_1") (pintype "passive"))
      (node (ref "C32") (pin "1") (pinfunction "1_1") (pintype "passive"))
      (node (ref "C33") (pin "1") (pinfunction "1_1") (pintype "passive"))
      (node (ref "C34") (pin "1") (pinfunction "1_1") (pintype "passive"))
      (node (ref "C35") (pin "1") (pinfunction "1_1") (pintype "passive"))
      (node (ref "C36") (pin "1") (pinfunction "1_1") (pintype "passive"))
      (node (ref "C37") (pin "1") (pinfunction "1_1") (pintype "passive"))
      (node (ref "C38") (pin "1") (pinfunction "1_1") (pintype "passive"))
      (node (ref "C39") (pin "1") (pinfunction "1_1") (pintype "passive"))
      (node (ref "C40") (pin "1") (pinfunction "1_1") (pintype "passive"))
      (node (ref "C41") (pin "1") (pinfunction "1_1") (pintype "passive"))
      (node (ref "D1") (pin "2") (pinfunction "C_2") (pintype "passive"))
      (node (ref "D2") (pin "2") (pinfunction "C_2") (pintype "passive"))
      (node (ref "R31") (pin "2") (pinfunction "2_2") (pintype "passive"))
      (node (ref "R42") (pin "2") (pinfunction "2_2") (pintype "passive"))
      (node (ref "U1") (pin "8") (pinfunction "V+_8") (pintype "power_in"))
      (node (ref "U10") (pin "16") (pinfunction "VCC_16") (pintype "power_in"))
      (node (ref "U12") (pin "16") (pinfunction "V+_16") (pintype "power_in"))
      (node (ref "U13") (pin "16") (pinfunction "V+_16") (pintype "power_in"))
      (node (ref "U14") (pin "16") (pinfunction "V+_16") (pintype "power_in"))
      (node (ref "U15") (pin "16") (pinfunction "V+_16") (pintype "power_in"))
      (node (ref "U16") (pin "16") (pinfunction "V+_16") (pintype "power_in"))
      (node (ref "U17") (pin "16") (pinfunction "V+_16") (pintype "power_in"))
      (node (ref "U18") (pin "16") (pinfunction "V+_16") (pintype "power_in"))
      (node (ref "U19") (pin "16") (pinfunction "V+_16") (pintype "power_in"))
      (node (ref "U2") (pin "8") (pinfunction "V+_8") (pintype "power_in"))
      (node (ref "U20") (pin "16") (pinfunction "V+_16") (pintype "power_in"))
      (node (ref "U21") (pin "16") (pinfunction "V+_16") (pintype "power_in"))
      (node (ref "U22") (pin "16") (pinfunction "V+_16") (pintype "power_in"))
      (node (ref "U23") (pin "16") (pinfunction "V+_16") (pintype "power_in"))
      (node (ref "U24") (pin "16") (pinfunction "V+_16") (pintype "power_in"))
      (node (ref "U25") (pin "16") (pinfunction "V+_16") (pintype "power_in"))
      (node (ref "U3") (pin "8") (pinfunction "V+_8") (pintype "power_in"))
      (node (ref "U4") (pin "5") (pinfunction "VO_5") (pintype "passive"))
      (node (ref "U5") (pin "8") (pinfunction "V+_8") (pintype "power_in"))
      (node (ref "U7") (pin "5") (pinfunction "V+_5") (pintype "power_in"))
      (node (ref "U8") (pin "8") (pinfunction "V+_8") (pintype "power_in"))
      (node (ref "U9") (pin "8") (pinfunction "V+_8") (pintype "power_in"))
    )
    (net (code "251") (name "VA+5") (class "Default")
      (node (ref "C26") (pin "2") (pinfunction "2_2") (pintype "passive"))
      (node (ref "C8") (pin "POS") (pinfunction "POS_POS") (pintype "passive"))
      (node (ref "C9") (pin "1") (pinfunction "1_1") (pintype "passive"))
      (node (ref "L3") (pin "1") (pinfunction "1_1") (pintype "passive"))
      (node (ref "R26") (pin "1") (pinfunction "1_1") (pintype "passive"))
      (node (ref "U11") (pin "8") (pinfunction "V+_8") (pintype "power_in"))
      (node (ref "U4") (pin "1") (pinfunction "VI_1") (pintype "input"))
    )
    (net (code "252") (name "VD+1V8") (class "Default")
      (node (ref "C49") (pin "2") (pinfunction "2_2") (pintype "passive"))
      (node (ref "C51") (pin "2") (pinfunction "2_2") (pintype "passive"))
      (node (ref "C57") (pin "1") (pinfunction "1_1") (pintype "passive"))
      (node (ref "U27") (pin "13") (pinfunction "VCCINT_1_13") (pintype "power_in"))
      (node (ref "U27") (pin "63") (pinfunction "VCCINT_2_63") (pintype "power_in"))
      (node (ref "U28") (pin "5") (pinfunction "VO_5") (pintype "passive"))
    )
    (net (code "253") (name "VD+3V3") (class "Default")
      (node (ref "C42") (pin "1") (pinfunction "1_1") (pintype "passive"))
      (node (ref "C43") (pin "1") (pinfunction "1_1") (pintype "passive"))
      (node (ref "C44") (pin "1") (pinfunction "1_1") (pintype "passive"))
      (node (ref "C45") (pin "1") (pinfunction "1_1") (pintype "passive"))
      (node (ref "C48") (pin "2") (pinfunction "2_2") (pintype "passive"))
      (node (ref "C50") (pin "2") (pinfunction "2_2") (pintype "passive"))
      (node (ref "C53") (pin "1") (pinfunction "1_1") (pintype "passive"))
      (node (ref "C54") (pin "1") (pinfunction "1_1") (pintype "passive"))
      (node (ref "C55") (pin "1") (pinfunction "1_1") (pintype "passive"))
      (node (ref "CN18") (pin "4") (pinfunction "4_4") (pintype "bidirectional"))
      (node (ref "CN19") (pin "6") (pinfunction "6_6") (pintype "bidirectional"))
      (node (ref "CN19") (pin "8") (pinfunction "8_8") (pintype "bidirectional"))
      (node (ref "CN20") (pin "1") (pinfunction "1_1") (pintype "bidirectional"))
      (node (ref "R36") (pin "2") (pinfunction "2_2") (pintype "passive"))
      (node (ref "R62") (pin "2") (pinfunction "2_2") (pintype "passive"))
      (node (ref "R63") (pin "2") (pinfunction "2_2") (pintype "passive"))
      (node (ref "R66") (pin "2") (pinfunction "2_2") (pintype "passive"))
      (node (ref "R72") (pin "2") (pinfunction "2_2") (pintype "passive"))
      (node (ref "R73") (pin "2") (pinfunction "2_2") (pintype "passive"))
      (node (ref "R74") (pin "2") (pinfunction "2_2") (pintype "passive"))
      (node (ref "R75") (pin "2") (pinfunction "2_2") (pintype "passive"))
      (node (ref "R76") (pin "2") (pinfunction "2_2") (pintype "passive"))
      (node (ref "U26") (pin "5") (pinfunction "VO_5") (pintype "passive"))
      (node (ref "U27") (pin "31") (pinfunction "VCCIO1_2_31") (pintype "power_in"))
      (node (ref "U27") (pin "45") (pinfunction "VCCIO1_3_45") (pintype "power_in"))
      (node (ref "U27") (pin "59") (pinfunction "VCCIO2_1_59") (pintype "power_in"))
      (node (ref "U27") (pin "80") (pinfunction "VCCIO2_2_80") (pintype "power_in"))
      (node (ref "U27") (pin "9") (pinfunction "VCCIO1_1_9") (pintype "power_in"))
      (node (ref "U27") (pin "94") (pinfunction "VCCIO2_3_94") (pintype "power_in"))
      (node (ref "U28") (pin "1") (pinfunction "VI_1") (pintype "input"))
      (node (ref "U28") (pin "3") (pinfunction "EN_3") (pintype "input"))
      (node (ref "U29") (pin "1") (pinfunction "CONT_1") (pintype "input"))
      (node (ref "U29") (pin "20") (pinfunction "VCC_20") (pintype "power_in"))
    )
    (net (code "254") (name "VD_BAT") (class "Default")
      (node (ref "C46") (pin "POS") (pinfunction "POS_POS") (pintype "passive"))
      (node (ref "C47") (pin "1") (pinfunction "1_1") (pintype "passive"))
      (node (ref "L5") (pin "4") (pinfunction "2_4") (pintype "passive"))
      (node (ref "R23") (pin "2") (pinfunction "2_2") (pintype "passive"))
      (node (ref "R64") (pin "1") (pinfunction "1_1") (pintype "passive"))
      (node (ref "U26") (pin "1") (pinfunction "VI_1") (pintype "input"))
      (node (ref "U6") (pin "6") (pinfunction "VDD_6") (pintype "power_in"))
    )
    (net (code "255") (name "ZOUT") (class "Default")
      (node (ref "U27") (pin "21") (pinfunction "1-16_21") (pintype "bidirectional"))
      (node (ref "U9") (pin "1") (pinfunction "IN_1") (pintype "input"))
      (node (ref "U9") (pin "5") (pinfunction "IN_5") (pintype "input"))
    )
    (net (code "256") (name "unconnected-(CN7-Pad14)") (class "Default")
      (node (ref "CN7") (pin "14") (pinfunction "14_14") (pintype "bidirectional"))
    )
    (net (code "257") (name "unconnected-(CN10-Pad1)") (class "Default")
      (node (ref "CN10") (pin "1") (pinfunction "1_1") (pintype "bidirectional"))
    )
    (net (code "258") (name "unconnected-(CN11-Pad1)") (class "Default")
      (node (ref "CN11") (pin "1") (pinfunction "1_1") (pintype "bidirectional"))
    )
    (net (code "259") (name "unconnected-(CN18-Pad6)") (class "Default")
      (node (ref "CN18") (pin "6") (pinfunction "6_6") (pintype "bidirectional"))
    )
    (net (code "260") (name "unconnected-(CN18-Pad7)") (class "Default")
      (node (ref "CN18") (pin "7") (pinfunction "7_7") (pintype "bidirectional"))
    )
    (net (code "261") (name "unconnected-(CN18-Pad8)") (class "Default")
      (node (ref "CN18") (pin "8") (pinfunction "8_8") (pintype "bidirectional"))
    )
    (net (code "262") (name "unconnected-(CN19-Pad7)") (class "Default")
      (node (ref "CN19") (pin "7") (pinfunction "7_7") (pintype "bidirectional"))
    )
    (net (code "263") (name "unconnected-(CN19-Pad14)") (class "Default")
      (node (ref "CN19") (pin "14") (pinfunction "14_14") (pintype "bidirectional"))
    )
    (net (code "264") (name "unconnected-(CN20-Pad14)") (class "Default")
      (node (ref "CN20") (pin "14") (pinfunction "14_14") (pintype "bidirectional"))
    )
    (net (code "265") (name "unconnected-(SW1A-NO-Pad1)") (class "Default")
      (node (ref "SW1") (pin "1") (pinfunction "NO_1") (pintype "passive"))
    )
    (net (code "266") (name "unconnected-(SW2A-NO-Pad1)") (class "Default")
      (node (ref "SW2") (pin "1") (pinfunction "NO_1") (pintype "passive"))
    )
    (net (code "267") (name "unconnected-(SW3A-NO-Pad1)") (class "Default")
      (node (ref "SW3") (pin "1") (pinfunction "NO_1") (pintype "passive"))
    )
    (net (code "268") (name "unconnected-(SW4A-NO-Pad1)") (class "Default")
      (node (ref "SW4") (pin "1") (pinfunction "NO_1") (pintype "passive"))
    )
    (net (code "269") (name "unconnected-(U6-~{MR}-Pad3)") (class "Default")
      (node (ref "U6") (pin "3") (pinfunction "~{MR}_3") (pintype "bidirectional"))
    )
    (net (code "270") (name "unconnected-(U10-Pad2)") (class "Default")
      (node (ref "U10") (pin "2") (pinfunction "2_2") (pintype "bidirectional"))
    )
    (net (code "271") (name "unconnected-(U10D-0-Pad1)") (class "Default")
      (node (ref "U10") (pin "1") (pinfunction "0_1") (pintype "bidirectional"))
    )
    (net (code "272") (name "unconnected-(U10D-1-Pad5)") (class "Default")
      (node (ref "U10") (pin "5") (pinfunction "1_5") (pintype "bidirectional"))
    )
    (net (code "273") (name "unconnected-(U10D-3-Pad4)") (class "Default")
      (node (ref "U10") (pin "4") (pinfunction "3_4") (pintype "bidirectional"))
    )
    (net (code "274") (name "unconnected-(U10D-COM-Pad3)") (class "Default")
      (node (ref "U10") (pin "3") (pinfunction "COM_3") (pintype "bidirectional"))
    )
    (net (code "275") (name "unconnected-(U23-Pad5)") (class "Default")
      (node (ref "U23") (pin "5") (pinfunction "5_5") (pintype "bidirectional"))
    )
    (net (code "276") (name "unconnected-(U23B-2-Pad15)") (class "Default")
      (node (ref "U23") (pin "15") (pinfunction "2_15") (pintype "bidirectional"))
    )
    (net (code "277") (name "unconnected-(U23B-3-Pad12)") (class "Default")
      (node (ref "U23") (pin "12") (pinfunction "3_12") (pintype "bidirectional"))
    )
    (net (code "278") (name "unconnected-(U23B-4-Pad1)") (class "Default")
      (node (ref "U23") (pin "1") (pinfunction "4_1") (pintype "bidirectional"))
    )
    (net (code "279") (name "unconnected-(U23B-6-Pad2)") (class "Default")
      (node (ref "U23") (pin "2") (pinfunction "6_2") (pintype "bidirectional"))
    )
    (net (code "280") (name "unconnected-(U23B-7-Pad4)") (class "Default")
      (node (ref "U23") (pin "4") (pinfunction "7_4") (pintype "bidirectional"))
    )
    (net (code "281") (name "unconnected-(U25-Pad5)") (class "Default")
      (node (ref "U25") (pin "5") (pinfunction "5_5") (pintype "bidirectional"))
    )
    (net (code "282") (name "unconnected-(U25B-2-Pad15)") (class "Default")
      (node (ref "U25") (pin "15") (pinfunction "2_15") (pintype "bidirectional"))
    )
    (net (code "283") (name "unconnected-(U25B-3-Pad12)") (class "Default")
      (node (ref "U25") (pin "12") (pinfunction "3_12") (pintype "bidirectional"))
    )
    (net (code "284") (name "unconnected-(U25B-4-Pad1)") (class "Default")
      (node (ref "U25") (pin "1") (pinfunction "4_1") (pintype "bidirectional"))
    )
    (net (code "285") (name "unconnected-(U25B-6-Pad2)") (class "Default")
      (node (ref "U25") (pin "2") (pinfunction "6_2") (pintype "bidirectional"))
    )
    (net (code "286") (name "unconnected-(U25B-7-Pad4)") (class "Default")
      (node (ref "U25") (pin "4") (pinfunction "7_4") (pintype "bidirectional"))
    )
    (net (code "287") (name "unconnected-(U27B-1-19-Pad28)") (class "Default")
      (node (ref "U27") (pin "28") (pinfunction "1-19_28") (pintype "bidirectional"))
    )
    (net (code "288") (name "unconnected-(U27B-1-20-Pad29)") (class "Default")
      (node (ref "U27") (pin "29") (pinfunction "1-20_29") (pintype "bidirectional"))
    )
    (net (code "289") (name "unconnected-(U27B-1-21-Pad30)") (class "Default")
      (node (ref "U27") (pin "30") (pinfunction "1-21_30") (pintype "bidirectional"))
    )
    (net (code "290") (name "unconnected-(U27B-1-22-Pad33)") (class "Default")
      (node (ref "U27") (pin "33") (pinfunction "1-22_33") (pintype "bidirectional"))
    )
    (net (code "291") (name "unconnected-(U27B-1-23-Pad34)") (class "Default")
      (node (ref "U27") (pin "34") (pinfunction "1-23_34") (pintype "bidirectional"))
    )
    (net (code "292") (name "unconnected-(U27B-1-24-Pad35)") (class "Default")
      (node (ref "U27") (pin "35") (pinfunction "1-24_35") (pintype "bidirectional"))
    )
    (net (code "293") (name "unconnected-(U27B-1-25-Pad36)") (class "Default")
      (node (ref "U27") (pin "36") (pinfunction "1-25_36") (pintype "bidirectional"))
    )
    (net (code "294") (name "unconnected-(U27B-1-26-Pad37)") (class "Default")
      (node (ref "U27") (pin "37") (pinfunction "1-26_37") (pintype "bidirectional"))
    )
    (net (code "295") (name "unconnected-(U27B-1-27-Pad38)") (class "Default")
      (node (ref "U27") (pin "38") (pinfunction "1-27_38") (pintype "bidirectional"))
    )
    (net (code "296") (name "unconnected-(U27B-1-28-Pad39)") (class "Default")
      (node (ref "U27") (pin "39") (pinfunction "1-28_39") (pintype "bidirectional"))
    )
    (net (code "297") (name "unconnected-(U27B-1-29-Pad40)") (class "Default")
      (node (ref "U27") (pin "40") (pinfunction "1-29_40") (pintype "bidirectional"))
    )
    (net (code "298") (name "unconnected-(U27B-1-30-Pad41)") (class "Default")
      (node (ref "U27") (pin "41") (pinfunction "1-30_41") (pintype "bidirectional"))
    )
    (net (code "299") (name "unconnected-(U27B-1-31-Pad42)") (class "Default")
      (node (ref "U27") (pin "42") (pinfunction "1-31_42") (pintype "bidirectional"))
    )
    (net (code "300") (name "unconnected-(U27B-1-34-Pad47)") (class "Default")
      (node (ref "U27") (pin "47") (pinfunction "1-34_47") (pintype "bidirectional"))
    )
    (net (code "301") (name "unconnected-(U27B-1-35-Pad48)") (class "Default")
      (node (ref "U27") (pin "48") (pinfunction "1-35_48") (pintype "bidirectional"))
    )
    (net (code "302") (name "unconnected-(U27B-1-36-Pad49)") (class "Default")
      (node (ref "U27") (pin "49") (pinfunction "1-36_49") (pintype "bidirectional"))
    )
    (net (code "303") (name "unconnected-(U27B-1-37-Pad50)") (class "Default")
      (node (ref "U27") (pin "50") (pinfunction "1-37_50") (pintype "bidirectional"))
    )
    (net (code "304") (name "unconnected-(U27B-2-9{slash}CLK2-Pad62)") (class "Default")
      (node (ref "U27") (pin "62") (pinfunction "2-9/CLK2_62") (pintype "bidirectional"))
    )
    (net (code "305") (name "unconnected-(U27B-2-12-Pad67)") (class "Default")
      (node (ref "U27") (pin "67") (pinfunction "2-12_67") (pintype "bidirectional"))
    )
    (net (code "306") (name "unconnected-(U27B-2-13-Pad68)") (class "Default")
      (node (ref "U27") (pin "68") (pinfunction "2-13_68") (pintype "bidirectional"))
    )
    (net (code "307") (name "unconnected-(U27B-2-14-Pad69)") (class "Default")
      (node (ref "U27") (pin "69") (pinfunction "2-14_69") (pintype "bidirectional"))
    )
    (net (code "308") (name "unconnected-(U27B-2-21-Pad76)") (class "Default")
      (node (ref "U27") (pin "76") (pinfunction "2-21_76") (pintype "bidirectional"))
    )
    (net (code "309") (name "unconnected-(U27B-2-22-Pad77)") (class "Default")
      (node (ref "U27") (pin "77") (pinfunction "2-22_77") (pintype "bidirectional"))
    )
    (net (code "310") (name "unconnected-(U27B-2-23-Pad78)") (class "Default")
      (node (ref "U27") (pin "78") (pinfunction "2-23_78") (pintype "bidirectional"))
    )
    (net (code "311") (name "unconnected-(U27B-2-24-Pad81)") (class "Default")
      (node (ref "U27") (pin "81") (pinfunction "2-24_81") (pintype "bidirectional"))
    )
    (net (code "312") (name "unconnected-(U27B-2-25-Pad82)") (class "Default")
      (node (ref "U27") (pin "82") (pinfunction "2-25_82") (pintype "bidirectional"))
    )
    (net (code "313") (name "unconnected-(U27B-2-26-Pad83)") (class "Default")
      (node (ref "U27") (pin "83") (pinfunction "2-26_83") (pintype "bidirectional"))
    )
    (net (code "314") (name "unconnected-(U27B-2-27-Pad84)") (class "Default")
      (node (ref "U27") (pin "84") (pinfunction "2-27_84") (pintype "bidirectional"))
    )
    (net (code "315") (name "unconnected-(U27B-2-28-Pad85)") (class "Default")
      (node (ref "U27") (pin "85") (pinfunction "2-28_85") (pintype "bidirectional"))
    )
    (net (code "316") (name "unconnected-(U27B-2-29-Pad86)") (class "Default")
      (node (ref "U27") (pin "86") (pinfunction "2-29_86") (pintype "bidirectional"))
    )
    (net (code "317") (name "unconnected-(U27B-2-30-Pad87)") (class "Default")
      (node (ref "U27") (pin "87") (pinfunction "2-30_87") (pintype "bidirectional"))
    )
    (net (code "318") (name "unconnected-(U27B-2-31-Pad88)") (class "Default")
      (node (ref "U27") (pin "88") (pinfunction "2-31_88") (pintype "bidirectional"))
    )
    (net (code "319") (name "unconnected-(U27B-2-32-Pad89)") (class "Default")
      (node (ref "U27") (pin "89") (pinfunction "2-32_89") (pintype "bidirectional"))
    )
    (net (code "320") (name "unconnected-(U27B-2-33-Pad90)") (class "Default")
      (node (ref "U27") (pin "90") (pinfunction "2-33_90") (pintype "bidirectional"))
    )
    (net (code "321") (name "unconnected-(U27B-2-34-Pad91)") (class "Default")
      (node (ref "U27") (pin "91") (pinfunction "2-34_91") (pintype "bidirectional"))
    )
    (net (code "322") (name "unconnected-(U27B-2-35-Pad92)") (class "Default")
      (node (ref "U27") (pin "92") (pinfunction "2-35_92") (pintype "bidirectional"))
    )
    (net (code "323") (name "unconnected-(U27B-2-36-Pad95)") (class "Default")
      (node (ref "U27") (pin "95") (pinfunction "2-36_95") (pintype "bidirectional"))
    )
    (net (code "324") (name "unconnected-(U27B-2-37-Pad96)") (class "Default")
      (node (ref "U27") (pin "96") (pinfunction "2-37_96") (pintype "bidirectional"))
    )
    (net (code "325") (name "unconnected-(U27B-2-38-Pad97)") (class "Default")
      (node (ref "U27") (pin "97") (pinfunction "2-38_97") (pintype "bidirectional"))
    )
    (net (code "326") (name "unconnected-(U27B-2-39-Pad98)") (class "Default")
      (node (ref "U27") (pin "98") (pinfunction "2-39_98") (pintype "bidirectional"))
    )
    (net (code "327") (name "unconnected-(U27B-2-40-Pad99)") (class "Default")
      (node (ref "U27") (pin "99") (pinfunction "2-40_99") (pintype "bidirectional"))
    )
    (net (code "328") (name "unconnected-(U27B-2-41-Pad100)") (class "Default")
      (node (ref "U27") (pin "100") (pinfunction "2-41_100") (pintype "bidirectional"))
    )
    (net (code "329") (name "unconnected-(U29A-Y3-Pad16)") (class "Default")
      (node (ref "U29") (pin "16") (pinfunction "Y3_16") (pintype "output"))
    )
    (net (code "330") (name "unconnected-(U29A-Y4-Pad15)") (class "Default")
      (node (ref "U29") (pin "15") (pinfunction "Y4_15") (pintype "output"))
    )
    (net (code "331") (name "~{CS0}") (class "Default")
      (node (ref "U12") (pin "6") (pinfunction "EN_6") (pintype "input"))
      (node (ref "U18") (pin "6") (pinfunction "EN_6") (pintype "input"))
      (node (ref "U27") (pin "2") (pinfunction "1-1_2") (pintype "bidirectional"))
    )
    (net (code "332") (name "~{CS1}") (class "Default")
      (node (ref "U14") (pin "6") (pinfunction "EN_6") (pintype "input"))
      (node (ref "U20") (pin "6") (pinfunction "EN_6") (pintype "input"))
      (node (ref "U27") (pin "3") (pinfunction "1-2_3") (pintype "bidirectional"))
    )
    (net (code "333") (name "~{CS2}") (class "Default")
      (node (ref "U16") (pin "6") (pinfunction "EN_6") (pintype "input"))
      (node (ref "U22") (pin "6") (pinfunction "EN_6") (pintype "input"))
      (node (ref "U27") (pin "4") (pinfunction "1-3_4") (pintype "bidirectional"))
    )
    (net (code "334") (name "~{CS3}") (class "Default")
      (node (ref "U17") (pin "6") (pinfunction "EN_6") (pintype "input"))
      (node (ref "U24") (pin "6") (pinfunction "EN_6") (pintype "input"))
      (node (ref "U27") (pin "5") (pinfunction "1-4_5") (pintype "bidirectional"))
    )
    (net (code "335") (name "~{CS4}") (class "Default")
      (node (ref "U13") (pin "6") (pinfunction "EN_6") (pintype "input"))
      (node (ref "U19") (pin "6") (pinfunction "EN_6") (pintype "input"))
      (node (ref "U27") (pin "6") (pinfunction "1-5_6") (pintype "bidirectional"))
    )
    (net (code "336") (name "~{CS5}") (class "Default")
      (node (ref "U15") (pin "6") (pinfunction "EN_6") (pintype "input"))
      (node (ref "U21") (pin "6") (pinfunction "EN_6") (pintype "input"))
      (node (ref "U27") (pin "7") (pinfunction "1-6_7") (pintype "bidirectional"))
    )
    (net (code "337") (name "~{CS6}") (class "Default")
      (node (ref "U23") (pin "6") (pinfunction "EN_6") (pintype "input"))
      (node (ref "U25") (pin "6") (pinfunction "EN_6") (pintype "input"))
      (node (ref "U27") (pin "8") (pinfunction "1-7_8") (pintype "bidirectional"))
    )
    (net (code "338") (name "~{LOW_BAT}") (class "Default")
      (node (ref "CN20") (pin "3") (pinfunction "3_3") (pintype "bidirectional"))
      (node (ref "R36") (pin "1") (pinfunction "1_1") (pintype "passive"))
      (node (ref "U27") (pin "12") (pinfunction "1-8/CLK0_12") (pintype "bidirectional"))
      (node (ref "U6") (pin "1") (pinfunction "~{RESET}_1") (pintype "output"))
    )
    (net (code "339") (name "~{OE}") (class "Default")
      (node (ref "U27") (pin "17") (pinfunction "1-12_17") (pintype "bidirectional"))
    )
  )
)
